# ENERGIS_Rack-PDU_1_0_0.net
KiCad netlist of a schematic drawn in EAGLE
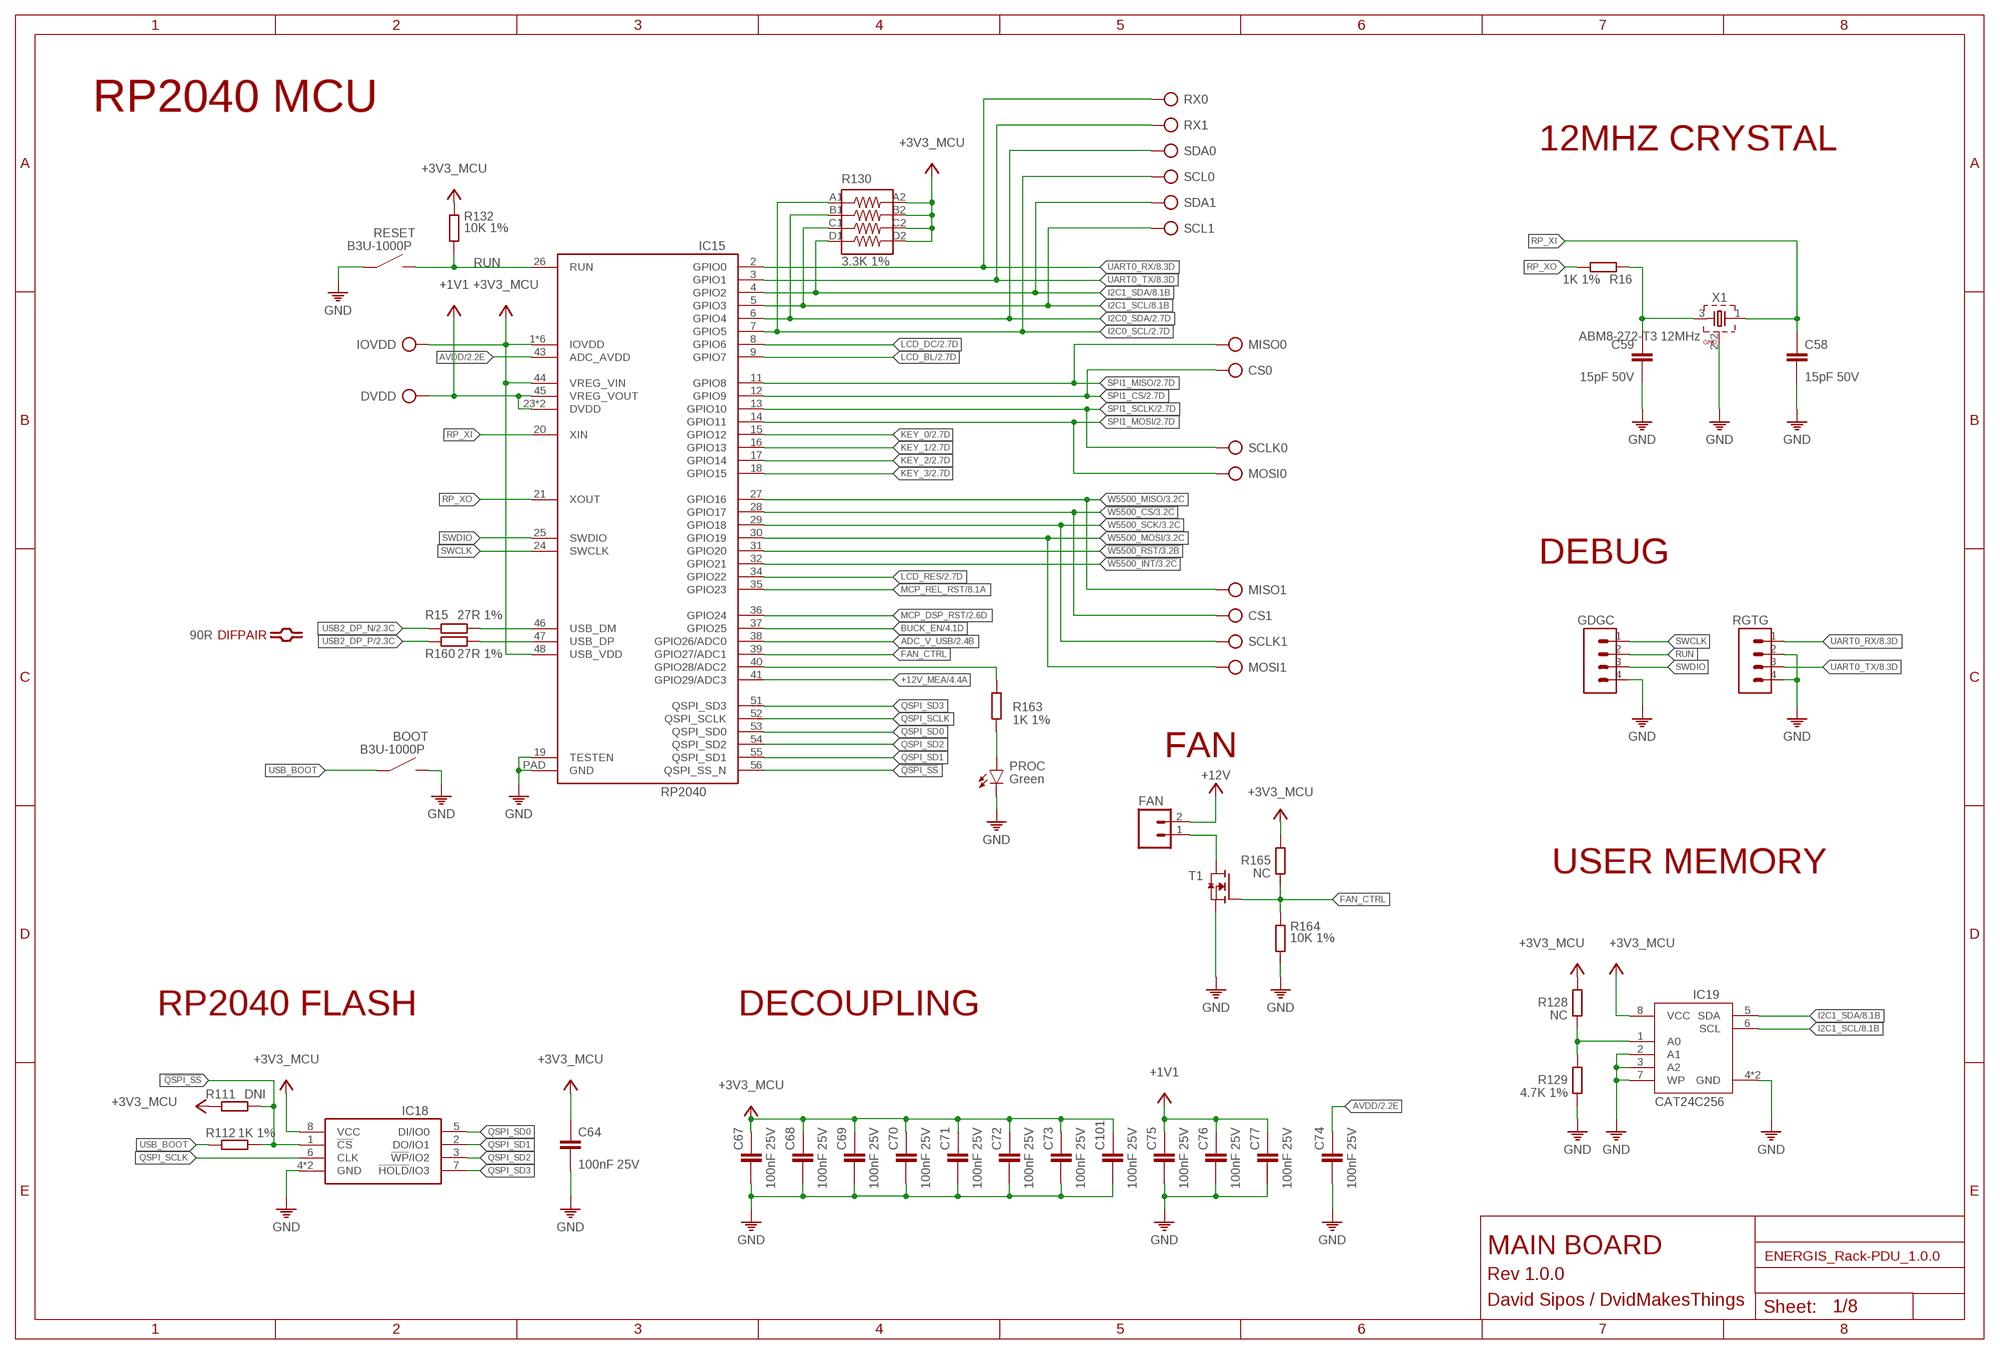
[diagram p0: schematic, sheet 1]
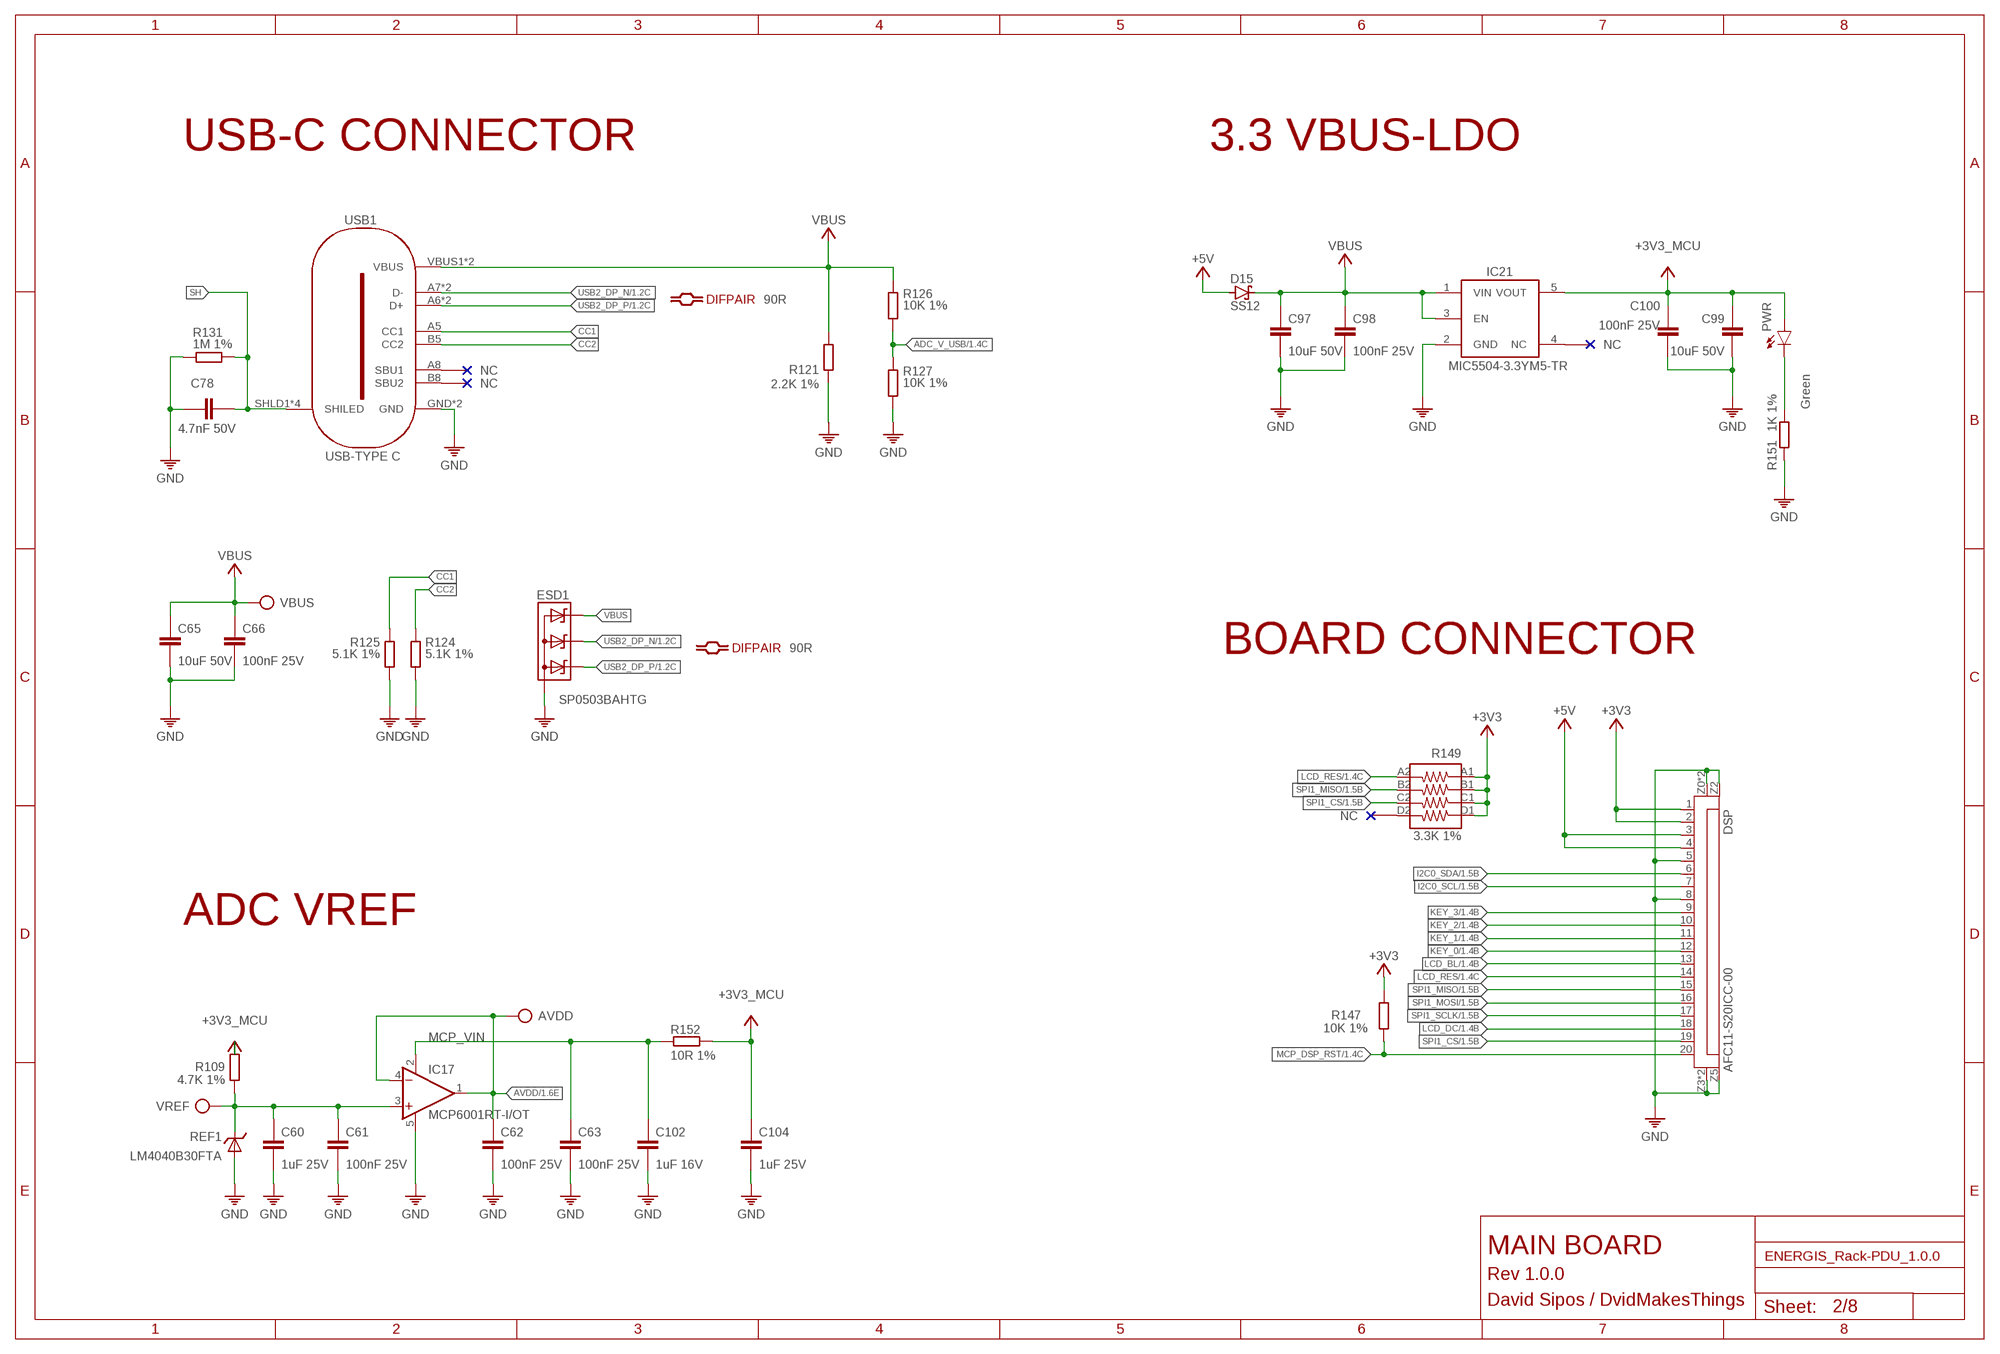
[diagram p1: schematic, sheet 2]
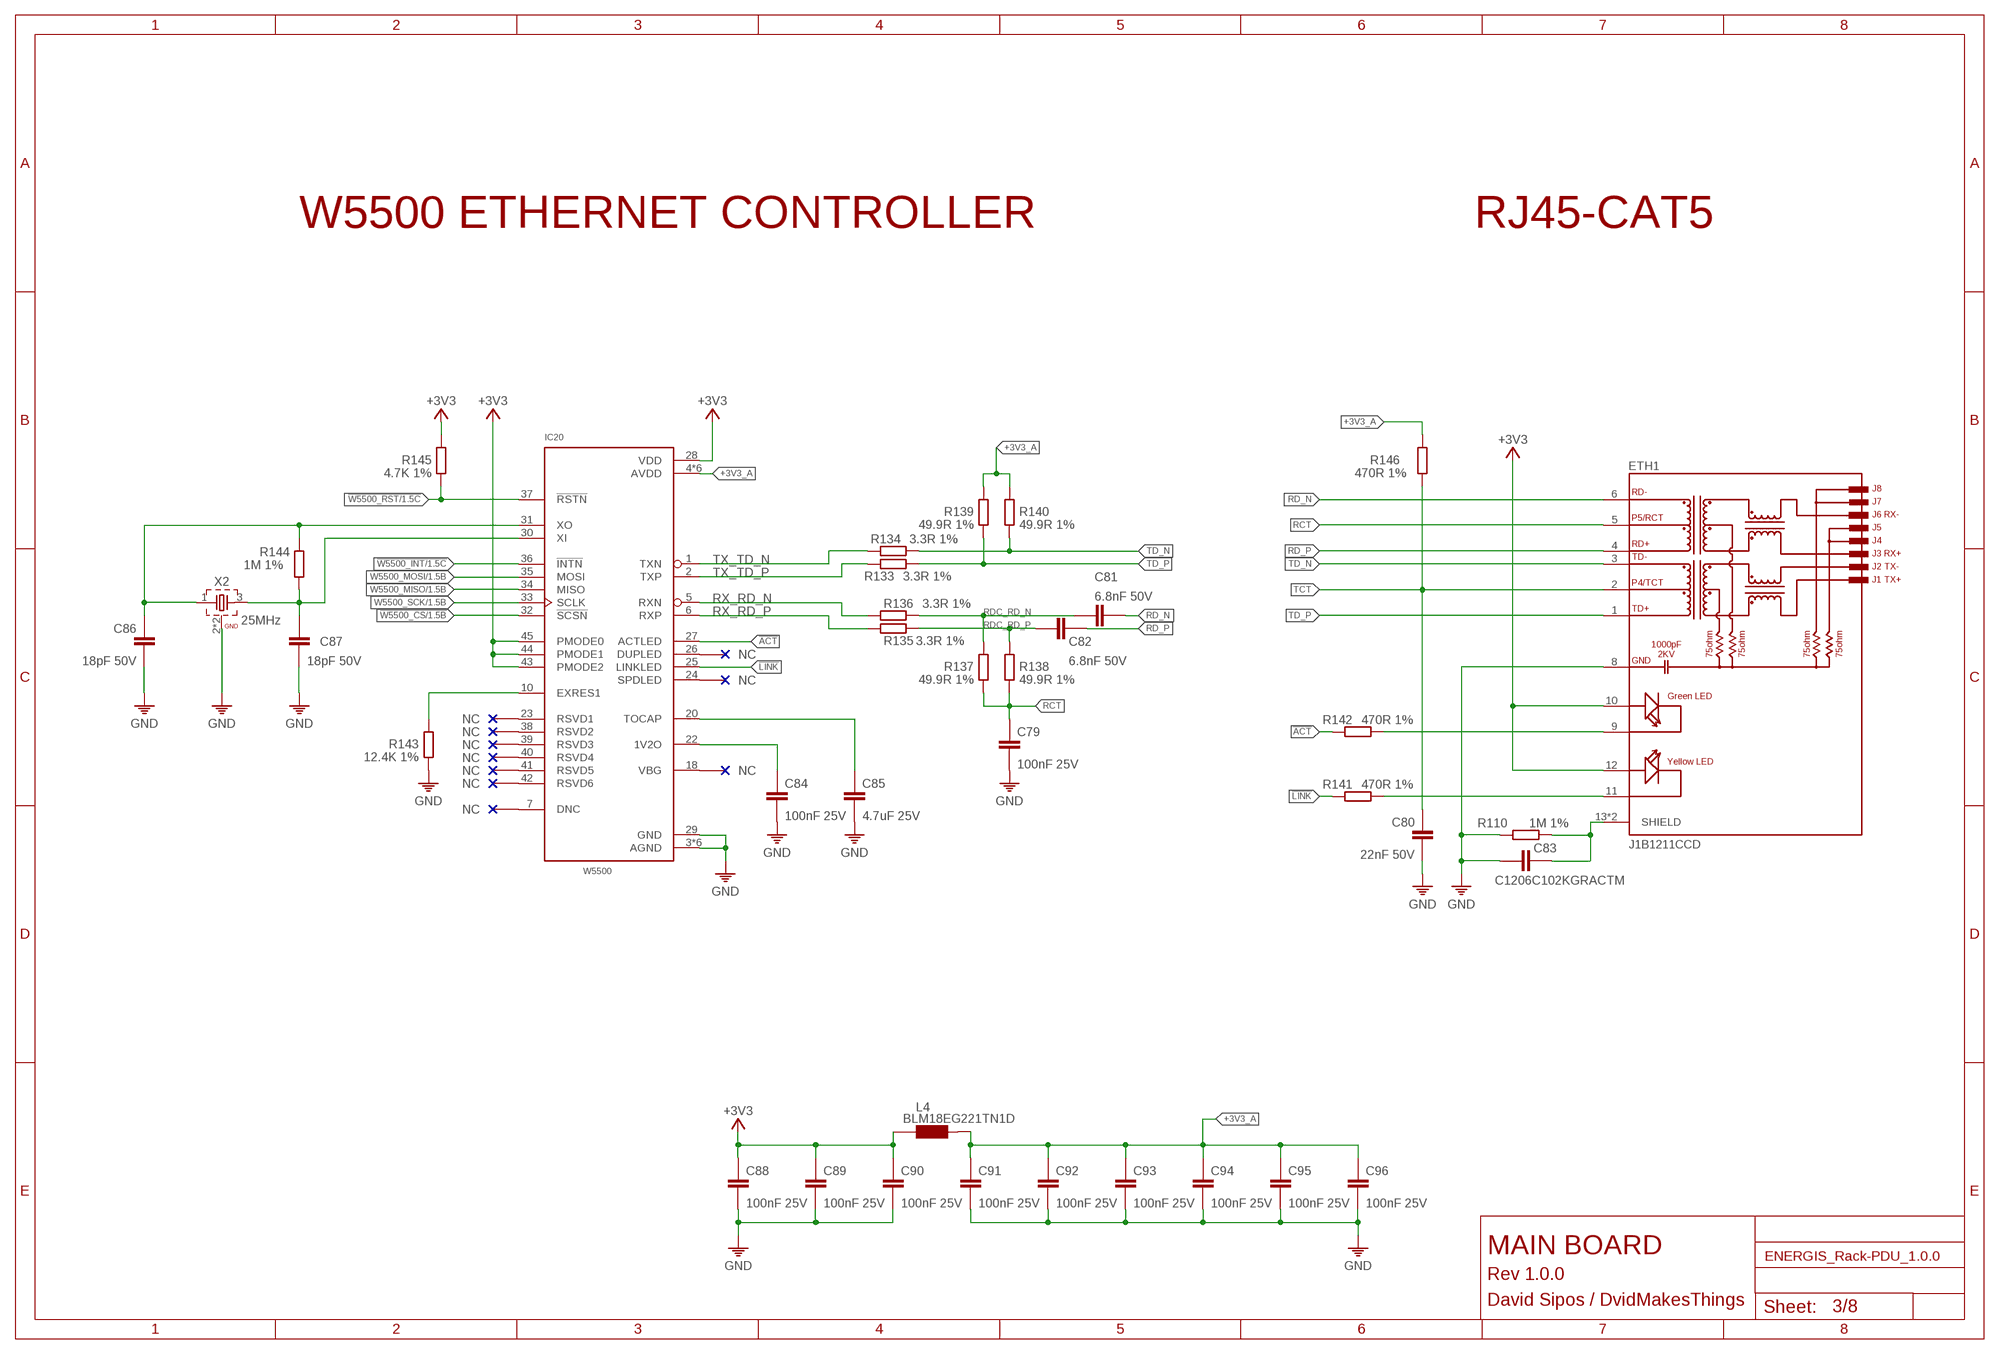
[diagram p2: schematic, sheet 3]
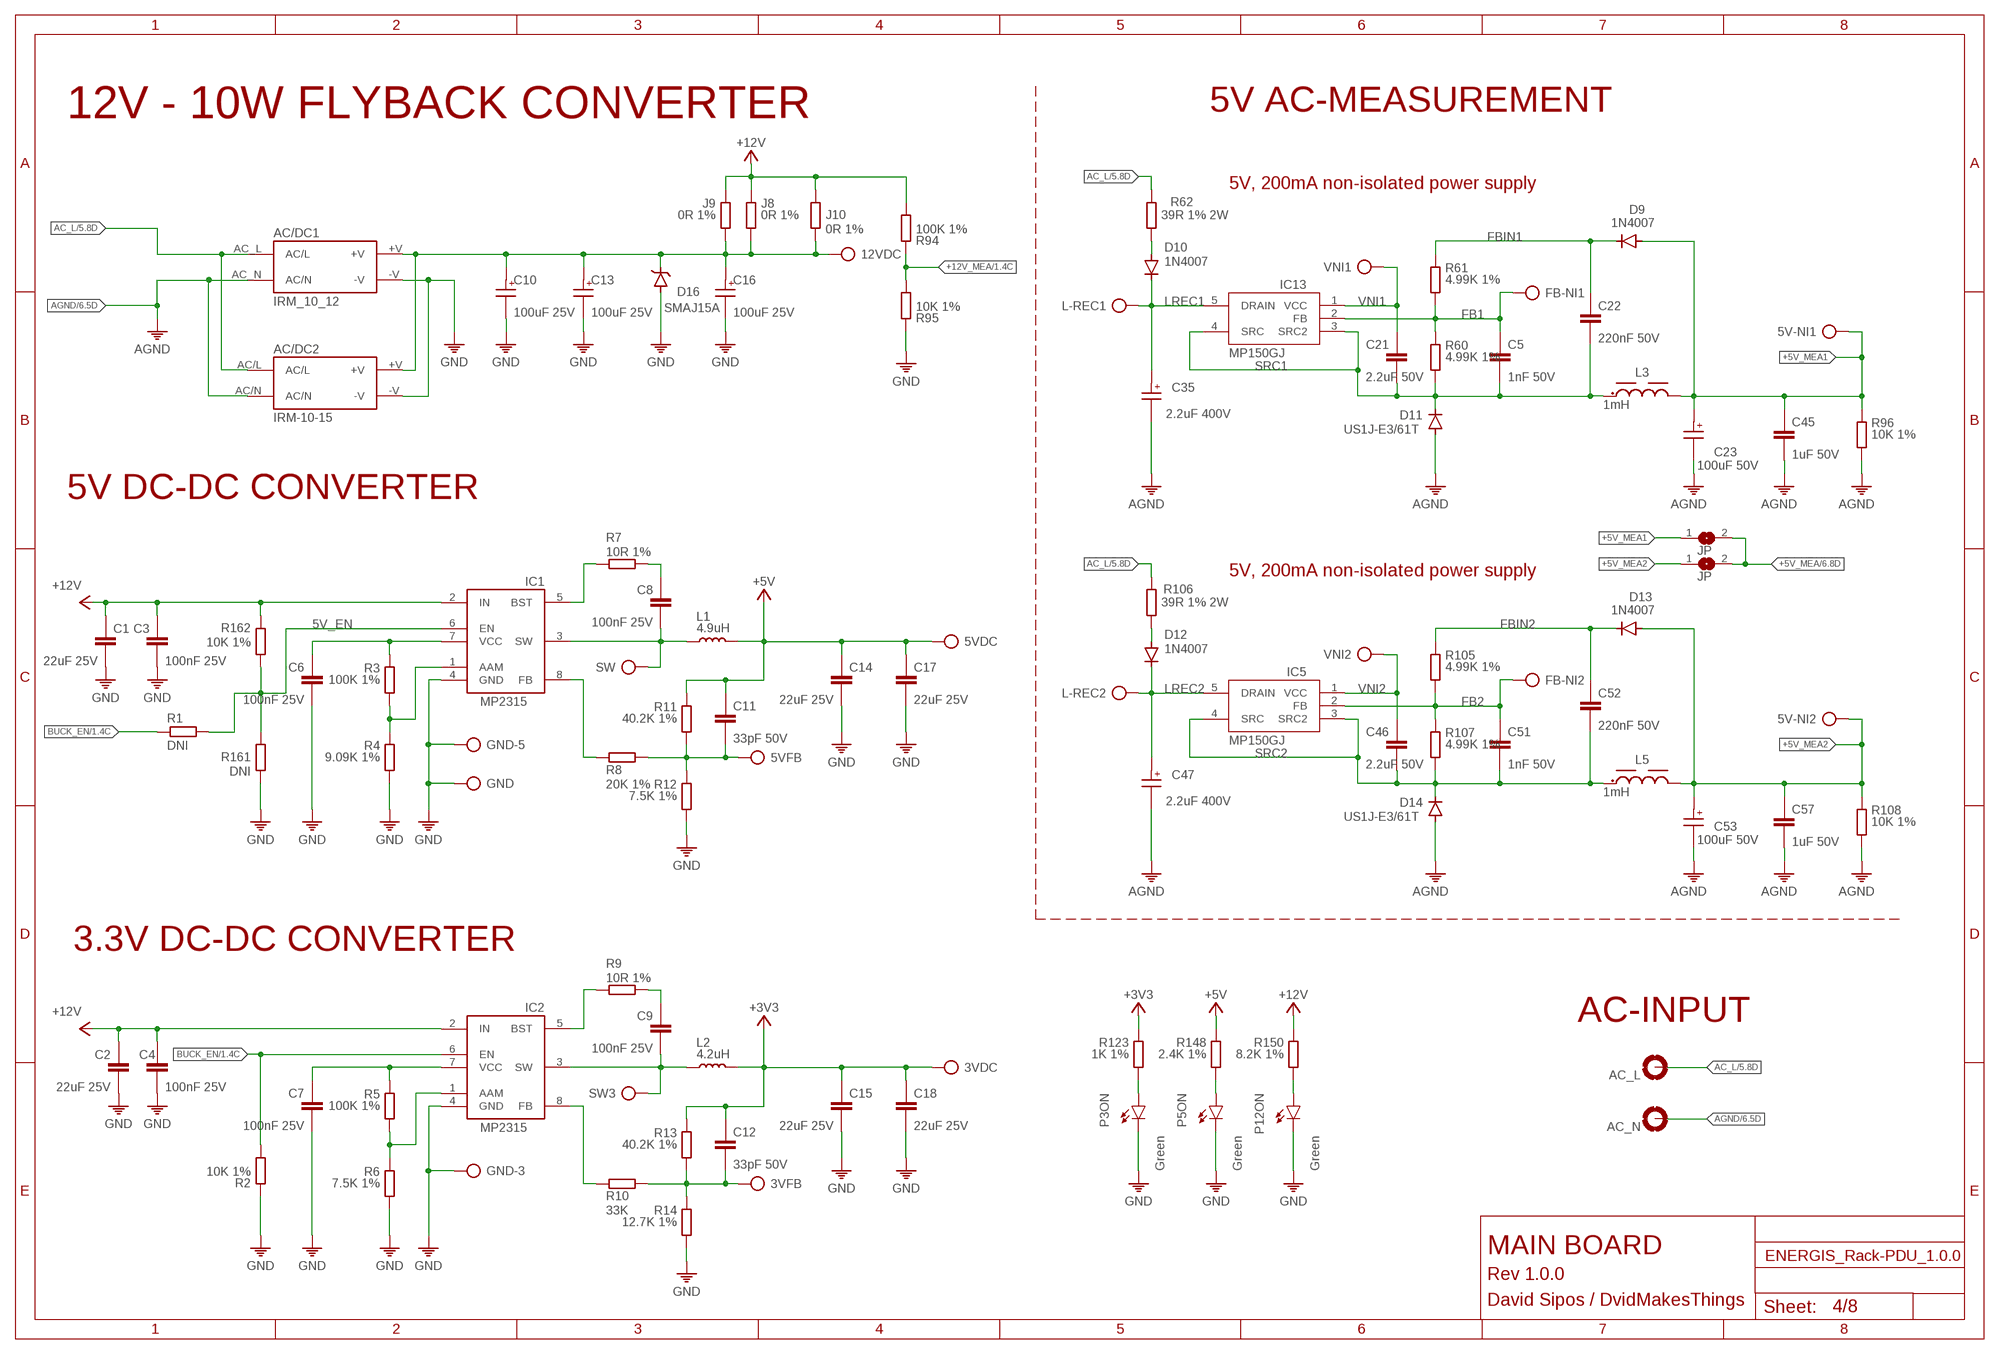
[diagram p3: schematic, sheet 4]
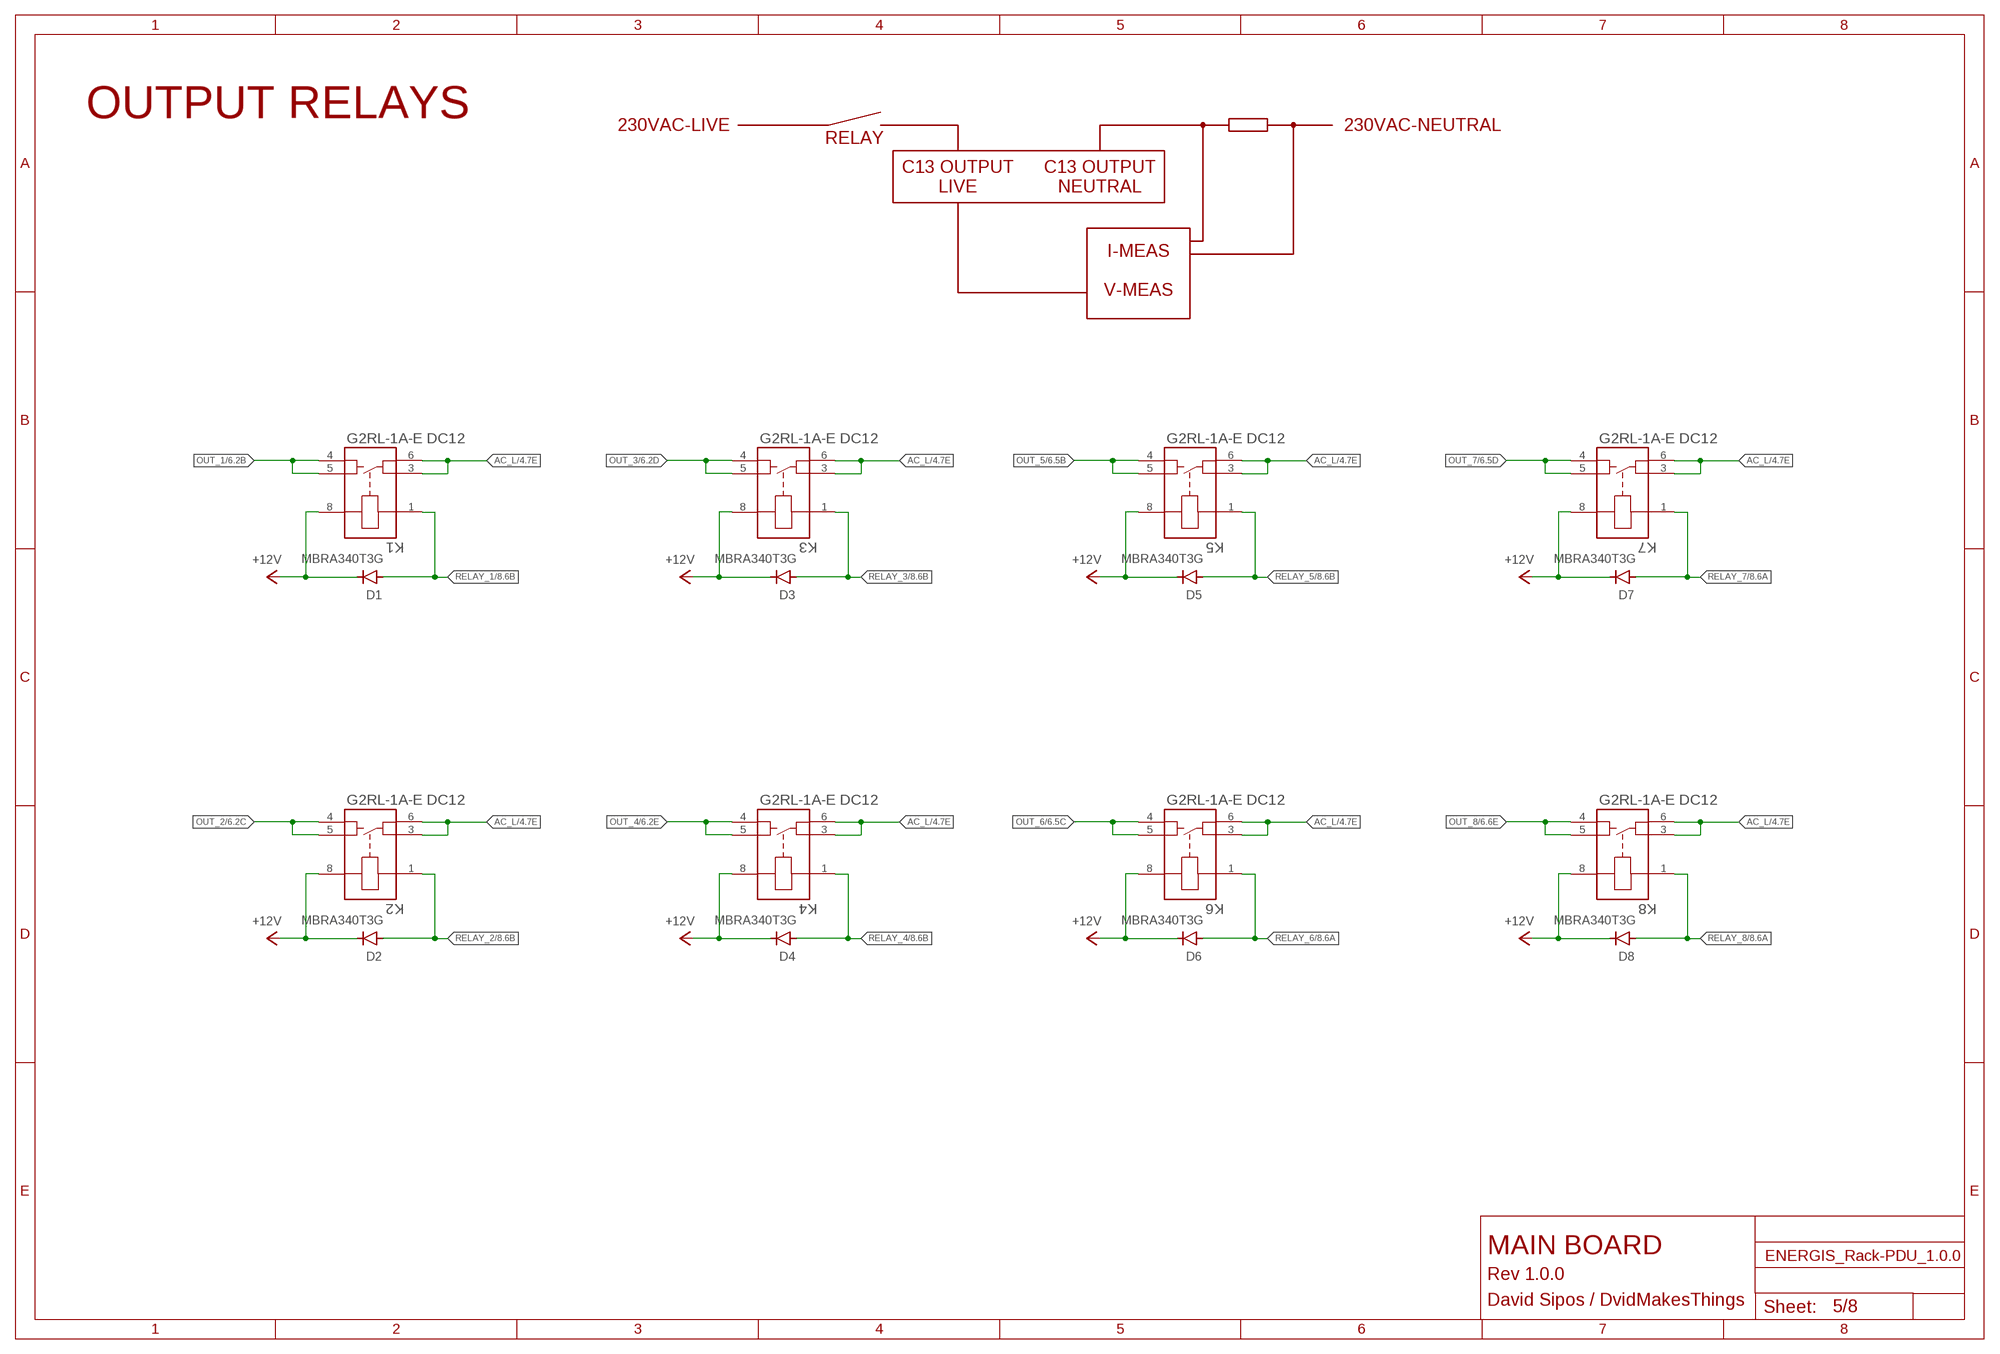
[diagram p4: schematic, sheet 5]
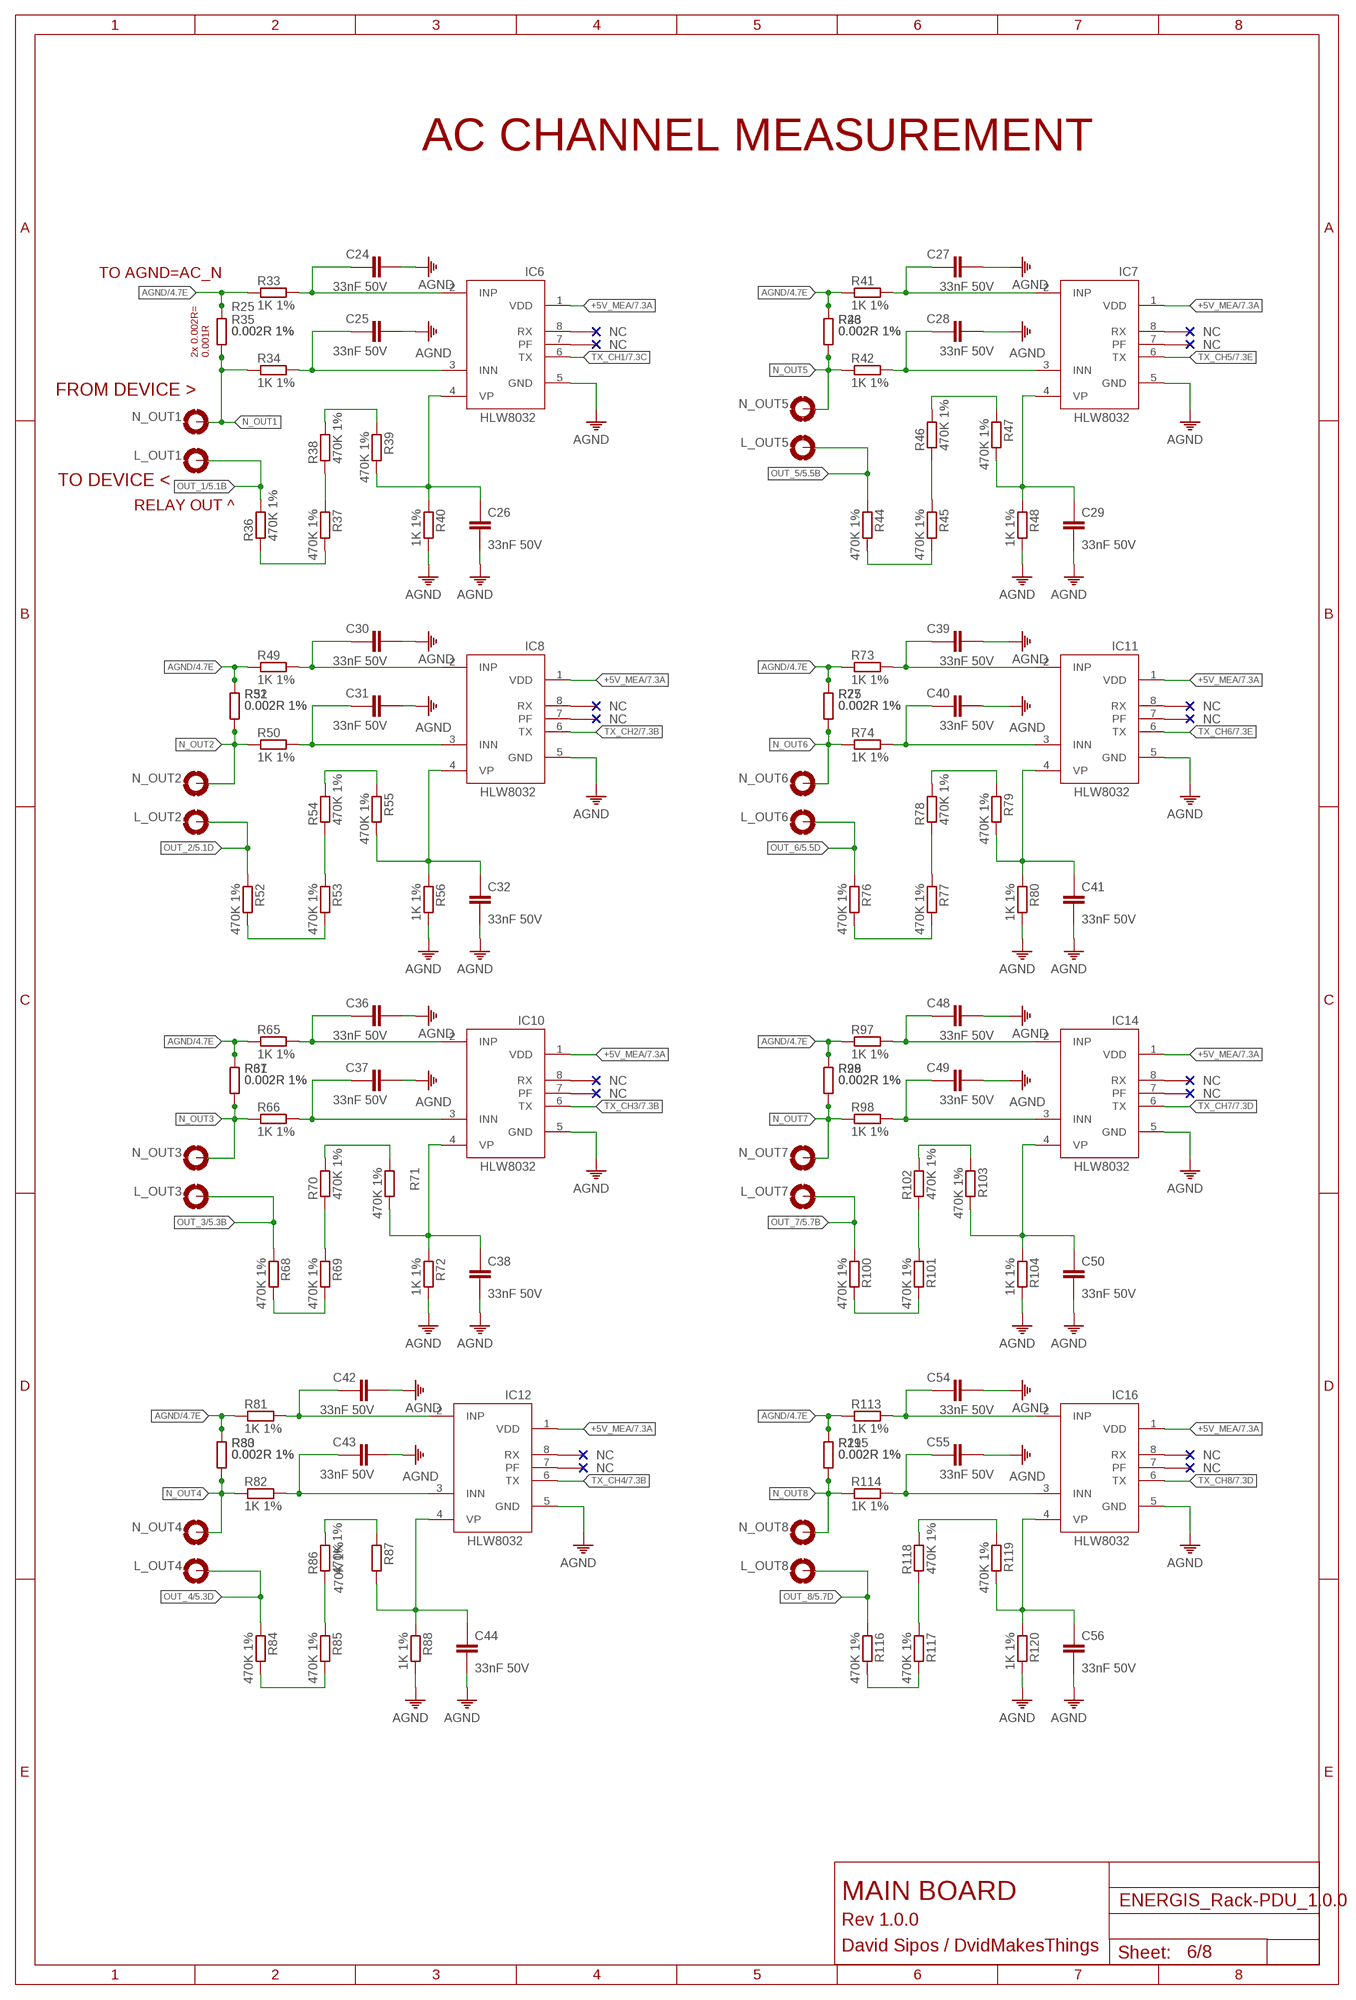
[diagram p5: schematic, sheet 6]
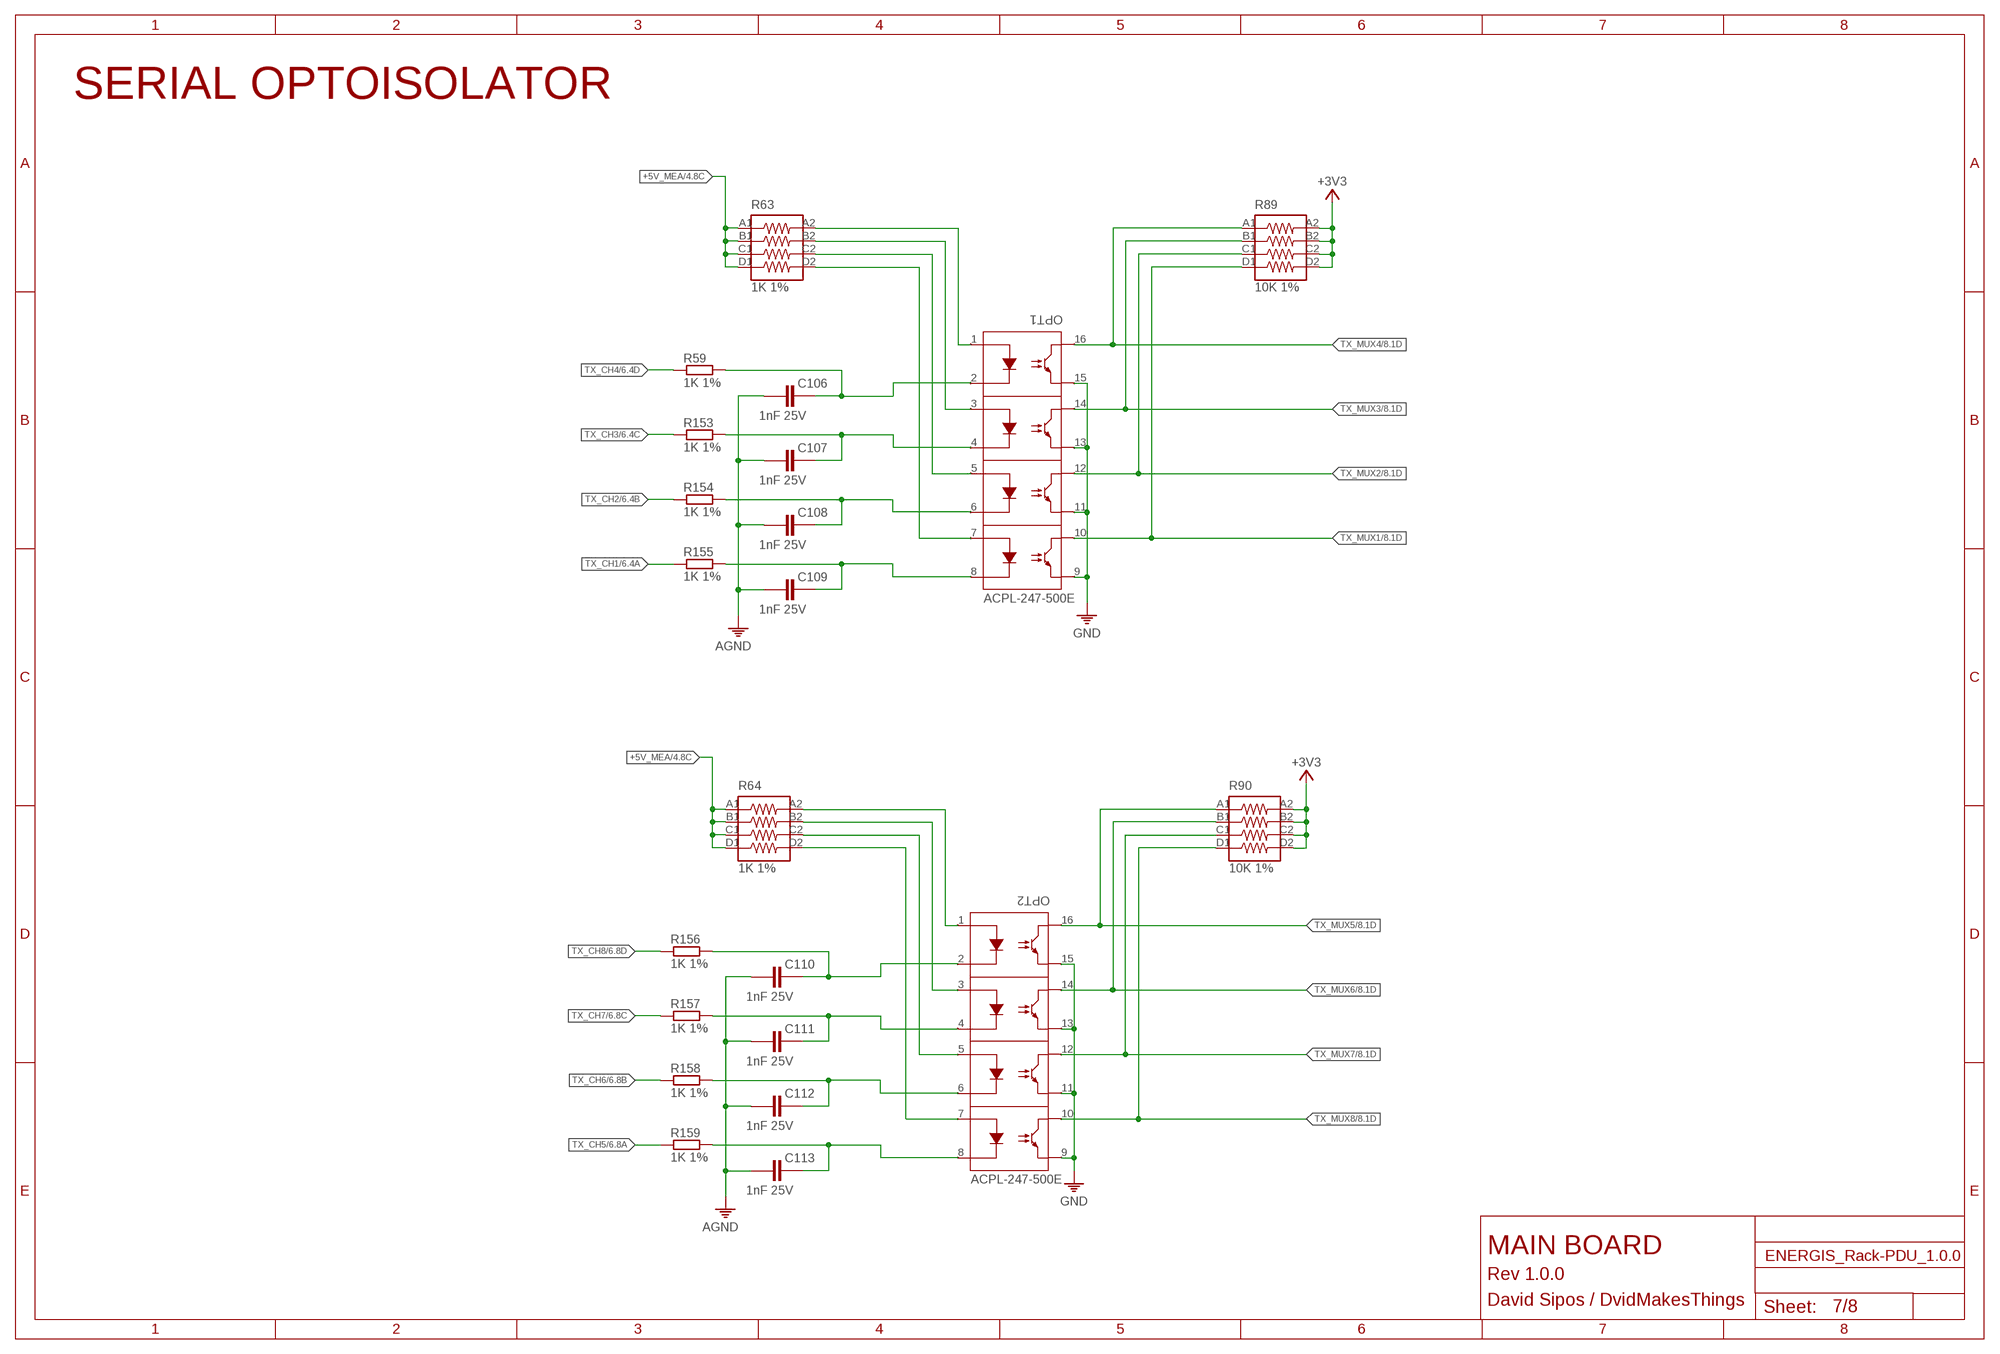
[diagram p6: schematic, sheet 7]
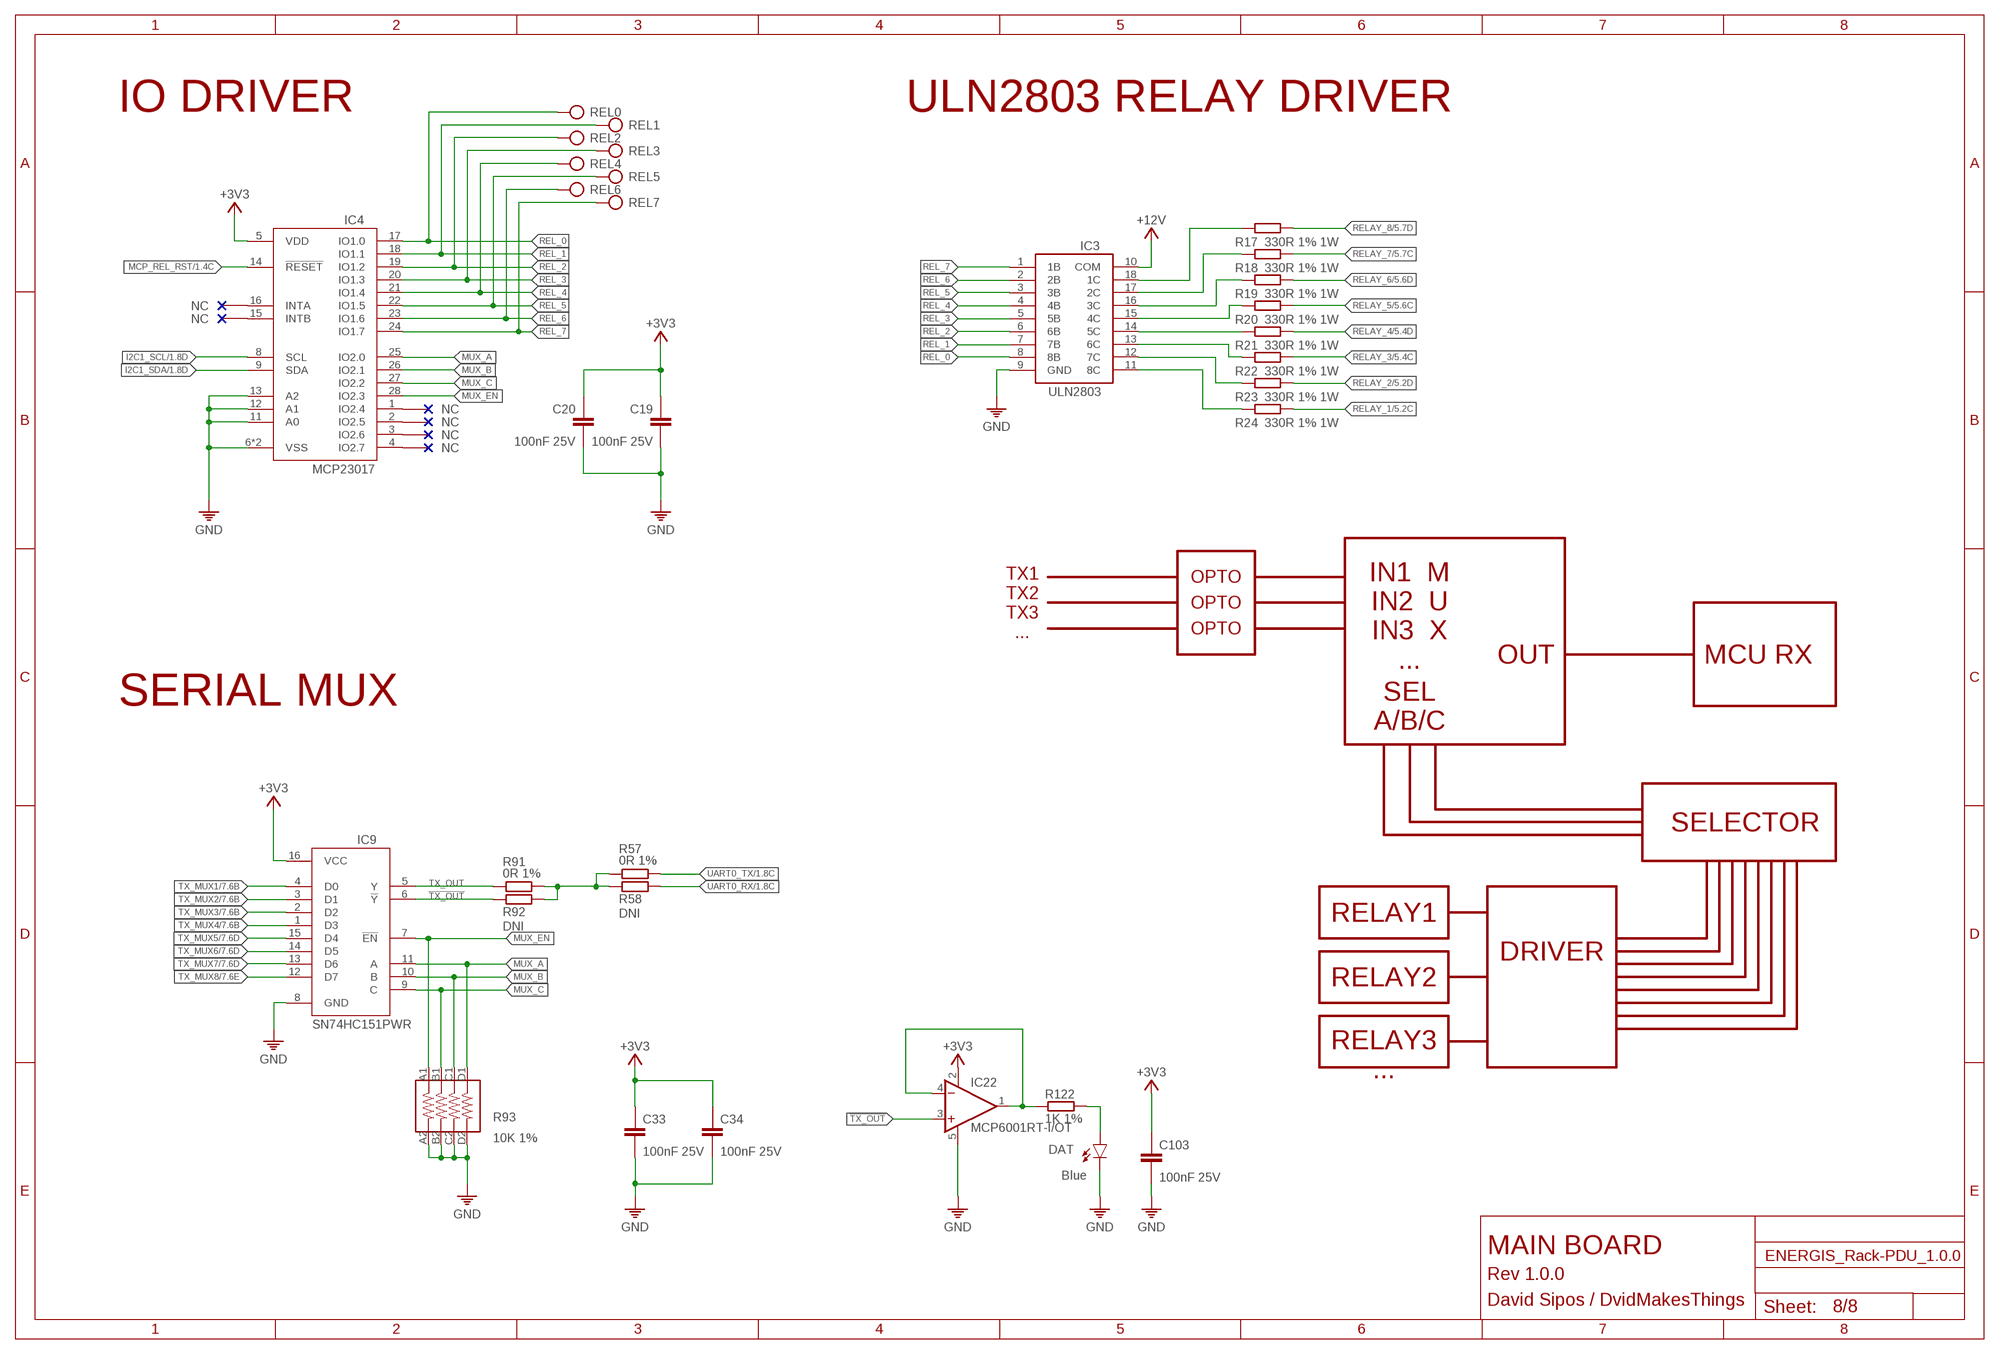
[diagram p7: schematic, sheet 8]

(export (version "E")
  (design (tool "Eeschema 10.0.6"))
  (components
    (comp (ref "BOOT")
      (value "B3U-1000P")
      (footprint "eagle-import:B3U-1000P")
      (fields (field (name "LCSC_PART") "C231329"))
      (libsource (lib "eagle-import") (part "B3U-1000P"))
    )
    (comp (ref "C58")
      (value "15pF 50V")
      (footprint "eagle-import:0201")
      (fields (field (name "LCSC_PART") "C22374851"))
      (libsource (lib "eagle-import") (part "15PF-50V0201"))
    )
    (comp (ref "C59")
      (value "15pF 50V")
      (footprint "eagle-import:0201")
      (fields (field (name "LCSC_PART") "C22374851"))
      (libsource (lib "eagle-import") (part "15PF-50V0201"))
    )
    (comp (ref "C64")
      (value "100nF 25V")
      (footprint "eagle-import:0201")
      (fields (field (name "LCSC_PART") "C76939"))
      (libsource (lib "eagle-import") (part "100NF-25V-0201"))
    )
    (comp (ref "C67")
      (value "100nF 25V")
      (footprint "eagle-import:0201")
      (fields (field (name "LCSC_PART") "C76939"))
      (libsource (lib "eagle-import") (part "100NF-25V-0201"))
    )
    (comp (ref "C68")
      (value "100nF 25V")
      (footprint "eagle-import:0201")
      (fields (field (name "LCSC_PART") "C76939"))
      (libsource (lib "eagle-import") (part "100NF-25V-0201"))
    )
    (comp (ref "C69")
      (value "100nF 25V")
      (footprint "eagle-import:0201")
      (fields (field (name "LCSC_PART") "C76939"))
      (libsource (lib "eagle-import") (part "100NF-25V-0201"))
    )
    (comp (ref "C70")
      (value "100nF 25V")
      (footprint "eagle-import:0201")
      (fields (field (name "LCSC_PART") "C76939"))
      (libsource (lib "eagle-import") (part "100NF-25V-0201"))
    )
    (comp (ref "C71")
      (value "100nF 25V")
      (footprint "eagle-import:0201")
      (fields (field (name "LCSC_PART") "C76939"))
      (libsource (lib "eagle-import") (part "100NF-25V-0201"))
    )
    (comp (ref "C72")
      (value "100nF 25V")
      (footprint "eagle-import:0201")
      (fields (field (name "LCSC_PART") "C76939"))
      (libsource (lib "eagle-import") (part "100NF-25V-0201"))
    )
    (comp (ref "C73")
      (value "100nF 25V")
      (footprint "eagle-import:0201")
      (fields (field (name "LCSC_PART") "C76939"))
      (libsource (lib "eagle-import") (part "100NF-25V-0201"))
    )
    (comp (ref "C74")
      (value "100nF 25V")
      (footprint "eagle-import:0201")
      (fields (field (name "LCSC_PART") "C76939"))
      (libsource (lib "eagle-import") (part "100NF-25V-0201"))
    )
    (comp (ref "C75")
      (value "100nF 25V")
      (footprint "eagle-import:0201")
      (fields (field (name "LCSC_PART") "C76939"))
      (libsource (lib "eagle-import") (part "100NF-25V-0201"))
    )
    (comp (ref "C76")
      (value "100nF 25V")
      (footprint "eagle-import:0201")
      (fields (field (name "LCSC_PART") "C76939"))
      (libsource (lib "eagle-import") (part "100NF-25V-0201"))
    )
    (comp (ref "C77")
      (value "100nF 25V")
      (footprint "eagle-import:0201")
      (fields (field (name "LCSC_PART") "C76939"))
      (libsource (lib "eagle-import") (part "100NF-25V-0201"))
    )
    (comp (ref "C101")
      (value "100nF 25V")
      (footprint "eagle-import:0201")
      (fields (field (name "LCSC_PART") "C76939"))
      (libsource (lib "eagle-import") (part "100NF-25V-0201"))
    )
    (comp (ref "CS0") (value "TP") (footprint "eagle-import:TP") (libsource (lib "eagle-import") (part "TP")))
    (comp (ref "CS1") (value "TP") (footprint "eagle-import:TP") (libsource (lib "eagle-import") (part "TP")))
    (comp (ref "DVDD")
      (value "TP")
      (footprint "eagle-import:TP")
      (libsource (lib "eagle-import") (part "TP"))
    )
    (comp (ref "FAN")
      (value "M02")
      (footprint "eagle-import:02P")
      (libsource (lib "eagle-import") (part "M02"))
    )
    (comp (ref "GDGC")
      (value "CON-1X4")
      (footprint "eagle-import:1X4")
      (libsource (lib "eagle-import") (part "CON-1X4"))
    )
    (comp (ref "IC15")
      (value "RP2040")
      (footprint "eagle-import:QFN56")
      (fields (field (name "LCSC_PART") "C2040"))
      (libsource (lib "eagle-import") (part "RP2040"))
    )
    (comp (ref "IC18")
      (value "W25Q128JVPIQ")
      (footprint "eagle-import:SON127P600X500X75-8N")
      (fields (field (name "LCSC_PART") "C190862"))
      (libsource (lib "eagle-import") (part "W25Q128JVP"))
    )
    (comp (ref "IC19")
      (value "CAT24C256HU4IGT3")
      (footprint "eagle-import:SON50P300X200X50-9T130X140N")
      (fields (field (name "LCSC_PART") "C233771"))
      (libsource (lib "eagle-import") (part "CAT24C256-HU4"))
    )
    (comp (ref "IOVDD")
      (value "TP")
      (footprint "eagle-import:TP")
      (libsource (lib "eagle-import") (part "TP"))
    )
    (comp (ref "MISO0")
      (value "TP")
      (footprint "eagle-import:TP")
      (libsource (lib "eagle-import") (part "TP"))
    )
    (comp (ref "MISO1")
      (value "TP")
      (footprint "eagle-import:TP")
      (libsource (lib "eagle-import") (part "TP"))
    )
    (comp (ref "MOSI0")
      (value "TP")
      (footprint "eagle-import:TP")
      (libsource (lib "eagle-import") (part "TP"))
    )
    (comp (ref "MOSI1")
      (value "TP")
      (footprint "eagle-import:TP")
      (libsource (lib "eagle-import") (part "TP"))
    )
    (comp (ref "PROC")
      (value "Green")
      (footprint "eagle-import:LED-0603")
      (fields (field (name "LCSC_PART") "C965804"))
      (libsource (lib "eagle-import") (part "LED-GREENLED-0603"))
    )
    (comp (ref "R15")
      (value "27R 1%")
      (footprint "eagle-import:0201")
      (fields (field (name "LCSC_PART") "C473051"))
      (libsource (lib "eagle-import") (part "27R-1%0201"))
    )
    (comp (ref "R16")
      (value "1K 1%")
      (footprint "eagle-import:0201")
      (fields (field (name "LCSC_PART") "C270365"))
      (libsource (lib "eagle-import") (part "1K-1%0201"))
    )
    (comp (ref "R111")
      (value "DNI")
      (footprint "eagle-import:R0201")
      (libsource (lib "eagle-import") (part "R0201"))
    )
    (comp (ref "R112")
      (value "1K 1%")
      (footprint "eagle-import:0402")
      (fields (field (name "LCSC_PART") "C11702"))
      (libsource (lib "eagle-import") (part "1K-1%0402"))
    )
    (comp (ref "R128")
      (value "NC")
      (footprint "eagle-import:R0201")
      (libsource (lib "eagle-import") (part "R0201"))
    )
    (comp (ref "R129")
      (value "4.7K 1%")
      (footprint "eagle-import:0201")
      (fields (field (name "LCSC_PART") "C270346"))
      (libsource (lib "eagle-import") (part "4.7K-1%0201"))
    )
    (comp (ref "R130")
      (value "3.3K 1%")
      (footprint "eagle-import:_0603X4-1206")
      (fields (field (name "LCSC_PART") "C1734380"))
      (libsource (lib "eagle-import") (part "3.3K-1%_ARRAY0603X4-1206"))
    )
    (comp (ref "R132")
      (value "10K 1%")
      (footprint "eagle-import:0402")
      (fields (field (name "LCSC_PART") "C25744"))
      (libsource (lib "eagle-import") (part "10K-1%0402"))
    )
    (comp (ref "R160")
      (value "27R 1%")
      (footprint "eagle-import:0201")
      (fields (field (name "LCSC_PART") "C473051"))
      (libsource (lib "eagle-import") (part "27R-1%0201"))
    )
    (comp (ref "R163")
      (value "1K 1%")
      (footprint "eagle-import:0402")
      (fields (field (name "LCSC_PART") "C11702"))
      (libsource (lib "eagle-import") (part "1K-1%0402"))
    )
    (comp (ref "R164")
      (value "10K 1%")
      (footprint "eagle-import:0402")
      (fields (field (name "LCSC_PART") "C25744"))
      (libsource (lib "eagle-import") (part "10K-1%0402"))
    )
    (comp (ref "R165")
      (value "NC")
      (footprint "eagle-import:R0201")
      (libsource (lib "eagle-import") (part "R0201"))
    )
    (comp (ref "RESET")
      (value "B3U-1000P")
      (footprint "eagle-import:B3U-1000P")
      (fields (field (name "LCSC_PART") "C231329"))
      (libsource (lib "eagle-import") (part "B3U-1000P"))
    )
    (comp (ref "RGTG")
      (value "CON-1X4")
      (footprint "eagle-import:1X4")
      (libsource (lib "eagle-import") (part "CON-1X4"))
    )
    (comp (ref "RX0") (value "TP") (footprint "eagle-import:TP") (libsource (lib "eagle-import") (part "TP")))
    (comp (ref "RX1") (value "TP") (footprint "eagle-import:TP") (libsource (lib "eagle-import") (part "TP")))
    (comp (ref "SCL0")
      (value "TP")
      (footprint "eagle-import:TP")
      (libsource (lib "eagle-import") (part "TP"))
    )
    (comp (ref "SCL1")
      (value "TP")
      (footprint "eagle-import:TP")
      (libsource (lib "eagle-import") (part "TP"))
    )
    (comp (ref "SCLK0")
      (value "TP")
      (footprint "eagle-import:TP")
      (libsource (lib "eagle-import") (part "TP"))
    )
    (comp (ref "SCLK1")
      (value "TP")
      (footprint "eagle-import:TP")
      (libsource (lib "eagle-import") (part "TP"))
    )
    (comp (ref "SDA0")
      (value "TP")
      (footprint "eagle-import:TP")
      (libsource (lib "eagle-import") (part "TP"))
    )
    (comp (ref "SDA1")
      (value "TP")
      (footprint "eagle-import:TP")
      (libsource (lib "eagle-import") (part "TP"))
    )
    (comp (ref "T1")
      (value "BSS138")
      (footprint "eagle-import:SOT23")
      (libsource (lib "eagle-import") (part "BSS138"))
    )
    (comp (ref "X1")
      (value "ABM8-272-T3 12MHz")
      (footprint "eagle-import:WE-XTAL_CFPX-180")
      (fields (field (name "LCSC_PART") "C20625731"))
      (libsource (lib "eagle-import") (part "CRYSTAL-3225X322512MSB4SI"))
    )
    (comp (ref "C79")
      (value "100nF 25V")
      (footprint "eagle-import:0402")
      (fields (field (name "LCSC_PART") "C56392"))
      (libsource (lib "eagle-import") (part "100NF-25V-0402"))
    )
    (comp (ref "C80")
      (value "22nF 50V")
      (footprint "eagle-import:0402")
      (fields (field (name "LCSC_PART") "C1532"))
      (libsource (lib "eagle-import") (part "22NF-50V0402"))
    )
    (comp (ref "C81")
      (value "6.8nF 50V")
      (footprint "eagle-import:0201")
      (fields (field (name "LCSC_PART") "C285015"))
      (libsource (lib "eagle-import") (part "6.8NF-50V0201"))
    )
    (comp (ref "C82")
      (value "6.8nF 50V")
      (footprint "eagle-import:0201")
      (fields (field (name "LCSC_PART") "C285015"))
      (libsource (lib "eagle-import") (part "6.8NF-50V0201"))
    )
    (comp (ref "C83")
      (value "C1206C102KGRACTM")
      (footprint "eagle-import:C1206")
      (libsource (lib "eagle-import") (part "C-1206"))
    )
    (comp (ref "C84")
      (value "100nF 25V")
      (footprint "eagle-import:0201")
      (fields (field (name "LCSC_PART") "C76939"))
      (libsource (lib "eagle-import") (part "100NF-25V-0201"))
    )
    (comp (ref "C85")
      (value "4.7uF 25V")
      (footprint "eagle-import:0402")
      (fields (field (name "LCSC_PART") "C22367824"))
      (libsource (lib "eagle-import") (part "4.7UF-25V0402"))
    )
    (comp (ref "C86")
      (value "18pF 50V")
      (footprint "eagle-import:0201")
      (fields (field (name "LCSC_PART") "C62164"))
      (libsource (lib "eagle-import") (part "18PF-50V-0201"))
    )
    (comp (ref "C87")
      (value "18pF 50V")
      (footprint "eagle-import:0201")
      (fields (field (name "LCSC_PART") "C62164"))
      (libsource (lib "eagle-import") (part "18PF-50V-0201"))
    )
    (comp (ref "C88")
      (value "100nF 25V")
      (footprint "eagle-import:0201")
      (fields (field (name "LCSC_PART") "C76939"))
      (libsource (lib "eagle-import") (part "100NF-25V-0201"))
    )
    (comp (ref "C89")
      (value "100nF 25V")
      (footprint "eagle-import:0201")
      (fields (field (name "LCSC_PART") "C76939"))
      (libsource (lib "eagle-import") (part "100NF-25V-0201"))
    )
    (comp (ref "C90")
      (value "100nF 25V")
      (footprint "eagle-import:0201")
      (fields (field (name "LCSC_PART") "C76939"))
      (libsource (lib "eagle-import") (part "100NF-25V-0201"))
    )
    (comp (ref "C91")
      (value "100nF 25V")
      (footprint "eagle-import:0201")
      (fields (field (name "LCSC_PART") "C76939"))
      (libsource (lib "eagle-import") (part "100NF-25V-0201"))
    )
    (comp (ref "C92")
      (value "100nF 25V")
      (footprint "eagle-import:0201")
      (fields (field (name "LCSC_PART") "C76939"))
      (libsource (lib "eagle-import") (part "100NF-25V-0201"))
    )
    (comp (ref "C93")
      (value "100nF 25V")
      (footprint "eagle-import:0201")
      (fields (field (name "LCSC_PART") "C76939"))
      (libsource (lib "eagle-import") (part "100NF-25V-0201"))
    )
    (comp (ref "C94")
      (value "100nF 25V")
      (footprint "eagle-import:0201")
      (fields (field (name "LCSC_PART") "C76939"))
      (libsource (lib "eagle-import") (part "100NF-25V-0201"))
    )
    (comp (ref "C95")
      (value "100nF 25V")
      (footprint "eagle-import:0201")
      (fields (field (name "LCSC_PART") "C76939"))
      (libsource (lib "eagle-import") (part "100NF-25V-0201"))
    )
    (comp (ref "C96")
      (value "100nF 25V")
      (footprint "eagle-import:0201")
      (fields (field (name "LCSC_PART") "C76939"))
      (libsource (lib "eagle-import") (part "100NF-25V-0201"))
    )
    (comp (ref "ETH1")
      (value "J1B1211CCD")
      (footprint "eagle-import:J1B1211CCD")
      (fields (field (name "LCSC_PART") "C910371"))
      (libsource (lib "eagle-import") (part "J1B1211CCD"))
    )
    (comp (ref "IC20")
      (value "W5500")
      (footprint "eagle-import:LQFP48")
      (fields (field (name "LCSC_PART") "C32843"))
      (libsource (lib "eagle-import") (part "W5500"))
    )
    (comp (ref "L4")
      (value "BLM18EG221TN1D")
      (footprint "eagle-import:0603")
      (fields (field (name "LCSC_PART") "C113025"))
      (libsource (lib "eagle-import") (part "BLM18EG221TN1D"))
    )
    (comp (ref "R110")
      (value "1M 1%")
      (footprint "eagle-import:1206")
      (fields (field (name "LCSC_PART") "C17927"))
      (libsource (lib "eagle-import") (part "1M-1%1206"))
    )
    (comp (ref "R133")
      (value "3.3R 1%")
      (footprint "eagle-import:0201")
      (fields (field (name "LCSC_PART") "C158547"))
      (libsource (lib "eagle-import") (part "3.3R-1%0201"))
    )
    (comp (ref "R134")
      (value "3.3R 1%")
      (footprint "eagle-import:0201")
      (fields (field (name "LCSC_PART") "C158547"))
      (libsource (lib "eagle-import") (part "3.3R-1%0201"))
    )
    (comp (ref "R135")
      (value "3.3R 1%")
      (footprint "eagle-import:0201")
      (fields (field (name "LCSC_PART") "C158547"))
      (libsource (lib "eagle-import") (part "3.3R-1%0201"))
    )
    (comp (ref "R136")
      (value "3.3R 1%")
      (footprint "eagle-import:0201")
      (fields (field (name "LCSC_PART") "C158547"))
      (libsource (lib "eagle-import") (part "3.3R-1%0201"))
    )
    (comp (ref "R137")
      (value "49.9R 1%")
      (footprint "eagle-import:0201")
      (fields (field (name "LCSC_PART") "C155744"))
      (libsource (lib "eagle-import") (part "49.9R-1%0201"))
    )
    (comp (ref "R138")
      (value "49.9R 1%")
      (footprint "eagle-import:0201")
      (fields (field (name "LCSC_PART") "C155744"))
      (libsource (lib "eagle-import") (part "49.9R-1%0201"))
    )
    (comp (ref "R139")
      (value "49.9R 1%")
      (footprint "eagle-import:0201")
      (fields (field (name "LCSC_PART") "C155744"))
      (libsource (lib "eagle-import") (part "49.9R-1%0201"))
    )
    (comp (ref "R140")
      (value "49.9R 1%")
      (footprint "eagle-import:0201")
      (fields (field (name "LCSC_PART") "C155744"))
      (libsource (lib "eagle-import") (part "49.9R-1%0201"))
    )
    (comp (ref "R141")
      (value "470R 1%")
      (footprint "eagle-import:0402")
      (fields (field (name "LCSC_PART") "C25117"))
      (libsource (lib "eagle-import") (part "470R-1%0402"))
    )
    (comp (ref "R142")
      (value "470R 1%")
      (footprint "eagle-import:0402")
      (fields (field (name "LCSC_PART") "C25117"))
      (libsource (lib "eagle-import") (part "470R-1%0402"))
    )
    (comp (ref "R143")
      (value "12.4K 1%")
      (footprint "eagle-import:R0201")
      (libsource (lib "eagle-import") (part "R0201"))
    )
    (comp (ref "R144")
      (value "1M 1%")
      (footprint "eagle-import:0201")
      (fields (field (name "LCSC_PART") "C295786"))
      (libsource (lib "eagle-import") (part "1M-1%0201"))
    )
    (comp (ref "R145")
      (value "4.7K 1%")
      (footprint "eagle-import:0201")
      (fields (field (name "LCSC_PART") "C270346"))
      (libsource (lib "eagle-import") (part "4.7K-1%0201"))
    )
    (comp (ref "R146")
      (value "470R 1%")
      (footprint "eagle-import:0402")
      (fields (field (name "LCSC_PART") "C25117"))
      (libsource (lib "eagle-import") (part "470R-1%0402"))
    )
    (comp (ref "X2")
      (value "25MHz")
      (footprint "eagle-import:WE-XTAL_CFPX-180")
      (fields (field (name "LCSC_PART") "C9006"))
      (libsource (lib "eagle-import") (part "CRYSTAL-3225X322525MOB4SI"))
    )
    (comp (ref "AVDD")
      (value "TP")
      (footprint "eagle-import:TP")
      (libsource (lib "eagle-import") (part "TP"))
    )
    (comp (ref "C60")
      (value "1uF 25V")
      (footprint "eagle-import:0402")
      (fields (field (name "LCSC_PART") "C52923"))
      (libsource (lib "eagle-import") (part "1UF-25V0402"))
    )
    (comp (ref "C61")
      (value "100nF 25V")
      (footprint "eagle-import:0201")
      (fields (field (name "LCSC_PART") "C76939"))
      (libsource (lib "eagle-import") (part "100NF-25V-0201"))
    )
    (comp (ref "C62")
      (value "100nF 25V")
      (footprint "eagle-import:0201")
      (fields (field (name "LCSC_PART") "C76939"))
      (libsource (lib "eagle-import") (part "100NF-25V-0201"))
    )
    (comp (ref "C63")
      (value "100nF 25V")
      (footprint "eagle-import:0201")
      (fields (field (name "LCSC_PART") "C76939"))
      (libsource (lib "eagle-import") (part "100NF-25V-0201"))
    )
    (comp (ref "C65")
      (value "10uF 50V")
      (footprint "eagle-import:0805")
      (fields (field (name "LCSC_PART") "C440198"))
      (libsource (lib "eagle-import") (part "10UF-50V-0805"))
    )
    (comp (ref "C66")
      (value "100nF 25V")
      (footprint "eagle-import:0402")
      (fields (field (name "LCSC_PART") "C56392"))
      (libsource (lib "eagle-import") (part "100NF-25V-0402"))
    )
    (comp (ref "C78")
      (value "4.7nF 50V")
      (footprint "eagle-import:0402")
      (fields (field (name "LCSC_PART") "C1538"))
      (libsource (lib "eagle-import") (part "4.7NF-50V0402"))
    )
    (comp (ref "C97")
      (value "10uF 50V")
      (footprint "eagle-import:0805")
      (fields (field (name "LCSC_PART") "C440198"))
      (libsource (lib "eagle-import") (part "10UF-50V-0805"))
    )
    (comp (ref "C98")
      (value "100nF 25V")
      (footprint "eagle-import:0201")
      (fields (field (name "LCSC_PART") "C76939"))
      (libsource (lib "eagle-import") (part "100NF-25V-0201"))
    )
    (comp (ref "C99")
      (value "10uF 50V")
      (footprint "eagle-import:0805")
      (fields (field (name "LCSC_PART") "C440198"))
      (libsource (lib "eagle-import") (part "10UF-50V-0805"))
    )
    (comp (ref "C100")
      (value "100nF 25V")
      (footprint "eagle-import:0201")
      (fields (field (name "LCSC_PART") "C76939"))
      (libsource (lib "eagle-import") (part "100NF-25V-0201"))
    )
    (comp (ref "C102")
      (value "1uF 16V")
      (footprint "eagle-import:0201")
      (fields (field (name "LCSC_PART") "C307385"))
      (libsource (lib "eagle-import") (part "1UF-16V0201"))
    )
    (comp (ref "C104")
      (value "1uF 25V")
      (footprint "eagle-import:0402")
      (fields (field (name "LCSC_PART") "C52923"))
      (libsource (lib "eagle-import") (part "1UF-25V0402"))
    )
    (comp (ref "D15")
      (value "SS12")
      (footprint "eagle-import:SMA_DO-214AC")
      (fields (field (name "LCSC_PART") "C727049"))
      (libsource (lib "eagle-import") (part "SS12"))
    )
    (comp (ref "DSP")
      (value "AFC11-S20ICC-00")
      (footprint "eagle-import:FPC20")
      (fields (field (name "LCSC_PART") "C11073"))
      (libsource (lib "eagle-import") (part "AFC11-S20ICC-00"))
    )
    (comp (ref "ESD1")
      (value "SP0503BAHTG")
      (footprint "eagle-import:SOT143")
      (fields (field (name "LCSC_PART") "C3040626"))
      (libsource (lib "eagle-import") (part "SP0503BAHT"))
    )
    (comp (ref "IC17")
      (value "MCP6001RT-I/OT")
      (footprint "eagle-import:SOT23-5")
      (fields (field (name "LCSC_PART") "C154973"))
      (libsource (lib "eagle-import") (part "MCP6001RT"))
    )
    (comp (ref "IC21")
      (value "MIC5504-3.3YM5")
      (footprint "eagle-import:SOT23-5")
      (fields (field (name "LCSC_PART") "C41348078"))
      (libsource (lib "eagle-import") (part "MIC5504-3.3YM5-TR"))
    )
    (comp (ref "PWR")
      (value "Green")
      (footprint "eagle-import:LED-0603")
      (fields (field (name "LCSC_PART") "C965804"))
      (libsource (lib "eagle-import") (part "LED-GREENLED-0603"))
    )
    (comp (ref "R109")
      (value "4.7K 1%")
      (footprint "eagle-import:0201")
      (fields (field (name "LCSC_PART") "C270346"))
      (libsource (lib "eagle-import") (part "4.7K-1%0201"))
    )
    (comp (ref "R121")
      (value "2.2K 1%")
      (footprint "eagle-import:0201")
      (fields (field (name "LCSC_PART") "C473508"))
      (libsource (lib "eagle-import") (part "2.2K-1%0201"))
    )
    (comp (ref "R124")
      (value "5.1K 1%")
      (footprint "eagle-import:0201")
      (fields (field (name "LCSC_PART") "C274341"))
      (libsource (lib "eagle-import") (part "5.1K-1%0201"))
    )
    (comp (ref "R125")
      (value "5.1K 1%")
      (footprint "eagle-import:0201")
      (fields (field (name "LCSC_PART") "C274341"))
      (libsource (lib "eagle-import") (part "5.1K-1%0201"))
    )
    (comp (ref "R126")
      (value "10K 1%")
      (footprint "eagle-import:0201")
      (fields (field (name "LCSC_PART") "C473048"))
      (libsource (lib "eagle-import") (part "10K-1%0201"))
    )
    (comp (ref "R127")
      (value "10K 1%")
      (footprint "eagle-import:0201")
      (fields (field (name "LCSC_PART") "C473048"))
      (libsource (lib "eagle-import") (part "10K-1%0201"))
    )
    (comp (ref "R131")
      (value "1M 1%")
      (footprint "eagle-import:0402")
      (fields (field (name "LCSC_PART") "C26083"))
      (libsource (lib "eagle-import") (part "1M-1%0402"))
    )
    (comp (ref "R147")
      (value "10K 1%")
      (footprint "eagle-import:0402")
      (fields (field (name "LCSC_PART") "C25744"))
      (libsource (lib "eagle-import") (part "10K-1%0402"))
    )
    (comp (ref "R149")
      (value "3.3K 1%")
      (footprint "eagle-import:_0603X4-1206")
      (fields (field (name "LCSC_PART") "C1734380"))
      (libsource (lib "eagle-import") (part "3.3K-1%_ARRAY0603X4-1206"))
    )
    (comp (ref "R151")
      (value "1K 1%")
      (footprint "eagle-import:0402")
      (fields (field (name "LCSC_PART") "C11702"))
      (libsource (lib "eagle-import") (part "1K-1%0402"))
    )
    (comp (ref "R152")
      (value "10R 1%")
      (footprint "eagle-import:0201")
      (fields (field (name "LCSC_PART") "C270817"))
      (libsource (lib "eagle-import") (part "10R-1%0201"))
    )
    (comp (ref "REF1")
      (value "LM4040B30FTA")
      (footprint "eagle-import:SOT23")
      (fields (field (name "LCSC_PART") "C460604"))
      (libsource (lib "eagle-import") (part "LM4040BXX"))
    )
    (comp (ref "USB1")
      (value "USB-TYPE-C-018")
      (footprint "eagle-import:USB-C")
      (fields (field (name "LCSC_PART") "C2927038"))
      (libsource (lib "eagle-import") (part "USB_C-THT"))
    )
    (comp (ref "VBUS")
      (value "TP")
      (footprint "eagle-import:TP")
      (libsource (lib "eagle-import") (part "TP"))
    )
    (comp (ref "VREF")
      (value "TP")
      (footprint "eagle-import:TP")
      (libsource (lib "eagle-import") (part "TP"))
    )
    (comp (ref "D1")
      (value "MBRA340T3G")
      (footprint "eagle-import:SMA_DO-214AC")
      (fields (field (name "LCSC_PART") "C26178"))
      (libsource (lib "eagle-import") (part "MBRA340T3G"))
    )
    (comp (ref "D2")
      (value "MBRA340T3G")
      (footprint "eagle-import:SMA_DO-214AC")
      (fields (field (name "LCSC_PART") "C26178"))
      (libsource (lib "eagle-import") (part "MBRA340T3G"))
    )
    (comp (ref "D3")
      (value "MBRA340T3G")
      (footprint "eagle-import:SMA_DO-214AC")
      (fields (field (name "LCSC_PART") "C26178"))
      (libsource (lib "eagle-import") (part "MBRA340T3G"))
    )
    (comp (ref "D4")
      (value "MBRA340T3G")
      (footprint "eagle-import:SMA_DO-214AC")
      (fields (field (name "LCSC_PART") "C26178"))
      (libsource (lib "eagle-import") (part "MBRA340T3G"))
    )
    (comp (ref "D5")
      (value "MBRA340T3G")
      (footprint "eagle-import:SMA_DO-214AC")
      (fields (field (name "LCSC_PART") "C26178"))
      (libsource (lib "eagle-import") (part "MBRA340T3G"))
    )
    (comp (ref "D6")
      (value "MBRA340T3G")
      (footprint "eagle-import:SMA_DO-214AC")
      (fields (field (name "LCSC_PART") "C26178"))
      (libsource (lib "eagle-import") (part "MBRA340T3G"))
    )
    (comp (ref "D7")
      (value "MBRA340T3G")
      (footprint "eagle-import:SMA_DO-214AC")
      (fields (field (name "LCSC_PART") "C26178"))
      (libsource (lib "eagle-import") (part "MBRA340T3G"))
    )
    (comp (ref "D8")
      (value "MBRA340T3G")
      (footprint "eagle-import:SMA_DO-214AC")
      (fields (field (name "LCSC_PART") "C26178"))
      (libsource (lib "eagle-import") (part "MBRA340T3G"))
    )
    (comp (ref "K1")
      (value "G2RL-1A-E DC12")
      (footprint "eagle-import:RELAY_G2RL-1A-E_DC5_OMR")
      (fields (field (name "LCSC_PART") "C1564126"))
      (libsource (lib "eagle-import") (part "G2RL-1A-E_DC12"))
    )
    (comp (ref "K2")
      (value "G2RL-1A-E DC12")
      (footprint "eagle-import:RELAY_G2RL-1A-E_DC5_OMR")
      (fields (field (name "LCSC_PART") "C1564126"))
      (libsource (lib "eagle-import") (part "G2RL-1A-E_DC12"))
    )
    (comp (ref "K3")
      (value "G2RL-1A-E DC12")
      (footprint "eagle-import:RELAY_G2RL-1A-E_DC5_OMR")
      (fields (field (name "LCSC_PART") "C1564126"))
      (libsource (lib "eagle-import") (part "G2RL-1A-E_DC12"))
    )
    (comp (ref "K4")
      (value "G2RL-1A-E DC12")
      (footprint "eagle-import:RELAY_G2RL-1A-E_DC5_OMR")
      (fields (field (name "LCSC_PART") "C1564126"))
      (libsource (lib "eagle-import") (part "G2RL-1A-E_DC12"))
    )
    (comp (ref "K5")
      (value "G2RL-1A-E DC12")
      (footprint "eagle-import:RELAY_G2RL-1A-E_DC5_OMR")
      (fields (field (name "LCSC_PART") "C1564126"))
      (libsource (lib "eagle-import") (part "G2RL-1A-E_DC12"))
    )
    (comp (ref "K6")
      (value "G2RL-1A-E DC12")
      (footprint "eagle-import:RELAY_G2RL-1A-E_DC5_OMR")
      (fields (field (name "LCSC_PART") "C1564126"))
      (libsource (lib "eagle-import") (part "G2RL-1A-E_DC12"))
    )
    (comp (ref "K7")
      (value "G2RL-1A-E DC12")
      (footprint "eagle-import:RELAY_G2RL-1A-E_DC5_OMR")
      (fields (field (name "LCSC_PART") "C1564126"))
      (libsource (lib "eagle-import") (part "G2RL-1A-E_DC12"))
    )
    (comp (ref "K8")
      (value "G2RL-1A-E DC12")
      (footprint "eagle-import:RELAY_G2RL-1A-E_DC5_OMR")
      (fields (field (name "LCSC_PART") "C1564126"))
      (libsource (lib "eagle-import") (part "G2RL-1A-E_DC12"))
    )
    (comp (ref "C106")
      (value "1nF 25V")
      (footprint "eagle-import:0201")
      (fields (field (name "LCSC_PART") "C7694325V"))
      (libsource (lib "eagle-import") (part "1NF-25V-0201"))
    )
    (comp (ref "C107")
      (value "1nF 25V")
      (footprint "eagle-import:0201")
      (fields (field (name "LCSC_PART") "C7694325V"))
      (libsource (lib "eagle-import") (part "1NF-25V-0201"))
    )
    (comp (ref "C108")
      (value "1nF 25V")
      (footprint "eagle-import:0201")
      (fields (field (name "LCSC_PART") "C7694325V"))
      (libsource (lib "eagle-import") (part "1NF-25V-0201"))
    )
    (comp (ref "C109")
      (value "1nF 25V")
      (footprint "eagle-import:0201")
      (fields (field (name "LCSC_PART") "C7694325V"))
      (libsource (lib "eagle-import") (part "1NF-25V-0201"))
    )
    (comp (ref "C110")
      (value "1nF 25V")
      (footprint "eagle-import:0201")
      (fields (field (name "LCSC_PART") "C7694325V"))
      (libsource (lib "eagle-import") (part "1NF-25V-0201"))
    )
    (comp (ref "C111")
      (value "1nF 25V")
      (footprint "eagle-import:0201")
      (fields (field (name "LCSC_PART") "C7694325V"))
      (libsource (lib "eagle-import") (part "1NF-25V-0201"))
    )
    (comp (ref "C112")
      (value "1nF 25V")
      (footprint "eagle-import:0201")
      (fields (field (name "LCSC_PART") "C7694325V"))
      (libsource (lib "eagle-import") (part "1NF-25V-0201"))
    )
    (comp (ref "C113")
      (value "1nF 25V")
      (footprint "eagle-import:0201")
      (fields (field (name "LCSC_PART") "C7694325V"))
      (libsource (lib "eagle-import") (part "1NF-25V-0201"))
    )
    (comp (ref "OPT1")
      (value "ACPL-247-500E")
      (footprint "eagle-import:SO16")
      (fields (field (name "LCSC_PART") "C188681"))
      (libsource (lib "eagle-import") (part "ACPL-2471"))
    )
    (comp (ref "OPT2")
      (value "ACPL-247-500E")
      (footprint "eagle-import:SO16")
      (fields (field (name "LCSC_PART") "C188681"))
      (libsource (lib "eagle-import") (part "ACPL-2471"))
    )
    (comp (ref "R59")
      (value "1K 1%")
      (footprint "eagle-import:0201")
      (fields (field (name "LCSC_PART") "C270365"))
      (libsource (lib "eagle-import") (part "1K-1%0201"))
    )
    (comp (ref "R63")
      (value "1K 1%")
      (footprint "eagle-import:_0603X4-1206")
      (fields (field (name "LCSC_PART") "C110021"))
      (libsource (lib "eagle-import") (part "1K-1%_ARRAY0603X4-1206"))
    )
    (comp (ref "R64")
      (value "1K 1%")
      (footprint "eagle-import:_0603X4-1206")
      (fields (field (name "LCSC_PART") "C110021"))
      (libsource (lib "eagle-import") (part "1K-1%_ARRAY0603X4-1206"))
    )
    (comp (ref "R89")
      (value "10K 1%")
      (footprint "eagle-import:_0603X4-1206")
      (fields (field (name "LCSC_PART") "C110924"))
      (libsource (lib "eagle-import") (part "10K-1%_ARRAY0603X4-1206"))
    )
    (comp (ref "R90")
      (value "10K 1%")
      (footprint "eagle-import:_0603X4-1206")
      (fields (field (name "LCSC_PART") "C110924"))
      (libsource (lib "eagle-import") (part "10K-1%_ARRAY0603X4-1206"))
    )
    (comp (ref "R153")
      (value "1K 1%")
      (footprint "eagle-import:0201")
      (fields (field (name "LCSC_PART") "C270365"))
      (libsource (lib "eagle-import") (part "1K-1%0201"))
    )
    (comp (ref "R154")
      (value "1K 1%")
      (footprint "eagle-import:0201")
      (fields (field (name "LCSC_PART") "C270365"))
      (libsource (lib "eagle-import") (part "1K-1%0201"))
    )
    (comp (ref "R155")
      (value "1K 1%")
      (footprint "eagle-import:0201")
      (fields (field (name "LCSC_PART") "C270365"))
      (libsource (lib "eagle-import") (part "1K-1%0201"))
    )
    (comp (ref "R156")
      (value "1K 1%")
      (footprint "eagle-import:0201")
      (fields (field (name "LCSC_PART") "C270365"))
      (libsource (lib "eagle-import") (part "1K-1%0201"))
    )
    (comp (ref "R157")
      (value "1K 1%")
      (footprint "eagle-import:0201")
      (fields (field (name "LCSC_PART") "C270365"))
      (libsource (lib "eagle-import") (part "1K-1%0201"))
    )
    (comp (ref "R158")
      (value "1K 1%")
      (footprint "eagle-import:0201")
      (fields (field (name "LCSC_PART") "C270365"))
      (libsource (lib "eagle-import") (part "1K-1%0201"))
    )
    (comp (ref "R159")
      (value "1K 1%")
      (footprint "eagle-import:0201")
      (fields (field (name "LCSC_PART") "C270365"))
      (libsource (lib "eagle-import") (part "1K-1%0201"))
    )
    (comp (ref "C19")
      (value "100nF 25V")
      (footprint "eagle-import:0402")
      (fields (field (name "LCSC_PART") "C56392"))
      (libsource (lib "eagle-import") (part "100NF-25V-0402"))
    )
    (comp (ref "C20")
      (value "100nF 25V")
      (footprint "eagle-import:0402")
      (fields (field (name "LCSC_PART") "C56392"))
      (libsource (lib "eagle-import") (part "100NF-25V-0402"))
    )
    (comp (ref "C33")
      (value "100nF 25V")
      (footprint "eagle-import:0402")
      (fields (field (name "LCSC_PART") "C56392"))
      (libsource (lib "eagle-import") (part "100NF-25V-0402"))
    )
    (comp (ref "C34")
      (value "100nF 25V")
      (footprint "eagle-import:0402")
      (fields (field (name "LCSC_PART") "C56392"))
      (libsource (lib "eagle-import") (part "100NF-25V-0402"))
    )
    (comp (ref "C103")
      (value "100nF 25V")
      (footprint "eagle-import:0201")
      (fields (field (name "LCSC_PART") "C76939"))
      (libsource (lib "eagle-import") (part "100NF-25V-0201"))
    )
    (comp (ref "DAT")
      (value "Blue")
      (footprint "eagle-import:LED-0603")
      (fields (field (name "LCSC_PART") "C965807"))
      (libsource (lib "eagle-import") (part "LED-BLUELED-0603"))
    )
    (comp (ref "IC3")
      (value "ULN2803AFWG")
      (footprint "eagle-import:SO18")
      (fields (field (name "LCSC_PART") "C845537"))
      (libsource (lib "eagle-import") (part "ULN2803"))
    )
    (comp (ref "IC4")
      (value "MCP23017T-E/ML")
      (footprint "eagle-import:QFN28[6X6]ML")
      (fields (field (name "LCSC_PART") "C629439"))
      (libsource (lib "eagle-import") (part "MCP23017-E/ML"))
    )
    (comp (ref "IC9")
      (value "SN74HC151PWR")
      (footprint "eagle-import:TSSOP16")
      (fields (field (name "LCSC_PART") "C2653837"))
      (libsource (lib "eagle-import") (part "SN74HC151PWR"))
    )
    (comp (ref "IC22")
      (value "MCP6001RT-I/OT")
      (footprint "eagle-import:SOT23-5")
      (fields (field (name "LCSC_PART") "C154973"))
      (libsource (lib "eagle-import") (part "MCP6001RT"))
    )
    (comp (ref "R17")
      (value "330R 1% 1W")
      (footprint "eagle-import:2512")
      (fields (field (name "LCSC_PART") "C620880"))
      (libsource (lib "eagle-import") (part "330R-1%-2512"))
    )
    (comp (ref "R18")
      (value "330R 1% 1W")
      (footprint "eagle-import:2512")
      (fields (field (name "LCSC_PART") "C620880"))
      (libsource (lib "eagle-import") (part "330R-1%-2512"))
    )
    (comp (ref "R19")
      (value "330R 1% 1W")
      (footprint "eagle-import:2512")
      (fields (field (name "LCSC_PART") "C620880"))
      (libsource (lib "eagle-import") (part "330R-1%-2512"))
    )
    (comp (ref "R20")
      (value "330R 1% 1W")
      (footprint "eagle-import:2512")
      (fields (field (name "LCSC_PART") "C620880"))
      (libsource (lib "eagle-import") (part "330R-1%-2512"))
    )
    (comp (ref "R21")
      (value "330R 1% 1W")
      (footprint "eagle-import:2512")
      (fields (field (name "LCSC_PART") "C620880"))
      (libsource (lib "eagle-import") (part "330R-1%-2512"))
    )
    (comp (ref "R22")
      (value "330R 1% 1W")
      (footprint "eagle-import:2512")
      (fields (field (name "LCSC_PART") "C620880"))
      (libsource (lib "eagle-import") (part "330R-1%-2512"))
    )
    (comp (ref "R23")
      (value "330R 1% 1W")
      (footprint "eagle-import:2512")
      (fields (field (name "LCSC_PART") "C620880"))
      (libsource (lib "eagle-import") (part "330R-1%-2512"))
    )
    (comp (ref "R24")
      (value "330R 1% 1W")
      (footprint "eagle-import:2512")
      (fields (field (name "LCSC_PART") "C620880"))
      (libsource (lib "eagle-import") (part "330R-1%-2512"))
    )
    (comp (ref "R57")
      (value "0R 1%")
      (footprint "eagle-import:0402")
      (fields (field (name "LCSC_PART") "C17168"))
      (libsource (lib "eagle-import") (part "0R0402"))
    )
    (comp (ref "R58")
      (value "DNI")
      (footprint "eagle-import:0402")
      (libsource (lib "eagle-import") (part "R0402"))
    )
    (comp (ref "R91")
      (value "0R 1%")
      (footprint "eagle-import:0402")
      (fields (field (name "LCSC_PART") "C17168"))
      (libsource (lib "eagle-import") (part "0R0402"))
    )
    (comp (ref "R92")
      (value "DNI")
      (footprint "eagle-import:0402")
      (libsource (lib "eagle-import") (part "R0402"))
    )
    (comp (ref "R93")
      (value "10K 1%")
      (footprint "eagle-import:_0603X4-1206")
      (fields (field (name "LCSC_PART") "C110924"))
      (libsource (lib "eagle-import") (part "10K-1%_ARRAY0603X4-1206"))
    )
    (comp (ref "R122")
      (value "1K 1%")
      (footprint "eagle-import:0402")
      (fields (field (name "LCSC_PART") "C11702"))
      (libsource (lib "eagle-import") (part "1K-1%0402"))
    )
    (comp (ref "REL0")
      (value "TP")
      (footprint "eagle-import:TP")
      (libsource (lib "eagle-import") (part "TP"))
    )
    (comp (ref "REL1")
      (value "TP")
      (footprint "eagle-import:TP")
      (libsource (lib "eagle-import") (part "TP"))
    )
    (comp (ref "REL2")
      (value "TP")
      (footprint "eagle-import:TP")
      (libsource (lib "eagle-import") (part "TP"))
    )
    (comp (ref "REL3")
      (value "TP")
      (footprint "eagle-import:TP")
      (libsource (lib "eagle-import") (part "TP"))
    )
    (comp (ref "REL4")
      (value "TP")
      (footprint "eagle-import:TP")
      (libsource (lib "eagle-import") (part "TP"))
    )
    (comp (ref "REL5")
      (value "TP")
      (footprint "eagle-import:TP")
      (libsource (lib "eagle-import") (part "TP"))
    )
    (comp (ref "REL6")
      (value "TP")
      (footprint "eagle-import:TP")
      (libsource (lib "eagle-import") (part "TP"))
    )
    (comp (ref "REL7")
      (value "TP")
      (footprint "eagle-import:TP")
      (libsource (lib "eagle-import") (part "TP"))
    )
    (comp (ref "C24")
      (value "33nF 50V")
      (footprint "eagle-import:0805")
      (fields (field (name "LCSC_PART") "C107150"))
      (libsource (lib "eagle-import") (part "33NF-50V0805"))
    )
    (comp (ref "C25")
      (value "33nF 50V")
      (footprint "eagle-import:0805")
      (fields (field (name "LCSC_PART") "C107150"))
      (libsource (lib "eagle-import") (part "33NF-50V0805"))
    )
    (comp (ref "C26")
      (value "33nF 50V")
      (footprint "eagle-import:0805")
      (fields (field (name "LCSC_PART") "C107150"))
      (libsource (lib "eagle-import") (part "33NF-50V0805"))
    )
    (comp (ref "C27")
      (value "33nF 50V")
      (footprint "eagle-import:0805")
      (fields (field (name "LCSC_PART") "C107150"))
      (libsource (lib "eagle-import") (part "33NF-50V0805"))
    )
    (comp (ref "C28")
      (value "33nF 50V")
      (footprint "eagle-import:0805")
      (fields (field (name "LCSC_PART") "C107150"))
      (libsource (lib "eagle-import") (part "33NF-50V0805"))
    )
    (comp (ref "C29")
      (value "33nF 50V")
      (footprint "eagle-import:0805")
      (fields (field (name "LCSC_PART") "C107150"))
      (libsource (lib "eagle-import") (part "33NF-50V0805"))
    )
    (comp (ref "C30")
      (value "33nF 50V")
      (footprint "eagle-import:0805")
      (fields (field (name "LCSC_PART") "C107150"))
      (libsource (lib "eagle-import") (part "33NF-50V0805"))
    )
    (comp (ref "C31")
      (value "33nF 50V")
      (footprint "eagle-import:0805")
      (fields (field (name "LCSC_PART") "C107150"))
      (libsource (lib "eagle-import") (part "33NF-50V0805"))
    )
    (comp (ref "C32")
      (value "33nF 50V")
      (footprint "eagle-import:0805")
      (fields (field (name "LCSC_PART") "C107150"))
      (libsource (lib "eagle-import") (part "33NF-50V0805"))
    )
    (comp (ref "C36")
      (value "33nF 50V")
      (footprint "eagle-import:0805")
      (fields (field (name "LCSC_PART") "C107150"))
      (libsource (lib "eagle-import") (part "33NF-50V0805"))
    )
    (comp (ref "C37")
      (value "33nF 50V")
      (footprint "eagle-import:0805")
      (fields (field (name "LCSC_PART") "C107150"))
      (libsource (lib "eagle-import") (part "33NF-50V0805"))
    )
    (comp (ref "C38")
      (value "33nF 50V")
      (footprint "eagle-import:0805")
      (fields (field (name "LCSC_PART") "C107150"))
      (libsource (lib "eagle-import") (part "33NF-50V0805"))
    )
    (comp (ref "C39")
      (value "33nF 50V")
      (footprint "eagle-import:0805")
      (fields (field (name "LCSC_PART") "C107150"))
      (libsource (lib "eagle-import") (part "33NF-50V0805"))
    )
    (comp (ref "C40")
      (value "33nF 50V")
      (footprint "eagle-import:0805")
      (fields (field (name "LCSC_PART") "C107150"))
      (libsource (lib "eagle-import") (part "33NF-50V0805"))
    )
    (comp (ref "C41")
      (value "33nF 50V")
      (footprint "eagle-import:0805")
      (fields (field (name "LCSC_PART") "C107150"))
      (libsource (lib "eagle-import") (part "33NF-50V0805"))
    )
    (comp (ref "C42")
      (value "33nF 50V")
      (footprint "eagle-import:0805")
      (fields (field (name "LCSC_PART") "C107150"))
      (libsource (lib "eagle-import") (part "33NF-50V0805"))
    )
    (comp (ref "C43")
      (value "33nF 50V")
      (footprint "eagle-import:0805")
      (fields (field (name "LCSC_PART") "C107150"))
      (libsource (lib "eagle-import") (part "33NF-50V0805"))
    )
    (comp (ref "C44")
      (value "33nF 50V")
      (footprint "eagle-import:0805")
      (fields (field (name "LCSC_PART") "C107150"))
      (libsource (lib "eagle-import") (part "33NF-50V0805"))
    )
    (comp (ref "C48")
      (value "33nF 50V")
      (footprint "eagle-import:0805")
      (fields (field (name "LCSC_PART") "C107150"))
      (libsource (lib "eagle-import") (part "33NF-50V0805"))
    )
    (comp (ref "C49")
      (value "33nF 50V")
      (footprint "eagle-import:0805")
      (fields (field (name "LCSC_PART") "C107150"))
      (libsource (lib "eagle-import") (part "33NF-50V0805"))
    )
    (comp (ref "C50")
      (value "33nF 50V")
      (footprint "eagle-import:0805")
      (fields (field (name "LCSC_PART") "C107150"))
      (libsource (lib "eagle-import") (part "33NF-50V0805"))
    )
    (comp (ref "C54")
      (value "33nF 50V")
      (footprint "eagle-import:0805")
      (fields (field (name "LCSC_PART") "C107150"))
      (libsource (lib "eagle-import") (part "33NF-50V0805"))
    )
    (comp (ref "C55")
      (value "33nF 50V")
      (footprint "eagle-import:0805")
      (fields (field (name "LCSC_PART") "C107150"))
      (libsource (lib "eagle-import") (part "33NF-50V0805"))
    )
    (comp (ref "C56")
      (value "33nF 50V")
      (footprint "eagle-import:0805")
      (fields (field (name "LCSC_PART") "C107150"))
      (libsource (lib "eagle-import") (part "33NF-50V0805"))
    )
    (comp (ref "IC6")
      (value "HLW8032")
      (footprint "eagle-import:SO8")
      (fields (field (name "LCSC_PART") "C128023"))
      (libsource (lib "eagle-import") (part "HLW8032"))
    )
    (comp (ref "IC7")
      (value "HLW8032")
      (footprint "eagle-import:SO8")
      (fields (field (name "LCSC_PART") "C128023"))
      (libsource (lib "eagle-import") (part "HLW8032"))
    )
    (comp (ref "IC8")
      (value "HLW8032")
      (footprint "eagle-import:SO8")
      (fields (field (name "LCSC_PART") "C128023"))
      (libsource (lib "eagle-import") (part "HLW8032"))
    )
    (comp (ref "IC10")
      (value "HLW8032")
      (footprint "eagle-import:SO8")
      (fields (field (name "LCSC_PART") "C128023"))
      (libsource (lib "eagle-import") (part "HLW8032"))
    )
    (comp (ref "IC11")
      (value "HLW8032")
      (footprint "eagle-import:SO8")
      (fields (field (name "LCSC_PART") "C128023"))
      (libsource (lib "eagle-import") (part "HLW8032"))
    )
    (comp (ref "IC12")
      (value "HLW8032")
      (footprint "eagle-import:SO8")
      (fields (field (name "LCSC_PART") "C128023"))
      (libsource (lib "eagle-import") (part "HLW8032"))
    )
    (comp (ref "IC14")
      (value "HLW8032")
      (footprint "eagle-import:SO8")
      (fields (field (name "LCSC_PART") "C128023"))
      (libsource (lib "eagle-import") (part "HLW8032"))
    )
    (comp (ref "IC16")
      (value "HLW8032")
      (footprint "eagle-import:SO8")
      (fields (field (name "LCSC_PART") "C128023"))
      (libsource (lib "eagle-import") (part "HLW8032"))
    )
    (comp (ref "L_OUT1")
      (value "MOUNT-PAD-ROUND2.8")
      (footprint "eagle-import:2,8-PAD")
      (libsource (lib "eagle-import") (part "MOUNT-PAD-ROUND2.8"))
    )
    (comp (ref "L_OUT2")
      (value "MOUNT-PAD-ROUND2.8")
      (footprint "eagle-import:2,8-PAD")
      (libsource (lib "eagle-import") (part "MOUNT-PAD-ROUND2.8"))
    )
    (comp (ref "L_OUT3")
      (value "MOUNT-PAD-ROUND2.8")
      (footprint "eagle-import:2,8-PAD")
      (libsource (lib "eagle-import") (part "MOUNT-PAD-ROUND2.8"))
    )
    (comp (ref "L_OUT4")
      (value "MOUNT-PAD-ROUND2.8")
      (footprint "eagle-import:2,8-PAD")
      (libsource (lib "eagle-import") (part "MOUNT-PAD-ROUND2.8"))
    )
    (comp (ref "L_OUT5")
      (value "MOUNT-PAD-ROUND2.8")
      (footprint "eagle-import:2,8-PAD")
      (libsource (lib "eagle-import") (part "MOUNT-PAD-ROUND2.8"))
    )
    (comp (ref "L_OUT6")
      (value "MOUNT-PAD-ROUND2.8")
      (footprint "eagle-import:2,8-PAD")
      (libsource (lib "eagle-import") (part "MOUNT-PAD-ROUND2.8"))
    )
    (comp (ref "L_OUT7")
      (value "MOUNT-PAD-ROUND2.8")
      (footprint "eagle-import:2,8-PAD")
      (libsource (lib "eagle-import") (part "MOUNT-PAD-ROUND2.8"))
    )
    (comp (ref "L_OUT8")
      (value "MOUNT-PAD-ROUND2.8")
      (footprint "eagle-import:2,8-PAD")
      (libsource (lib "eagle-import") (part "MOUNT-PAD-ROUND2.8"))
    )
    (comp (ref "N_OUT1")
      (value "MOUNT-PAD-ROUND2.8")
      (footprint "eagle-import:2,8-PAD")
      (libsource (lib "eagle-import") (part "MOUNT-PAD-ROUND2.8"))
    )
    (comp (ref "N_OUT2")
      (value "MOUNT-PAD-ROUND2.8")
      (footprint "eagle-import:2,8-PAD")
      (libsource (lib "eagle-import") (part "MOUNT-PAD-ROUND2.8"))
    )
    (comp (ref "N_OUT3")
      (value "MOUNT-PAD-ROUND2.8")
      (footprint "eagle-import:2,8-PAD")
      (libsource (lib "eagle-import") (part "MOUNT-PAD-ROUND2.8"))
    )
    (comp (ref "N_OUT4")
      (value "MOUNT-PAD-ROUND2.8")
      (footprint "eagle-import:2,8-PAD")
      (libsource (lib "eagle-import") (part "MOUNT-PAD-ROUND2.8"))
    )
    (comp (ref "N_OUT5")
      (value "MOUNT-PAD-ROUND2.8")
      (footprint "eagle-import:2,8-PAD")
      (libsource (lib "eagle-import") (part "MOUNT-PAD-ROUND2.8"))
    )
    (comp (ref "N_OUT6")
      (value "MOUNT-PAD-ROUND2.8")
      (footprint "eagle-import:2,8-PAD")
      (libsource (lib "eagle-import") (part "MOUNT-PAD-ROUND2.8"))
    )
    (comp (ref "N_OUT7")
      (value "MOUNT-PAD-ROUND2.8")
      (footprint "eagle-import:2,8-PAD")
      (libsource (lib "eagle-import") (part "MOUNT-PAD-ROUND2.8"))
    )
    (comp (ref "N_OUT8")
      (value "MOUNT-PAD-ROUND2.8")
      (footprint "eagle-import:2,8-PAD")
      (libsource (lib "eagle-import") (part "MOUNT-PAD-ROUND2.8"))
    )
    (comp (ref "R25")
      (value "0.002R 1%")
      (footprint "eagle-import:2512")
      (fields (field (name "LCSC_PART") "C728320"))
      (libsource (lib "eagle-import") (part "0.002R-1%2512"))
    )
    (comp (ref "R26")
      (value "0.002R 1%")
      (footprint "eagle-import:2512")
      (fields (field (name "LCSC_PART") "C728320"))
      (libsource (lib "eagle-import") (part "0.002R-1%2512"))
    )
    (comp (ref "R27")
      (value "0.002R 1%")
      (footprint "eagle-import:2512")
      (fields (field (name "LCSC_PART") "C728320"))
      (libsource (lib "eagle-import") (part "0.002R-1%2512"))
    )
    (comp (ref "R28")
      (value "0.002R 1%")
      (footprint "eagle-import:2512")
      (fields (field (name "LCSC_PART") "C728320"))
      (libsource (lib "eagle-import") (part "0.002R-1%2512"))
    )
    (comp (ref "R29")
      (value "0.002R 1%")
      (footprint "eagle-import:2512")
      (fields (field (name "LCSC_PART") "C728320"))
      (libsource (lib "eagle-import") (part "0.002R-1%2512"))
    )
    (comp (ref "R30")
      (value "0.002R 1%")
      (footprint "eagle-import:2512")
      (fields (field (name "LCSC_PART") "C728320"))
      (libsource (lib "eagle-import") (part "0.002R-1%2512"))
    )
    (comp (ref "R31")
      (value "0.002R 1%")
      (footprint "eagle-import:2512")
      (fields (field (name "LCSC_PART") "C728320"))
      (libsource (lib "eagle-import") (part "0.002R-1%2512"))
    )
    (comp (ref "R32")
      (value "0.002R 1%")
      (footprint "eagle-import:2512")
      (fields (field (name "LCSC_PART") "C728320"))
      (libsource (lib "eagle-import") (part "0.002R-1%2512"))
    )
    (comp (ref "R33")
      (value "1K 1%")
      (footprint "eagle-import:0805")
      (fields (field (name "LCSC_PART") "C17513"))
      (libsource (lib "eagle-import") (part "1K-1%0805"))
    )
    (comp (ref "R34")
      (value "1K 1%")
      (footprint "eagle-import:0805")
      (fields (field (name "LCSC_PART") "C17513"))
      (libsource (lib "eagle-import") (part "1K-1%0805"))
    )
    (comp (ref "R35")
      (value "0.002R 1%")
      (footprint "eagle-import:2512")
      (fields (field (name "LCSC_PART") "C728320"))
      (libsource (lib "eagle-import") (part "0.002R-1%2512"))
    )
    (comp (ref "R36")
      (value "470K 1%")
      (footprint "eagle-import:0805")
      (fields (field (name "LCSC_PART") "C17709"))
      (libsource (lib "eagle-import") (part "470K-1%0805"))
    )
    (comp (ref "R37")
      (value "470K 1%")
      (footprint "eagle-import:0805")
      (fields (field (name "LCSC_PART") "C17709"))
      (libsource (lib "eagle-import") (part "470K-1%0805"))
    )
    (comp (ref "R38")
      (value "470K 1%")
      (footprint "eagle-import:0805")
      (fields (field (name "LCSC_PART") "C17709"))
      (libsource (lib "eagle-import") (part "470K-1%0805"))
    )
    (comp (ref "R39")
      (value "470K 1%")
      (footprint "eagle-import:0805")
      (fields (field (name "LCSC_PART") "C17709"))
      (libsource (lib "eagle-import") (part "470K-1%0805"))
    )
    (comp (ref "R40")
      (value "1K 1%")
      (footprint "eagle-import:0805")
      (fields (field (name "LCSC_PART") "C17513"))
      (libsource (lib "eagle-import") (part "1K-1%0805"))
    )
    (comp (ref "R41")
      (value "1K 1%")
      (footprint "eagle-import:0805")
      (fields (field (name "LCSC_PART") "C17513"))
      (libsource (lib "eagle-import") (part "1K-1%0805"))
    )
    (comp (ref "R42")
      (value "1K 1%")
      (footprint "eagle-import:0805")
      (fields (field (name "LCSC_PART") "C17513"))
      (libsource (lib "eagle-import") (part "1K-1%0805"))
    )
    (comp (ref "R43")
      (value "0.002R 1%")
      (footprint "eagle-import:2512")
      (fields (field (name "LCSC_PART") "C728320"))
      (libsource (lib "eagle-import") (part "0.002R-1%2512"))
    )
    (comp (ref "R44")
      (value "470K 1%")
      (footprint "eagle-import:0805")
      (fields (field (name "LCSC_PART") "C17709"))
      (libsource (lib "eagle-import") (part "470K-1%0805"))
    )
    (comp (ref "R45")
      (value "470K 1%")
      (footprint "eagle-import:0805")
      (fields (field (name "LCSC_PART") "C17709"))
      (libsource (lib "eagle-import") (part "470K-1%0805"))
    )
    (comp (ref "R46")
      (value "470K 1%")
      (footprint "eagle-import:0805")
      (fields (field (name "LCSC_PART") "C17709"))
      (libsource (lib "eagle-import") (part "470K-1%0805"))
    )
    (comp (ref "R47")
      (value "470K 1%")
      (footprint "eagle-import:0805")
      (fields (field (name "LCSC_PART") "C17709"))
      (libsource (lib "eagle-import") (part "470K-1%0805"))
    )
    (comp (ref "R48")
      (value "1K 1%")
      (footprint "eagle-import:0805")
      (fields (field (name "LCSC_PART") "C17513"))
      (libsource (lib "eagle-import") (part "1K-1%0805"))
    )
    (comp (ref "R49")
      (value "1K 1%")
      (footprint "eagle-import:0805")
      (fields (field (name "LCSC_PART") "C17513"))
      (libsource (lib "eagle-import") (part "1K-1%0805"))
    )
    (comp (ref "R50")
      (value "1K 1%")
      (footprint "eagle-import:0805")
      (fields (field (name "LCSC_PART") "C17513"))
      (libsource (lib "eagle-import") (part "1K-1%0805"))
    )
    (comp (ref "R51")
      (value "0.002R 1%")
      (footprint "eagle-import:2512")
      (fields (field (name "LCSC_PART") "C728320"))
      (libsource (lib "eagle-import") (part "0.002R-1%2512"))
    )
    (comp (ref "R52")
      (value "470K 1%")
      (footprint "eagle-import:0805")
      (fields (field (name "LCSC_PART") "C17709"))
      (libsource (lib "eagle-import") (part "470K-1%0805"))
    )
    (comp (ref "R53")
      (value "470K 1%")
      (footprint "eagle-import:0805")
      (fields (field (name "LCSC_PART") "C17709"))
      (libsource (lib "eagle-import") (part "470K-1%0805"))
    )
    (comp (ref "R54")
      (value "470K 1%")
      (footprint "eagle-import:0805")
      (fields (field (name "LCSC_PART") "C17709"))
      (libsource (lib "eagle-import") (part "470K-1%0805"))
    )
    (comp (ref "R55")
      (value "470K 1%")
      (footprint "eagle-import:0805")
      (fields (field (name "LCSC_PART") "C17709"))
      (libsource (lib "eagle-import") (part "470K-1%0805"))
    )
    (comp (ref "R56")
      (value "1K 1%")
      (footprint "eagle-import:0805")
      (fields (field (name "LCSC_PART") "C17513"))
      (libsource (lib "eagle-import") (part "1K-1%0805"))
    )
    (comp (ref "R65")
      (value "1K 1%")
      (footprint "eagle-import:0805")
      (fields (field (name "LCSC_PART") "C17513"))
      (libsource (lib "eagle-import") (part "1K-1%0805"))
    )
    (comp (ref "R66")
      (value "1K 1%")
      (footprint "eagle-import:0805")
      (fields (field (name "LCSC_PART") "C17513"))
      (libsource (lib "eagle-import") (part "1K-1%0805"))
    )
    (comp (ref "R67")
      (value "0.002R 1%")
      (footprint "eagle-import:2512")
      (fields (field (name "LCSC_PART") "C728320"))
      (libsource (lib "eagle-import") (part "0.002R-1%2512"))
    )
    (comp (ref "R68")
      (value "470K 1%")
      (footprint "eagle-import:0805")
      (fields (field (name "LCSC_PART") "C17709"))
      (libsource (lib "eagle-import") (part "470K-1%0805"))
    )
    (comp (ref "R69")
      (value "470K 1%")
      (footprint "eagle-import:0805")
      (fields (field (name "LCSC_PART") "C17709"))
      (libsource (lib "eagle-import") (part "470K-1%0805"))
    )
    (comp (ref "R70")
      (value "470K 1%")
      (footprint "eagle-import:0805")
      (fields (field (name "LCSC_PART") "C17709"))
      (libsource (lib "eagle-import") (part "470K-1%0805"))
    )
    (comp (ref "R71")
      (value "470K 1%")
      (footprint "eagle-import:0805")
      (fields (field (name "LCSC_PART") "C17709"))
      (libsource (lib "eagle-import") (part "470K-1%0805"))
    )
    (comp (ref "R72")
      (value "1K 1%")
      (footprint "eagle-import:0805")
      (fields (field (name "LCSC_PART") "C17513"))
      (libsource (lib "eagle-import") (part "1K-1%0805"))
    )
    (comp (ref "R73")
      (value "1K 1%")
      (footprint "eagle-import:0805")
      (fields (field (name "LCSC_PART") "C17513"))
      (libsource (lib "eagle-import") (part "1K-1%0805"))
    )
    (comp (ref "R74")
      (value "1K 1%")
      (footprint "eagle-import:0805")
      (fields (field (name "LCSC_PART") "C17513"))
      (libsource (lib "eagle-import") (part "1K-1%0805"))
    )
    (comp (ref "R75")
      (value "0.002R 1%")
      (footprint "eagle-import:2512")
      (fields (field (name "LCSC_PART") "C728320"))
      (libsource (lib "eagle-import") (part "0.002R-1%2512"))
    )
    (comp (ref "R76")
      (value "470K 1%")
      (footprint "eagle-import:0805")
      (fields (field (name "LCSC_PART") "C17709"))
      (libsource (lib "eagle-import") (part "470K-1%0805"))
    )
    (comp (ref "R77")
      (value "470K 1%")
      (footprint "eagle-import:0805")
      (fields (field (name "LCSC_PART") "C17709"))
      (libsource (lib "eagle-import") (part "470K-1%0805"))
    )
    (comp (ref "R78")
      (value "470K 1%")
      (footprint "eagle-import:0805")
      (fields (field (name "LCSC_PART") "C17709"))
      (libsource (lib "eagle-import") (part "470K-1%0805"))
    )
    (comp (ref "R79")
      (value "470K 1%")
      (footprint "eagle-import:0805")
      (fields (field (name "LCSC_PART") "C17709"))
      (libsource (lib "eagle-import") (part "470K-1%0805"))
    )
    (comp (ref "R80")
      (value "1K 1%")
      (footprint "eagle-import:0805")
      (fields (field (name "LCSC_PART") "C17513"))
      (libsource (lib "eagle-import") (part "1K-1%0805"))
    )
    (comp (ref "R81")
      (value "1K 1%")
      (footprint "eagle-import:0805")
      (fields (field (name "LCSC_PART") "C17513"))
      (libsource (lib "eagle-import") (part "1K-1%0805"))
    )
    (comp (ref "R82")
      (value "1K 1%")
      (footprint "eagle-import:0805")
      (fields (field (name "LCSC_PART") "C17513"))
      (libsource (lib "eagle-import") (part "1K-1%0805"))
    )
    (comp (ref "R83")
      (value "0.002R 1%")
      (footprint "eagle-import:2512")
      (fields (field (name "LCSC_PART") "C728320"))
      (libsource (lib "eagle-import") (part "0.002R-1%2512"))
    )
    (comp (ref "R84")
      (value "470K 1%")
      (footprint "eagle-import:0805")
      (fields (field (name "LCSC_PART") "C17709"))
      (libsource (lib "eagle-import") (part "470K-1%0805"))
    )
    (comp (ref "R85")
      (value "470K 1%")
      (footprint "eagle-import:0805")
      (fields (field (name "LCSC_PART") "C17709"))
      (libsource (lib "eagle-import") (part "470K-1%0805"))
    )
    (comp (ref "R86")
      (value "470K 1%")
      (footprint "eagle-import:0805")
      (fields (field (name "LCSC_PART") "C17709"))
      (libsource (lib "eagle-import") (part "470K-1%0805"))
    )
    (comp (ref "R87")
      (value "470K 1%")
      (footprint "eagle-import:0805")
      (fields (field (name "LCSC_PART") "C17709"))
      (libsource (lib "eagle-import") (part "470K-1%0805"))
    )
    (comp (ref "R88")
      (value "1K 1%")
      (footprint "eagle-import:0805")
      (fields (field (name "LCSC_PART") "C17513"))
      (libsource (lib "eagle-import") (part "1K-1%0805"))
    )
    (comp (ref "R97")
      (value "1K 1%")
      (footprint "eagle-import:0805")
      (fields (field (name "LCSC_PART") "C17513"))
      (libsource (lib "eagle-import") (part "1K-1%0805"))
    )
    (comp (ref "R98")
      (value "1K 1%")
      (footprint "eagle-import:0805")
      (fields (field (name "LCSC_PART") "C17513"))
      (libsource (lib "eagle-import") (part "1K-1%0805"))
    )
    (comp (ref "R99")
      (value "0.002R 1%")
      (footprint "eagle-import:2512")
      (fields (field (name "LCSC_PART") "C728320"))
      (libsource (lib "eagle-import") (part "0.002R-1%2512"))
    )
    (comp (ref "R100")
      (value "470K 1%")
      (footprint "eagle-import:0805")
      (fields (field (name "LCSC_PART") "C17709"))
      (libsource (lib "eagle-import") (part "470K-1%0805"))
    )
    (comp (ref "R101")
      (value "470K 1%")
      (footprint "eagle-import:0805")
      (fields (field (name "LCSC_PART") "C17709"))
      (libsource (lib "eagle-import") (part "470K-1%0805"))
    )
    (comp (ref "R102")
      (value "470K 1%")
      (footprint "eagle-import:0805")
      (fields (field (name "LCSC_PART") "C17709"))
      (libsource (lib "eagle-import") (part "470K-1%0805"))
    )
    (comp (ref "R103")
      (value "470K 1%")
      (footprint "eagle-import:0805")
      (fields (field (name "LCSC_PART") "C17709"))
      (libsource (lib "eagle-import") (part "470K-1%0805"))
    )
    (comp (ref "R104")
      (value "1K 1%")
      (footprint "eagle-import:0805")
      (fields (field (name "LCSC_PART") "C17513"))
      (libsource (lib "eagle-import") (part "1K-1%0805"))
    )
    (comp (ref "R113")
      (value "1K 1%")
      (footprint "eagle-import:0805")
      (fields (field (name "LCSC_PART") "C17513"))
      (libsource (lib "eagle-import") (part "1K-1%0805"))
    )
    (comp (ref "R114")
      (value "1K 1%")
      (footprint "eagle-import:0805")
      (fields (field (name "LCSC_PART") "C17513"))
      (libsource (lib "eagle-import") (part "1K-1%0805"))
    )
    (comp (ref "R115")
      (value "0.002R 1%")
      (footprint "eagle-import:2512")
      (fields (field (name "LCSC_PART") "C728320"))
      (libsource (lib "eagle-import") (part "0.002R-1%2512"))
    )
    (comp (ref "R116")
      (value "470K 1%")
      (footprint "eagle-import:0805")
      (fields (field (name "LCSC_PART") "C17709"))
      (libsource (lib "eagle-import") (part "470K-1%0805"))
    )
    (comp (ref "R117")
      (value "470K 1%")
      (footprint "eagle-import:0805")
      (fields (field (name "LCSC_PART") "C17709"))
      (libsource (lib "eagle-import") (part "470K-1%0805"))
    )
    (comp (ref "R118")
      (value "470K 1%")
      (footprint "eagle-import:0805")
      (fields (field (name "LCSC_PART") "C17709"))
      (libsource (lib "eagle-import") (part "470K-1%0805"))
    )
    (comp (ref "R119")
      (value "470K 1%")
      (footprint "eagle-import:0805")
      (fields (field (name "LCSC_PART") "C17709"))
      (libsource (lib "eagle-import") (part "470K-1%0805"))
    )
    (comp (ref "R120")
      (value "1K 1%")
      (footprint "eagle-import:0805")
      (fields (field (name "LCSC_PART") "C17513"))
      (libsource (lib "eagle-import") (part "1K-1%0805"))
    )
    (comp (ref "3VDC")
      (value "TP")
      (footprint "eagle-import:TP")
      (libsource (lib "eagle-import") (part "TP"))
    )
    (comp (ref "3VFB")
      (value "TP")
      (footprint "eagle-import:TP")
      (libsource (lib "eagle-import") (part "TP"))
    )
    (comp (ref "5V-NI1")
      (value "TP")
      (footprint "eagle-import:TP")
      (libsource (lib "eagle-import") (part "TP"))
    )
    (comp (ref "5V-NI2")
      (value "TP")
      (footprint "eagle-import:TP")
      (libsource (lib "eagle-import") (part "TP"))
    )
    (comp (ref "5VDC")
      (value "TP")
      (footprint "eagle-import:TP")
      (libsource (lib "eagle-import") (part "TP"))
    )
    (comp (ref "5VFB")
      (value "TP")
      (footprint "eagle-import:TP")
      (libsource (lib "eagle-import") (part "TP"))
    )
    (comp (ref "12VDC")
      (value "TP")
      (footprint "eagle-import:TP")
      (libsource (lib "eagle-import") (part "TP"))
    )
    (comp (ref "AC/DC1")
      (value "IRM_10_12")
      (footprint "eagle-import:IRM_10_12")
      (fields (field (name "LCSC_PART") "C20618065"))
      (libsource (lib "eagle-import") (part "IRM_10_12"))
    )
    (comp (ref "AC/DC2")
      (value "IRM-10-15")
      (footprint "eagle-import:IRM_15_12")
      (fields (field (name "LCSC_PART") "C5439799"))
      (libsource (lib "eagle-import") (part "IRM_10_12-2"))
    )
    (comp (ref "AC_L")
      (value "MOUNT-PAD-ROUND3.0")
      (footprint "eagle-import:3,0-PAD")
      (libsource (lib "eagle-import") (part "MOUNT-PAD-ROUND3.0"))
    )
    (comp (ref "AC_N")
      (value "MOUNT-PAD-ROUND3.0")
      (footprint "eagle-import:3,0-PAD")
      (libsource (lib "eagle-import") (part "MOUNT-PAD-ROUND3.0"))
    )
    (comp (ref "C1")
      (value "22uF 25V")
      (footprint "eagle-import:1206")
      (fields (field (name "LCSC_PART") "C12891"))
      (libsource (lib "eagle-import") (part "22UF-25V-1206"))
    )
    (comp (ref "C2")
      (value "22uF 25V")
      (footprint "eagle-import:1206")
      (fields (field (name "LCSC_PART") "C12891"))
      (libsource (lib "eagle-import") (part "22UF-25V-1206"))
    )
    (comp (ref "C3")
      (value "100nF 25V")
      (footprint "eagle-import:0402")
      (fields (field (name "LCSC_PART") "C56392"))
      (libsource (lib "eagle-import") (part "100NF-25V-0402"))
    )
    (comp (ref "C4")
      (value "100nF 25V")
      (footprint "eagle-import:0402")
      (fields (field (name "LCSC_PART") "C56392"))
      (libsource (lib "eagle-import") (part "100NF-25V-0402"))
    )
    (comp (ref "C5")
      (value "1nF 50V")
      (footprint "eagle-import:0603")
      (fields (field (name "LCSC_PART") "C1588"))
      (libsource (lib "eagle-import") (part "1NF-50V-0603"))
    )
    (comp (ref "C6")
      (value "100nF 25V")
      (footprint "eagle-import:0402")
      (fields (field (name "LCSC_PART") "C56392"))
      (libsource (lib "eagle-import") (part "100NF-25V-0402"))
    )
    (comp (ref "C7")
      (value "100nF 25V")
      (footprint "eagle-import:0402")
      (fields (field (name "LCSC_PART") "C56392"))
      (libsource (lib "eagle-import") (part "100NF-25V-0402"))
    )
    (comp (ref "C8")
      (value "100nF 25V")
      (footprint "eagle-import:0402")
      (fields (field (name "LCSC_PART") "C56392"))
      (libsource (lib "eagle-import") (part "100NF-25V-0402"))
    )
    (comp (ref "C9")
      (value "100nF 25V")
      (footprint "eagle-import:0402")
      (fields (field (name "LCSC_PART") "C56392"))
      (libsource (lib "eagle-import") (part "100NF-25V-0402"))
    )
    (comp (ref "C10")
      (value "100uF 25V")
      (footprint "eagle-import:6.3X7.7(DXL)")
      (fields (field (name "LCSC_PART") "C267469"))
      (libsource (lib "eagle-import") (part "100UF-25V6.3X7.7(DXL)"))
    )
    (comp (ref "C11")
      (value "33pF 50V")
      (footprint "eagle-import:0402")
      (fields (field (name "LCSC_PART") "C107005"))
      (libsource (lib "eagle-import") (part "33PF-50V0402"))
    )
    (comp (ref "C12")
      (value "33pF 50V")
      (footprint "eagle-import:0402")
      (fields (field (name "LCSC_PART") "C107005"))
      (libsource (lib "eagle-import") (part "33PF-50V0402"))
    )
    (comp (ref "C13")
      (value "100uF 25V")
      (footprint "eagle-import:6.3X7.7(DXL)")
      (fields (field (name "LCSC_PART") "C267469"))
      (libsource (lib "eagle-import") (part "100UF-25V6.3X7.7(DXL)"))
    )
    (comp (ref "C14")
      (value "22uF 25V")
      (footprint "eagle-import:1206")
      (fields (field (name "LCSC_PART") "C12891"))
      (libsource (lib "eagle-import") (part "22UF-25V-1206"))
    )
    (comp (ref "C15")
      (value "22uF 25V")
      (footprint "eagle-import:1206")
      (fields (field (name "LCSC_PART") "C12891"))
      (libsource (lib "eagle-import") (part "22UF-25V-1206"))
    )
    (comp (ref "C16")
      (value "100uF 25V")
      (footprint "eagle-import:6.3X7.7(DXL)")
      (fields (field (name "LCSC_PART") "C267469"))
      (libsource (lib "eagle-import") (part "100UF-25V6.3X7.7(DXL)"))
    )
    (comp (ref "C17")
      (value "22uF 25V")
      (footprint "eagle-import:1206")
      (fields (field (name "LCSC_PART") "C12891"))
      (libsource (lib "eagle-import") (part "22UF-25V-1206"))
    )
    (comp (ref "C18")
      (value "22uF 25V")
      (footprint "eagle-import:1206")
      (fields (field (name "LCSC_PART") "C12891"))
      (libsource (lib "eagle-import") (part "22UF-25V-1206"))
    )
    (comp (ref "C21")
      (value "2.2uF 50V")
      (footprint "eagle-import:0603")
      (fields (field (name "LCSC_PART") "C913904"))
      (libsource (lib "eagle-import") (part "2.2UF-50V0603"))
    )
    (comp (ref "C22")
      (value "220nF 50V")
      (footprint "eagle-import:0805")
      (fields (field (name "LCSC_PART") "C5378"))
      (libsource (lib "eagle-import") (part "220NF-50V0805"))
    )
    (comp (ref "C23")
      (value "100uF 50V")
      (footprint "eagle-import:6.3X7.7(DXL)")
      (fields (field (name "LCSC_PART") "C3151829"))
      (libsource (lib "eagle-import") (part "100UF-50V6.3X7.7(DXL)"))
    )
    (comp (ref "C35")
      (value "2.2uF 400V")
      (footprint "eagle-import:6.3X7.7(DXL)")
      (fields (field (name "LCSC_PART") "C3345109"))
      (libsource (lib "eagle-import") (part "2.2UF-400V6.3X7.7(DXL)"))
    )
    (comp (ref "C45")
      (value "1uF 50V")
      (footprint "eagle-import:0805")
      (fields (field (name "LCSC_PART") "C28323"))
      (libsource (lib "eagle-import") (part "1UF-50V0805"))
    )
    (comp (ref "C46")
      (value "2.2uF 50V")
      (footprint "eagle-import:0603")
      (fields (field (name "LCSC_PART") "C913904"))
      (libsource (lib "eagle-import") (part "2.2UF-50V0603"))
    )
    (comp (ref "C47")
      (value "2.2uF 400V")
      (footprint "eagle-import:6.3X7.7(DXL)")
      (fields (field (name "LCSC_PART") "C3345109"))
      (libsource (lib "eagle-import") (part "2.2UF-400V6.3X7.7(DXL)"))
    )
    (comp (ref "C51")
      (value "1nF 50V")
      (footprint "eagle-import:0603")
      (fields (field (name "LCSC_PART") "C1588"))
      (libsource (lib "eagle-import") (part "1NF-50V-0603"))
    )
    (comp (ref "C52")
      (value "220nF 50V")
      (footprint "eagle-import:0805")
      (fields (field (name "LCSC_PART") "C5378"))
      (libsource (lib "eagle-import") (part "220NF-50V0805"))
    )
    (comp (ref "C53")
      (value "100uF 50V")
      (footprint "eagle-import:6.3X7.7(DXL)")
      (fields (field (name "LCSC_PART") "C3151829"))
      (libsource (lib "eagle-import") (part "100UF-50V6.3X7.7(DXL)"))
    )
    (comp (ref "C57")
      (value "1uF 50V")
      (footprint "eagle-import:0805")
      (fields (field (name "LCSC_PART") "C28323"))
      (libsource (lib "eagle-import") (part "1UF-50V0805"))
    )
    (comp (ref "D9")
      (value "1N4007")
      (footprint "eagle-import:SMA_DO-214AC")
      (fields (field (name "LCSC_PART") "C727081"))
      (libsource (lib "eagle-import") (part "1N4007"))
    )
    (comp (ref "D10")
      (value "1N4007")
      (footprint "eagle-import:SMA_DO-214AC")
      (fields (field (name "LCSC_PART") "C727081"))
      (libsource (lib "eagle-import") (part "1N4007"))
    )
    (comp (ref "D11")
      (value "US1J-E3/61T")
      (footprint "eagle-import:SMA_DO-214AC")
      (fields (field (name "LCSC_PART") "C44763"))
      (libsource (lib "eagle-import") (part "US1J-E3/61T"))
    )
    (comp (ref "D12")
      (value "1N4007")
      (footprint "eagle-import:SMA_DO-214AC")
      (fields (field (name "LCSC_PART") "C727081"))
      (libsource (lib "eagle-import") (part "1N4007"))
    )
    (comp (ref "D13")
      (value "1N4007")
      (footprint "eagle-import:SMA_DO-214AC")
      (fields (field (name "LCSC_PART") "C727081"))
      (libsource (lib "eagle-import") (part "1N4007"))
    )
    (comp (ref "D14")
      (value "US1J-E3/61T")
      (footprint "eagle-import:SMA_DO-214AC")
      (fields (field (name "LCSC_PART") "C44763"))
      (libsource (lib "eagle-import") (part "US1J-E3/61T"))
    )
    (comp (ref "D16")
      (value "SMAJ15A")
      (footprint "eagle-import:SMA_DO-214AC")
      (fields (field (name "LCSC_PART") "C23424"))
      (libsource (lib "eagle-import") (part "SMAJ15A"))
    )
    (comp (ref "FB-NI1")
      (value "TP")
      (footprint "eagle-import:TP")
      (libsource (lib "eagle-import") (part "TP"))
    )
    (comp (ref "FB-NI2")
      (value "TP")
      (footprint "eagle-import:TP")
      (libsource (lib "eagle-import") (part "TP"))
    )
    (comp (ref "GND") (value "TP") (footprint "eagle-import:TP") (libsource (lib "eagle-import") (part "TP")))
    (comp (ref "GND-3")
      (value "TP")
      (footprint "eagle-import:TP")
      (libsource (lib "eagle-import") (part "TP"))
    )
    (comp (ref "GND-5")
      (value "TP")
      (footprint "eagle-import:TP")
      (libsource (lib "eagle-import") (part "TP"))
    )
    (comp (ref "IC1")
      (value "MP2315GJ-Z")
      (footprint "eagle-import:SOT65P280X110-8N")
      (fields (field (name "LCSC_PART") "C45889"))
      (libsource (lib "eagle-import") (part "MP2315TSOT23-8"))
    )
    (comp (ref "IC2")
      (value "MP2315GJ-Z")
      (footprint "eagle-import:SOT65P280X110-8N")
      (fields (field (name "LCSC_PART") "C45889"))
      (libsource (lib "eagle-import") (part "MP2315TSOT23-8"))
    )
    (comp (ref "IC5")
      (value "MP150GJ")
      (footprint "eagle-import:SOT23-5")
      (libsource (lib "eagle-import") (part "MP150GJ"))
    )
    (comp (ref "IC13")
      (value "MP150GJ")
      (footprint "eagle-import:SOT23-5")
      (libsource (lib "eagle-import") (part "MP150GJ"))
    )
    (comp (ref "J2") (value "JP") (footprint "eagle-import:SJ") (libsource (lib "eagle-import") (part "SJ")))
    (comp (ref "J7") (value "JP") (footprint "eagle-import:SJ") (libsource (lib "eagle-import") (part "SJ")))
    (comp (ref "J8")
      (value "0R 1%")
      (footprint "eagle-import:0805")
      (fields (field (name "LCSC_PART") "C17477"))
      (libsource (lib "eagle-import") (part "0R0805"))
    )
    (comp (ref "J9")
      (value "0R 1%")
      (footprint "eagle-import:0805")
      (fields (field (name "LCSC_PART") "C17477"))
      (libsource (lib "eagle-import") (part "0R0805"))
    )
    (comp (ref "J10")
      (value "0R 1%")
      (footprint "eagle-import:0805")
      (fields (field (name "LCSC_PART") "C17477"))
      (libsource (lib "eagle-import") (part "0R0805"))
    )
    (comp (ref "L-REC1")
      (value "TP")
      (footprint "eagle-import:TP")
      (libsource (lib "eagle-import") (part "TP"))
    )
    (comp (ref "L-REC2")
      (value "TP")
      (footprint "eagle-import:TP")
      (libsource (lib "eagle-import") (part "TP"))
    )
    (comp (ref "L1")
      (value "4.9uH")
      (footprint "eagle-import:SRR5228A")
      (libsource (lib "eagle-import") (part "L"))
    )
    (comp (ref "L2")
      (value "4.2uH")
      (footprint "eagle-import:SRR5228A")
      (libsource (lib "eagle-import") (part "L"))
    )
    (comp (ref "L3")
      (value "1mH")
      (footprint "eagle-import:L-6.6X6.6")
      (fields (field (name "LCSC_PART") "C168049"))
      (libsource (lib "eagle-import") (part "1MHL-6.6X6.6"))
    )
    (comp (ref "L5")
      (value "1mH")
      (footprint "eagle-import:L-6.6X6.6")
      (fields (field (name "LCSC_PART") "C168049"))
      (libsource (lib "eagle-import") (part "1MHL-6.6X6.6"))
    )
    (comp (ref "P3ON")
      (value "Green")
      (footprint "eagle-import:LED-0603")
      (fields (field (name "LCSC_PART") "C965804"))
      (libsource (lib "eagle-import") (part "LED-GREENLED-0603"))
    )
    (comp (ref "P5ON")
      (value "Green")
      (footprint "eagle-import:LED-0603")
      (fields (field (name "LCSC_PART") "C965804"))
      (libsource (lib "eagle-import") (part "LED-GREENLED-0603"))
    )
    (comp (ref "P12ON")
      (value "Green")
      (footprint "eagle-import:LED-0603")
      (fields (field (name "LCSC_PART") "C965804"))
      (libsource (lib "eagle-import") (part "LED-GREENLED-0603"))
    )
    (comp (ref "R1")
      (value "DNI")
      (footprint "eagle-import:0402")
      (libsource (lib "eagle-import") (part "R0402"))
    )
    (comp (ref "R2")
      (value "10K 1%")
      (footprint "eagle-import:0402")
      (fields (field (name "LCSC_PART") "C25744"))
      (libsource (lib "eagle-import") (part "10K-1%0402"))
    )
    (comp (ref "R3")
      (value "100K 1%")
      (footprint "eagle-import:0402")
      (fields (field (name "LCSC_PART") "C25741"))
      (libsource (lib "eagle-import") (part "100K-1%0402"))
    )
    (comp (ref "R4")
      (value "9.09K 1%")
      (footprint "eagle-import:0402")
      (fields (field (name "LCSC_PART") "C11549"))
      (libsource (lib "eagle-import") (part "9.09K-1%0402"))
    )
    (comp (ref "R5")
      (value "100K 1%")
      (footprint "eagle-import:0402")
      (fields (field (name "LCSC_PART") "C25741"))
      (libsource (lib "eagle-import") (part "100K-1%0402"))
    )
    (comp (ref "R6")
      (value "7.5K 1%")
      (footprint "eagle-import:0402")
      (fields (field (name "LCSC_PART") "C25918"))
      (libsource (lib "eagle-import") (part "7.5K-1%0402"))
    )
    (comp (ref "R7")
      (value "10R 1%")
      (footprint "eagle-import:0402")
      (fields (field (name "LCSC_PART") "C25077"))
      (libsource (lib "eagle-import") (part "10R-1%0402"))
    )
    (comp (ref "R8")
      (value "20K 1%")
      (footprint "eagle-import:0402")
      (fields (field (name "LCSC_PART") "C25765"))
      (libsource (lib "eagle-import") (part "20K-1%0402"))
    )
    (comp (ref "R9")
      (value "10R 1%")
      (footprint "eagle-import:0402")
      (fields (field (name "LCSC_PART") "C25077"))
      (libsource (lib "eagle-import") (part "10R-1%0402"))
    )
    (comp (ref "R10")
      (value "33K")
      (footprint "eagle-import:0402")
      (libsource (lib "eagle-import") (part "R0402"))
    )
    (comp (ref "R11")
      (value "40.2K 1%")
      (footprint "eagle-import:0402")
      (fields (field (name "LCSC_PART") "C25893"))
      (libsource (lib "eagle-import") (part "40.2K-1%0402"))
    )
    (comp (ref "R12")
      (value "7.5K 1%")
      (footprint "eagle-import:0402")
      (fields (field (name "LCSC_PART") "C25918"))
      (libsource (lib "eagle-import") (part "7.5K-1%0402"))
    )
    (comp (ref "R13")
      (value "40.2K 1%")
      (footprint "eagle-import:0402")
      (fields (field (name "LCSC_PART") "C25893"))
      (libsource (lib "eagle-import") (part "40.2K-1%0402"))
    )
    (comp (ref "R14")
      (value "12.7K 1%")
      (footprint "eagle-import:0402")
      (fields (field (name "LCSC_PART") "C25853"))
      (libsource (lib "eagle-import") (part "12.7K-1%0402"))
    )
    (comp (ref "R60")
      (value "4.99K 1%")
      (footprint "eagle-import:0603")
      (fields (field (name "LCSC_PART") "C23046"))
      (libsource (lib "eagle-import") (part "4.99K-1%0603"))
    )
    (comp (ref "R61")
      (value "4.99K 1%")
      (footprint "eagle-import:0603")
      (fields (field (name "LCSC_PART") "C23046"))
      (libsource (lib "eagle-import") (part "4.99K-1%0603"))
    )
    (comp (ref "R62")
      (value "39R 1% 2W")
      (footprint "eagle-import:2512")
      (fields (field (name "LCSC_PART") "C175263"))
      (libsource (lib "eagle-import") (part "39R-1%2512"))
    )
    (comp (ref "R94")
      (value "100K 1%")
      (footprint "eagle-import:0402")
      (fields (field (name "LCSC_PART") "C25741"))
      (libsource (lib "eagle-import") (part "100K-1%0402"))
    )
    (comp (ref "R95")
      (value "10K 1%")
      (footprint "eagle-import:0402")
      (fields (field (name "LCSC_PART") "C25744"))
      (libsource (lib "eagle-import") (part "10K-1%0402"))
    )
    (comp (ref "R96")
      (value "10K 1%")
      (footprint "eagle-import:0805")
      (fields (field (name "LCSC_PART") "C17414"))
      (libsource (lib "eagle-import") (part "10K-1%0805"))
    )
    (comp (ref "R105")
      (value "4.99K 1%")
      (footprint "eagle-import:0603")
      (fields (field (name "LCSC_PART") "C23046"))
      (libsource (lib "eagle-import") (part "4.99K-1%0603"))
    )
    (comp (ref "R106")
      (value "39R 1% 2W")
      (footprint "eagle-import:2512")
      (fields (field (name "LCSC_PART") "C175263"))
      (libsource (lib "eagle-import") (part "39R-1%2512"))
    )
    (comp (ref "R107")
      (value "4.99K 1%")
      (footprint "eagle-import:0603")
      (fields (field (name "LCSC_PART") "C23046"))
      (libsource (lib "eagle-import") (part "4.99K-1%0603"))
    )
    (comp (ref "R108")
      (value "10K 1%")
      (footprint "eagle-import:0805")
      (fields (field (name "LCSC_PART") "C17414"))
      (libsource (lib "eagle-import") (part "10K-1%0805"))
    )
    (comp (ref "R123")
      (value "1K 1%")
      (footprint "eagle-import:0402")
      (fields (field (name "LCSC_PART") "C11702"))
      (libsource (lib "eagle-import") (part "1K-1%0402"))
    )
    (comp (ref "R148")
      (value "2.4K 1%")
      (footprint "eagle-import:0402")
      (fields (field (name "LCSC_PART") "C25882"))
      (libsource (lib "eagle-import") (part "2.4K-1%0402"))
    )
    (comp (ref "R150")
      (value "8.2K 1%")
      (footprint "eagle-import:0402")
      (fields (field (name "LCSC_PART") "C25924"))
      (libsource (lib "eagle-import") (part "8.2K-1%0402"))
    )
    (comp (ref "R161")
      (value "DNI")
      (footprint "eagle-import:0402")
      (libsource (lib "eagle-import") (part "R0402"))
    )
    (comp (ref "R162")
      (value "10K 1%")
      (footprint "eagle-import:0402")
      (fields (field (name "LCSC_PART") "C25744"))
      (libsource (lib "eagle-import") (part "10K-1%0402"))
    )
    (comp (ref "SW") (value "TP") (footprint "eagle-import:TP") (libsource (lib "eagle-import") (part "TP")))
    (comp (ref "SW3") (value "TP") (footprint "eagle-import:TP") (libsource (lib "eagle-import") (part "TP")))
    (comp (ref "VNI1")
      (value "TP")
      (footprint "eagle-import:TP")
      (libsource (lib "eagle-import") (part "TP"))
    )
    (comp (ref "VNI2")
      (value "TP")
      (footprint "eagle-import:TP")
      (libsource (lib "eagle-import") (part "TP"))
    )
  )
  (nets
    (net (code "1") (name "+1V1") (class "Default")
      (node (ref "C75") (pin "1") (pinfunction "1_1") (pintype "passive"))
      (node (ref "C76") (pin "1") (pinfunction "1_1") (pintype "passive"))
      (node (ref "C77") (pin "1") (pinfunction "1_1") (pintype "passive"))
      (node (ref "DVDD") (pin "TP") (pinfunction "P$1_TP") (pintype "bidirectional"))
      (node (ref "IC15") (pin "23") (pinfunction "DVDD_23") (pintype "bidirectional"))
      (node (ref "IC15") (pin "45") (pinfunction "VREG_VOUT_45") (pintype "bidirectional"))
      (node (ref "IC15") (pin "50") (pinfunction "DVDD_50") (pintype "bidirectional"))
    )
    (net (code "2") (name "+3V3") (class "Default")
      (node (ref "3VDC") (pin "TP") (pinfunction "P$1_TP") (pintype "bidirectional"))
      (node (ref "C103") (pin "1") (pinfunction "1_1") (pintype "passive"))
      (node (ref "C12") (pin "1") (pinfunction "1_1") (pintype "passive"))
      (node (ref "C15") (pin "1") (pinfunction "1_1") (pintype "passive"))
      (node (ref "C18") (pin "1") (pinfunction "1_1") (pintype "passive"))
      (node (ref "C19") (pin "1") (pinfunction "1_1") (pintype "passive"))
      (node (ref "C20") (pin "1") (pinfunction "1_1") (pintype "passive"))
      (node (ref "C33") (pin "1") (pinfunction "1_1") (pintype "passive"))
      (node (ref "C34") (pin "1") (pinfunction "1_1") (pintype "passive"))
      (node (ref "C88") (pin "1") (pinfunction "1_1") (pintype "passive"))
      (node (ref "C89") (pin "1") (pinfunction "1_1") (pintype "passive"))
      (node (ref "C90") (pin "1") (pinfunction "1_1") (pintype "passive"))
      (node (ref "DSP") (pin "1") (pinfunction "1_1") (pintype "bidirectional"))
      (node (ref "DSP") (pin "2") (pinfunction "2_2") (pintype "bidirectional"))
      (node (ref "ETH1") (pin "10") (pinfunction "GREEN+_10") (pintype "passive"))
      (node (ref "ETH1") (pin "12") (pinfunction "YELLOW+_12") (pintype "passive"))
      (node (ref "IC20") (pin "28") (pinfunction "VDD_28") (pintype "power_in"))
      (node (ref "IC20") (pin "43") (pinfunction "PMODE2_43") (pintype "input"))
      (node (ref "IC20") (pin "44") (pinfunction "PMODE1_44") (pintype "input"))
      (node (ref "IC20") (pin "45") (pinfunction "PMODE0_45") (pintype "input"))
      (node (ref "IC22") (pin "2") (pinfunction "V+_2") (pintype "power_in"))
      (node (ref "IC4") (pin "5") (pinfunction "VDD_5") (pintype "bidirectional"))
      (node (ref "IC9") (pin "16") (pinfunction "VCC_16") (pintype "power_in"))
      (node (ref "L2") (pin "2") (pinfunction "2_2") (pintype "passive"))
      (node (ref "L4") (pin "1") (pinfunction "1_1") (pintype "passive"))
      (node (ref "R123") (pin "1") (pinfunction "1_1") (pintype "passive"))
      (node (ref "R13") (pin "1") (pinfunction "1_1") (pintype "passive"))
      (node (ref "R145") (pin "2") (pinfunction "2_2") (pintype "passive"))
      (node (ref "R147") (pin "2") (pinfunction "2_2") (pintype "passive"))
      (node (ref "R149") (pin "A1") (pinfunction "1_A1") (pintype "passive"))
      (node (ref "R149") (pin "B1") (pinfunction "2_B1") (pintype "passive"))
      (node (ref "R149") (pin "C1") (pinfunction "3_C1") (pintype "passive"))
      (node (ref "R149") (pin "D1") (pinfunction "4_D1") (pintype "passive"))
      (node (ref "R89") (pin "A2") (pinfunction "8_A2") (pintype "passive"))
      (node (ref "R89") (pin "B2") (pinfunction "7_B2") (pintype "passive"))
      (node (ref "R89") (pin "C2") (pinfunction "6_C2") (pintype "passive"))
      (node (ref "R89") (pin "D2") (pinfunction "5_D2") (pintype "passive"))
      (node (ref "R90") (pin "A2") (pinfunction "8_A2") (pintype "passive"))
      (node (ref "R90") (pin "B2") (pinfunction "7_B2") (pintype "passive"))
      (node (ref "R90") (pin "C2") (pinfunction "6_C2") (pintype "passive"))
      (node (ref "R90") (pin "D2") (pinfunction "5_D2") (pintype "passive"))
    )
    (net (code "3") (name "+3V3_A") (class "Default")
      (node (ref "C91") (pin "1") (pinfunction "1_1") (pintype "passive"))
      (node (ref "C92") (pin "1") (pinfunction "1_1") (pintype "passive"))
      (node (ref "C93") (pin "1") (pinfunction "1_1") (pintype "passive"))
      (node (ref "C94") (pin "1") (pinfunction "1_1") (pintype "passive"))
      (node (ref "C95") (pin "1") (pinfunction "1_1") (pintype "passive"))
      (node (ref "C96") (pin "1") (pinfunction "1_1") (pintype "passive"))
      (node (ref "IC20") (pin "11") (pinfunction "AVDD_11") (pintype "power_in"))
      (node (ref "IC20") (pin "15") (pinfunction "AVDD_15") (pintype "power_in"))
      (node (ref "IC20") (pin "17") (pinfunction "AVDD_17") (pintype "power_in"))
      (node (ref "IC20") (pin "21") (pinfunction "AVDD_21") (pintype "power_in"))
      (node (ref "IC20") (pin "4") (pinfunction "AVDD_4") (pintype "power_in"))
      (node (ref "IC20") (pin "8") (pinfunction "AVDD_8") (pintype "power_in"))
      (node (ref "L4") (pin "2") (pinfunction "2_2") (pintype "passive"))
      (node (ref "R139") (pin "2") (pinfunction "2_2") (pintype "passive"))
      (node (ref "R140") (pin "2") (pinfunction "2_2") (pintype "passive"))
      (node (ref "R146") (pin "2") (pinfunction "2_2") (pintype "passive"))
    )
    (net (code "4") (name "+3V3_MCU") (class "Default")
      (node (ref "C100") (pin "1") (pinfunction "1_1") (pintype "passive"))
      (node (ref "C101") (pin "1") (pinfunction "1_1") (pintype "passive"))
      (node (ref "C104") (pin "1") (pinfunction "1_1") (pintype "passive"))
      (node (ref "C64") (pin "1") (pinfunction "1_1") (pintype "passive"))
      (node (ref "C67") (pin "1") (pinfunction "1_1") (pintype "passive"))
      (node (ref "C68") (pin "1") (pinfunction "1_1") (pintype "passive"))
      (node (ref "C69") (pin "1") (pinfunction "1_1") (pintype "passive"))
      (node (ref "C70") (pin "1") (pinfunction "1_1") (pintype "passive"))
      (node (ref "C71") (pin "1") (pinfunction "1_1") (pintype "passive"))
      (node (ref "C72") (pin "1") (pinfunction "1_1") (pintype "passive"))
      (node (ref "C73") (pin "1") (pinfunction "1_1") (pintype "passive"))
      (node (ref "C99") (pin "1") (pinfunction "1_1") (pintype "passive"))
      (node (ref "IC15") (pin "1") (pinfunction "IOVDD_1") (pintype "bidirectional"))
      (node (ref "IC15") (pin "10") (pinfunction "IOVDD_10") (pintype "bidirectional"))
      (node (ref "IC15") (pin "22") (pinfunction "IOVDD_22") (pintype "bidirectional"))
      (node (ref "IC15") (pin "33") (pinfunction "IOVDD_33") (pintype "bidirectional"))
      (node (ref "IC15") (pin "42") (pinfunction "IOVDD_42") (pintype "bidirectional"))
      (node (ref "IC15") (pin "44") (pinfunction "VREG_VIN_44") (pintype "bidirectional"))
      (node (ref "IC15") (pin "48") (pinfunction "USB_VDD_48") (pintype "bidirectional"))
      (node (ref "IC15") (pin "49") (pinfunction "IOVDD_49") (pintype "bidirectional"))
      (node (ref "IC18") (pin "8") (pinfunction "VCC_8") (pintype "power_in"))
      (node (ref "IC19") (pin "8") (pinfunction "VCC_8") (pintype "power_in"))
      (node (ref "IC21") (pin "5") (pinfunction "VOUT_5") (pintype "bidirectional"))
      (node (ref "IOVDD") (pin "TP") (pinfunction "P$1_TP") (pintype "bidirectional"))
      (node (ref "PWR") (pin "A") (pinfunction "A_A") (pintype "passive"))
      (node (ref "R109") (pin "2") (pinfunction "2_2") (pintype "passive"))
      (node (ref "R111") (pin "2") (pinfunction "2_2") (pintype "passive"))
      (node (ref "R128") (pin "2") (pinfunction "2_2") (pintype "passive"))
      (node (ref "R130") (pin "A2") (pinfunction "8_A2") (pintype "passive"))
      (node (ref "R130") (pin "B2") (pinfunction "7_B2") (pintype "passive"))
      (node (ref "R130") (pin "C2") (pinfunction "6_C2") (pintype "passive"))
      (node (ref "R130") (pin "D2") (pinfunction "5_D2") (pintype "passive"))
      (node (ref "R132") (pin "1") (pinfunction "1_1") (pintype "passive"))
      (node (ref "R152") (pin "1") (pinfunction "1_1") (pintype "passive"))
      (node (ref "R165") (pin "2") (pinfunction "2_2") (pintype "passive"))
    )
    (net (code "5") (name "+5V") (class "Default")
      (node (ref "5VDC") (pin "TP") (pinfunction "P$1_TP") (pintype "bidirectional"))
      (node (ref "C11") (pin "1") (pinfunction "1_1") (pintype "passive"))
      (node (ref "C14") (pin "1") (pinfunction "1_1") (pintype "passive"))
      (node (ref "C17") (pin "1") (pinfunction "1_1") (pintype "passive"))
      (node (ref "D15") (pin "A") (pinfunction "A_A") (pintype "passive"))
      (node (ref "DSP") (pin "3") (pinfunction "3_3") (pintype "bidirectional"))
      (node (ref "DSP") (pin "4") (pinfunction "4_4") (pintype "bidirectional"))
      (node (ref "L1") (pin "2") (pinfunction "2_2") (pintype "passive"))
      (node (ref "R11") (pin "1") (pinfunction "1_1") (pintype "passive"))
      (node (ref "R148") (pin "1") (pinfunction "1_1") (pintype "passive"))
    )
    (net (code "6") (name "+5V_MEA") (class "Default")
      (node (ref "IC10") (pin "1") (pinfunction "VDD_1") (pintype "power_in"))
      (node (ref "IC11") (pin "1") (pinfunction "VDD_1") (pintype "power_in"))
      (node (ref "IC12") (pin "1") (pinfunction "VDD_1") (pintype "power_in"))
      (node (ref "IC14") (pin "1") (pinfunction "VDD_1") (pintype "power_in"))
      (node (ref "IC16") (pin "1") (pinfunction "VDD_1") (pintype "power_in"))
      (node (ref "IC6") (pin "1") (pinfunction "VDD_1") (pintype "power_in"))
      (node (ref "IC7") (pin "1") (pinfunction "VDD_1") (pintype "power_in"))
      (node (ref "IC8") (pin "1") (pinfunction "VDD_1") (pintype "power_in"))
      (node (ref "J2") (pin "2") (pinfunction "2_2") (pintype "passive"))
      (node (ref "J7") (pin "2") (pinfunction "2_2") (pintype "passive"))
      (node (ref "R63") (pin "A1") (pinfunction "1_A1") (pintype "passive"))
      (node (ref "R63") (pin "B1") (pinfunction "2_B1") (pintype "passive"))
      (node (ref "R63") (pin "C1") (pinfunction "3_C1") (pintype "passive"))
      (node (ref "R63") (pin "D1") (pinfunction "4_D1") (pintype "passive"))
      (node (ref "R64") (pin "A1") (pinfunction "1_A1") (pintype "passive"))
      (node (ref "R64") (pin "B1") (pinfunction "2_B1") (pintype "passive"))
      (node (ref "R64") (pin "C1") (pinfunction "3_C1") (pintype "passive"))
      (node (ref "R64") (pin "D1") (pinfunction "4_D1") (pintype "passive"))
    )
    (net (code "7") (name "+5V_MEA1") (class "Default")
      (node (ref "5V-NI1") (pin "TP") (pinfunction "P$1_TP") (pintype "bidirectional"))
      (node (ref "C23") (pin "1") (pinfunction "+_1") (pintype "passive"))
      (node (ref "C45") (pin "2") (pinfunction "2_2") (pintype "passive"))
      (node (ref "D9") (pin "A") (pinfunction "A_A") (pintype "passive"))
      (node (ref "J2") (pin "1") (pinfunction "1_1") (pintype "passive"))
      (node (ref "L3") (pin "2") (pinfunction "2_2") (pintype "passive"))
      (node (ref "R96") (pin "1") (pinfunction "1_1") (pintype "passive"))
    )
    (net (code "8") (name "+5V_MEA2") (class "Default")
      (node (ref "5V-NI2") (pin "TP") (pinfunction "P$1_TP") (pintype "bidirectional"))
      (node (ref "C53") (pin "1") (pinfunction "+_1") (pintype "passive"))
      (node (ref "C57") (pin "2") (pinfunction "2_2") (pintype "passive"))
      (node (ref "D13") (pin "A") (pinfunction "A_A") (pintype "passive"))
      (node (ref "J7") (pin "1") (pinfunction "1_1") (pintype "passive"))
      (node (ref "L5") (pin "2") (pinfunction "2_2") (pintype "passive"))
      (node (ref "R108") (pin "1") (pinfunction "1_1") (pintype "passive"))
    )
    (net (code "9") (name "+12V") (class "Default")
      (node (ref "C1") (pin "1") (pinfunction "1_1") (pintype "passive"))
      (node (ref "C2") (pin "1") (pinfunction "1_1") (pintype "passive"))
      (node (ref "C3") (pin "1") (pinfunction "1_1") (pintype "passive"))
      (node (ref "C4") (pin "1") (pinfunction "1_1") (pintype "passive"))
      (node (ref "D1") (pin "C") (pinfunction "C_C") (pintype "passive"))
      (node (ref "D2") (pin "C") (pinfunction "C_C") (pintype "passive"))
      (node (ref "D3") (pin "C") (pinfunction "C_C") (pintype "passive"))
      (node (ref "D4") (pin "C") (pinfunction "C_C") (pintype "passive"))
      (node (ref "D5") (pin "C") (pinfunction "C_C") (pintype "passive"))
      (node (ref "D6") (pin "C") (pinfunction "C_C") (pintype "passive"))
      (node (ref "D7") (pin "C") (pinfunction "C_C") (pintype "passive"))
      (node (ref "D8") (pin "C") (pinfunction "C_C") (pintype "passive"))
      (node (ref "FAN") (pin "2") (pinfunction "2_2") (pintype "passive"))
      (node (ref "IC1") (pin "2") (pinfunction "IN_2") (pintype "bidirectional"))
      (node (ref "IC2") (pin "2") (pinfunction "IN_2") (pintype "bidirectional"))
      (node (ref "IC3") (pin "10") (pinfunction "COM_10") (pintype "bidirectional"))
      (node (ref "J10") (pin "1") (pinfunction "1_1") (pintype "passive"))
      (node (ref "J8") (pin "1") (pinfunction "1_1") (pintype "passive"))
      (node (ref "J9") (pin "1") (pinfunction "1_1") (pintype "passive"))
      (node (ref "K1") (pin "8") (pinfunction "8_8") (pintype "passive"))
      (node (ref "K2") (pin "8") (pinfunction "8_8") (pintype "passive"))
      (node (ref "K3") (pin "8") (pinfunction "8_8") (pintype "passive"))
      (node (ref "K4") (pin "8") (pinfunction "8_8") (pintype "passive"))
      (node (ref "K5") (pin "8") (pinfunction "8_8") (pintype "passive"))
      (node (ref "K6") (pin "8") (pinfunction "8_8") (pintype "passive"))
      (node (ref "K7") (pin "8") (pinfunction "8_8") (pintype "passive"))
      (node (ref "K8") (pin "8") (pinfunction "8_8") (pintype "passive"))
      (node (ref "R150") (pin "1") (pinfunction "1_1") (pintype "passive"))
      (node (ref "R162") (pin "2") (pinfunction "2_2") (pintype "passive"))
      (node (ref "R94") (pin "2") (pinfunction "2_2") (pintype "passive"))
    )
    (net (code "10") (name "+12V_MEA") (class "Default")
      (node (ref "IC15") (pin "41") (pinfunction "GPIO29/ADC3_41") (pintype "bidirectional"))
      (node (ref "R94") (pin "1") (pinfunction "1_1") (pintype "passive"))
      (node (ref "R95") (pin "2") (pinfunction "2_2") (pintype "passive"))
    )
    (net (code "11") (name "5V_EN") (class "Default")
      (node (ref "IC1") (pin "6") (pinfunction "EN_6") (pintype "bidirectional"))
      (node (ref "R1") (pin "1") (pinfunction "1_1") (pintype "passive"))
      (node (ref "R161") (pin "2") (pinfunction "2_2") (pintype "passive"))
      (node (ref "R162") (pin "1") (pinfunction "1_1") (pintype "passive"))
    )
    (net (code "12") (name "AC_L") (class "Default")
      (node (ref "AC/DC1") (pin "AC_L") (pinfunction "AC/L_AC_L") (pintype "input"))
      (node (ref "AC/DC2") (pin "AC/L") (pinfunction "AC/L_AC/L") (pintype "input"))
      (node (ref "AC_L") (pin "B3,0") (pinfunction "MOUNT_B3,0") (pintype "passive"))
      (node (ref "K1") (pin "3") (pinfunction "3_3") (pintype "passive"))
      (node (ref "K1") (pin "6") (pinfunction "6_6") (pintype "passive"))
      (node (ref "K2") (pin "3") (pinfunction "3_3") (pintype "passive"))
      (node (ref "K2") (pin "6") (pinfunction "6_6") (pintype "passive"))
      (node (ref "K3") (pin "3") (pinfunction "3_3") (pintype "passive"))
      (node (ref "K3") (pin "6") (pinfunction "6_6") (pintype "passive"))
      (node (ref "K4") (pin "3") (pinfunction "3_3") (pintype "passive"))
      (node (ref "K4") (pin "6") (pinfunction "6_6") (pintype "passive"))
      (node (ref "K5") (pin "3") (pinfunction "3_3") (pintype "passive"))
      (node (ref "K5") (pin "6") (pinfunction "6_6") (pintype "passive"))
      (node (ref "K6") (pin "3") (pinfunction "3_3") (pintype "passive"))
      (node (ref "K6") (pin "6") (pinfunction "6_6") (pintype "passive"))
      (node (ref "K7") (pin "3") (pinfunction "3_3") (pintype "passive"))
      (node (ref "K7") (pin "6") (pinfunction "6_6") (pintype "passive"))
      (node (ref "K8") (pin "3") (pinfunction "3_3") (pintype "passive"))
      (node (ref "K8") (pin "6") (pinfunction "6_6") (pintype "passive"))
      (node (ref "R106") (pin "1") (pinfunction "1_1") (pintype "passive"))
      (node (ref "R62") (pin "1") (pinfunction "1_1") (pintype "passive"))
    )
    (net (code "13") (name "ADC_V_USB") (class "Default")
      (node (ref "IC15") (pin "38") (pinfunction "GPIO26/ADC0_38") (pintype "bidirectional"))
      (node (ref "R126") (pin "2") (pinfunction "2_2") (pintype "passive"))
      (node (ref "R127") (pin "1") (pinfunction "1_1") (pintype "passive"))
    )
    (net (code "14") (name "AGND") (class "Default")
      (node (ref "AC/DC1") (pin "AC_N") (pinfunction "AC/N_AC_N") (pintype "input"))
      (node (ref "AC/DC2") (pin "AC/N") (pinfunction "AC/N_AC/N") (pintype "input"))
      (node (ref "AC_N") (pin "B3,0") (pinfunction "MOUNT_B3,0") (pintype "passive"))
      (node (ref "C106") (pin "2") (pinfunction "2_2") (pintype "passive"))
      (node (ref "C107") (pin "2") (pinfunction "2_2") (pintype "passive"))
      (node (ref "C108") (pin "2") (pinfunction "2_2") (pintype "passive"))
      (node (ref "C109") (pin "2") (pinfunction "2_2") (pintype "passive"))
      (node (ref "C110") (pin "2") (pinfunction "2_2") (pintype "passive"))
      (node (ref "C111") (pin "2") (pinfunction "2_2") (pintype "passive"))
      (node (ref "C112") (pin "2") (pinfunction "2_2") (pintype "passive"))
      (node (ref "C113") (pin "2") (pinfunction "2_2") (pintype "passive"))
      (node (ref "C23") (pin "2") (pinfunction "-_2") (pintype "passive"))
      (node (ref "C24") (pin "2") (pinfunction "2_2") (pintype "passive"))
      (node (ref "C25") (pin "2") (pinfunction "2_2") (pintype "passive"))
      (node (ref "C26") (pin "2") (pinfunction "2_2") (pintype "passive"))
      (node (ref "C27") (pin "2") (pinfunction "2_2") (pintype "passive"))
      (node (ref "C28") (pin "2") (pinfunction "2_2") (pintype "passive"))
      (node (ref "C29") (pin "2") (pinfunction "2_2") (pintype "passive"))
      (node (ref "C30") (pin "2") (pinfunction "2_2") (pintype "passive"))
      (node (ref "C31") (pin "2") (pinfunction "2_2") (pintype "passive"))
      (node (ref "C32") (pin "2") (pinfunction "2_2") (pintype "passive"))
      (node (ref "C35") (pin "2") (pinfunction "-_2") (pintype "passive"))
      (node (ref "C36") (pin "2") (pinfunction "2_2") (pintype "passive"))
      (node (ref "C37") (pin "2") (pinfunction "2_2") (pintype "passive"))
      (node (ref "C38") (pin "2") (pinfunction "2_2") (pintype "passive"))
      (node (ref "C39") (pin "2") (pinfunction "2_2") (pintype "passive"))
      (node (ref "C40") (pin "2") (pinfunction "2_2") (pintype "passive"))
      (node (ref "C41") (pin "2") (pinfunction "2_2") (pintype "passive"))
      (node (ref "C42") (pin "2") (pinfunction "2_2") (pintype "passive"))
      (node (ref "C43") (pin "2") (pinfunction "2_2") (pintype "passive"))
      (node (ref "C44") (pin "2") (pinfunction "2_2") (pintype "passive"))
      (node (ref "C45") (pin "1") (pinfunction "1_1") (pintype "passive"))
      (node (ref "C47") (pin "2") (pinfunction "-_2") (pintype "passive"))
      (node (ref "C48") (pin "2") (pinfunction "2_2") (pintype "passive"))
      (node (ref "C49") (pin "2") (pinfunction "2_2") (pintype "passive"))
      (node (ref "C50") (pin "2") (pinfunction "2_2") (pintype "passive"))
      (node (ref "C53") (pin "2") (pinfunction "-_2") (pintype "passive"))
      (node (ref "C54") (pin "2") (pinfunction "2_2") (pintype "passive"))
      (node (ref "C55") (pin "2") (pinfunction "2_2") (pintype "passive"))
      (node (ref "C56") (pin "2") (pinfunction "2_2") (pintype "passive"))
      (node (ref "C57") (pin "1") (pinfunction "1_1") (pintype "passive"))
      (node (ref "D11") (pin "A") (pinfunction "A_A") (pintype "passive"))
      (node (ref "D14") (pin "A") (pinfunction "A_A") (pintype "passive"))
      (node (ref "IC10") (pin "5") (pinfunction "GND_5") (pintype "power_in"))
      (node (ref "IC11") (pin "5") (pinfunction "GND_5") (pintype "power_in"))
      (node (ref "IC12") (pin "5") (pinfunction "GND_5") (pintype "power_in"))
      (node (ref "IC14") (pin "5") (pinfunction "GND_5") (pintype "power_in"))
      (node (ref "IC16") (pin "5") (pinfunction "GND_5") (pintype "power_in"))
      (node (ref "IC6") (pin "5") (pinfunction "GND_5") (pintype "power_in"))
      (node (ref "IC7") (pin "5") (pinfunction "GND_5") (pintype "power_in"))
      (node (ref "IC8") (pin "5") (pinfunction "GND_5") (pintype "power_in"))
      (node (ref "R104") (pin "2") (pinfunction "2_2") (pintype "passive"))
      (node (ref "R108") (pin "2") (pinfunction "2_2") (pintype "passive"))
      (node (ref "R113") (pin "1") (pinfunction "1_1") (pintype "passive"))
      (node (ref "R115") (pin "2") (pinfunction "2_2") (pintype "passive"))
      (node (ref "R120") (pin "2") (pinfunction "2_2") (pintype "passive"))
      (node (ref "R25") (pin "2") (pinfunction "2_2") (pintype "passive"))
      (node (ref "R26") (pin "2") (pinfunction "2_2") (pintype "passive"))
      (node (ref "R27") (pin "2") (pinfunction "2_2") (pintype "passive"))
      (node (ref "R28") (pin "2") (pinfunction "2_2") (pintype "passive"))
      (node (ref "R29") (pin "2") (pinfunction "2_2") (pintype "passive"))
      (node (ref "R30") (pin "2") (pinfunction "2_2") (pintype "passive"))
      (node (ref "R31") (pin "2") (pinfunction "2_2") (pintype "passive"))
      (node (ref "R32") (pin "2") (pinfunction "2_2") (pintype "passive"))
      (node (ref "R33") (pin "1") (pinfunction "1_1") (pintype "passive"))
      (node (ref "R35") (pin "2") (pinfunction "2_2") (pintype "passive"))
      (node (ref "R40") (pin "2") (pinfunction "2_2") (pintype "passive"))
      (node (ref "R41") (pin "1") (pinfunction "1_1") (pintype "passive"))
      (node (ref "R43") (pin "2") (pinfunction "2_2") (pintype "passive"))
      (node (ref "R48") (pin "2") (pinfunction "2_2") (pintype "passive"))
      (node (ref "R49") (pin "1") (pinfunction "1_1") (pintype "passive"))
      (node (ref "R51") (pin "2") (pinfunction "2_2") (pintype "passive"))
      (node (ref "R56") (pin "2") (pinfunction "2_2") (pintype "passive"))
      (node (ref "R65") (pin "1") (pinfunction "1_1") (pintype "passive"))
      (node (ref "R67") (pin "2") (pinfunction "2_2") (pintype "passive"))
      (node (ref "R72") (pin "2") (pinfunction "2_2") (pintype "passive"))
      (node (ref "R73") (pin "1") (pinfunction "1_1") (pintype "passive"))
      (node (ref "R75") (pin "2") (pinfunction "2_2") (pintype "passive"))
      (node (ref "R80") (pin "2") (pinfunction "2_2") (pintype "passive"))
      (node (ref "R81") (pin "1") (pinfunction "1_1") (pintype "passive"))
      (node (ref "R83") (pin "2") (pinfunction "2_2") (pintype "passive"))
      (node (ref "R88") (pin "2") (pinfunction "2_2") (pintype "passive"))
      (node (ref "R96") (pin "2") (pinfunction "2_2") (pintype "passive"))
      (node (ref "R97") (pin "1") (pinfunction "1_1") (pintype "passive"))
      (node (ref "R99") (pin "2") (pinfunction "2_2") (pintype "passive"))
    )
    (net (code "15") (name "AVDD") (class "Default")
      (node (ref "AVDD") (pin "TP") (pinfunction "P$1_TP") (pintype "bidirectional"))
      (node (ref "C62") (pin "1") (pinfunction "1_1") (pintype "passive"))
      (node (ref "C74") (pin "1") (pinfunction "1_1") (pintype "passive"))
      (node (ref "IC15") (pin "43") (pinfunction "ADC_AVDD_43") (pintype "bidirectional"))
      (node (ref "IC17") (pin "1") (pinfunction "OUT_1") (pintype "output"))
      (node (ref "IC17") (pin "4") (pinfunction "-IN_4") (pintype "input"))
    )
    (net (code "16") (name "BUCK_EN") (class "Default")
      (node (ref "IC15") (pin "37") (pinfunction "GPIO25_37") (pintype "bidirectional"))
      (node (ref "IC2") (pin "6") (pinfunction "EN_6") (pintype "bidirectional"))
      (node (ref "R1") (pin "2") (pinfunction "2_2") (pintype "passive"))
      (node (ref "R2") (pin "2") (pinfunction "2_2") (pintype "passive"))
    )
    (net (code "17") (name "CC1") (class "Default")
      (node (ref "R125") (pin "1") (pinfunction "1_1") (pintype "passive"))
      (node (ref "USB1") (pin "A5") (pinfunction "CC1_A5") (pintype "bidirectional"))
    )
    (net (code "18") (name "CC2") (class "Default")
      (node (ref "R124") (pin "1") (pinfunction "1_1") (pintype "passive"))
      (node (ref "USB1") (pin "B5") (pinfunction "CC2_B5") (pintype "bidirectional"))
    )
    (net (code "19") (name "FAN_CTRL") (class "Default")
      (node (ref "IC15") (pin "39") (pinfunction "GPIO27/ADC1_39") (pintype "bidirectional"))
      (node (ref "R164") (pin "1") (pinfunction "1_1") (pintype "passive"))
      (node (ref "R165") (pin "1") (pinfunction "1_1") (pintype "passive"))
      (node (ref "T1") (pin "1") (pinfunction "G_1") (pintype "passive"))
    )
    (net (code "20") (name "FB1") (class "Default")
      (node (ref "C5") (pin "2") (pinfunction "2_2") (pintype "passive"))
      (node (ref "FB-NI1") (pin "TP") (pinfunction "P$1_TP") (pintype "bidirectional"))
      (node (ref "IC13") (pin "2") (pinfunction "FB_2") (pintype "input"))
      (node (ref "R60") (pin "1") (pinfunction "1_1") (pintype "passive"))
      (node (ref "R61") (pin "2") (pinfunction "2_2") (pintype "passive"))
    )
    (net (code "21") (name "FB2") (class "Default")
      (node (ref "C51") (pin "2") (pinfunction "2_2") (pintype "passive"))
      (node (ref "FB-NI2") (pin "TP") (pinfunction "P$1_TP") (pintype "bidirectional"))
      (node (ref "IC5") (pin "2") (pinfunction "FB_2") (pintype "input"))
      (node (ref "R105") (pin "2") (pinfunction "2_2") (pintype "passive"))
      (node (ref "R107") (pin "1") (pinfunction "1_1") (pintype "passive"))
    )
    (net (code "22") (name "FBIN1") (class "Default")
      (node (ref "C22") (pin "2") (pinfunction "2_2") (pintype "passive"))
      (node (ref "D9") (pin "C") (pinfunction "C_C") (pintype "passive"))
      (node (ref "R61") (pin "1") (pinfunction "1_1") (pintype "passive"))
    )
    (net (code "23") (name "FBIN2") (class "Default")
      (node (ref "C52") (pin "2") (pinfunction "2_2") (pintype "passive"))
      (node (ref "D13") (pin "C") (pinfunction "C_C") (pintype "passive"))
      (node (ref "R105") (pin "1") (pinfunction "1_1") (pintype "passive"))
    )
    (net (code "24") (name "GND") (class "Default")
      (node (ref "AC/DC1") (pin "-V") (pinfunction "-V_-V") (pintype "output"))
      (node (ref "AC/DC2") (pin "-V") (pinfunction "-V_-V") (pintype "output"))
      (node (ref "BOOT") (pin "2") (pinfunction "P$2_2") (pintype "bidirectional"))
      (node (ref "C1") (pin "2") (pinfunction "2_2") (pintype "passive"))
      (node (ref "C10") (pin "2") (pinfunction "-_2") (pintype "passive"))
      (node (ref "C100") (pin "2") (pinfunction "2_2") (pintype "passive"))
      (node (ref "C101") (pin "2") (pinfunction "2_2") (pintype "passive"))
      (node (ref "C102") (pin "2") (pinfunction "2_2") (pintype "passive"))
      (node (ref "C103") (pin "2") (pinfunction "2_2") (pintype "passive"))
      (node (ref "C104") (pin "2") (pinfunction "2_2") (pintype "passive"))
      (node (ref "C13") (pin "2") (pinfunction "-_2") (pintype "passive"))
      (node (ref "C14") (pin "2") (pinfunction "2_2") (pintype "passive"))
      (node (ref "C15") (pin "2") (pinfunction "2_2") (pintype "passive"))
      (node (ref "C16") (pin "2") (pinfunction "-_2") (pintype "passive"))
      (node (ref "C17") (pin "2") (pinfunction "2_2") (pintype "passive"))
      (node (ref "C18") (pin "2") (pinfunction "2_2") (pintype "passive"))
      (node (ref "C19") (pin "2") (pinfunction "2_2") (pintype "passive"))
      (node (ref "C2") (pin "2") (pinfunction "2_2") (pintype "passive"))
      (node (ref "C20") (pin "2") (pinfunction "2_2") (pintype "passive"))
      (node (ref "C3") (pin "2") (pinfunction "2_2") (pintype "passive"))
      (node (ref "C33") (pin "2") (pinfunction "2_2") (pintype "passive"))
      (node (ref "C34") (pin "2") (pinfunction "2_2") (pintype "passive"))
      (node (ref "C4") (pin "2") (pinfunction "2_2") (pintype "passive"))
      (node (ref "C58") (pin "2") (pinfunction "2_2") (pintype "passive"))
      (node (ref "C59") (pin "2") (pinfunction "2_2") (pintype "passive"))
      (node (ref "C6") (pin "2") (pinfunction "2_2") (pintype "passive"))
      (node (ref "C60") (pin "2") (pinfunction "2_2") (pintype "passive"))
      (node (ref "C61") (pin "2") (pinfunction "2_2") (pintype "passive"))
      (node (ref "C62") (pin "2") (pinfunction "2_2") (pintype "passive"))
      (node (ref "C63") (pin "2") (pinfunction "2_2") (pintype "passive"))
      (node (ref "C64") (pin "2") (pinfunction "2_2") (pintype "passive"))
      (node (ref "C65") (pin "2") (pinfunction "2_2") (pintype "passive"))
      (node (ref "C66") (pin "2") (pinfunction "2_2") (pintype "passive"))
      (node (ref "C67") (pin "2") (pinfunction "2_2") (pintype "passive"))
      (node (ref "C68") (pin "2") (pinfunction "2_2") (pintype "passive"))
      (node (ref "C69") (pin "2") (pinfunction "2_2") (pintype "passive"))
      (node (ref "C7") (pin "2") (pinfunction "2_2") (pintype "passive"))
      (node (ref "C70") (pin "2") (pinfunction "2_2") (pintype "passive"))
      (node (ref "C71") (pin "2") (pinfunction "2_2") (pintype "passive"))
      (node (ref "C72") (pin "2") (pinfunction "2_2") (pintype "passive"))
      (node (ref "C73") (pin "2") (pinfunction "2_2") (pintype "passive"))
      (node (ref "C74") (pin "2") (pinfunction "2_2") (pintype "passive"))
      (node (ref "C75") (pin "2") (pinfunction "2_2") (pintype "passive"))
      (node (ref "C76") (pin "2") (pinfunction "2_2") (pintype "passive"))
      (node (ref "C77") (pin "2") (pinfunction "2_2") (pintype "passive"))
      (node (ref "C78") (pin "2") (pinfunction "2_2") (pintype "passive"))
      (node (ref "C79") (pin "2") (pinfunction "2_2") (pintype "passive"))
      (node (ref "C80") (pin "2") (pinfunction "2_2") (pintype "passive"))
      (node (ref "C83") (pin "1") (pinfunction "1_1") (pintype "passive"))
      (node (ref "C84") (pin "2") (pinfunction "2_2") (pintype "passive"))
      (node (ref "C85") (pin "2") (pinfunction "2_2") (pintype "passive"))
      (node (ref "C86") (pin "2") (pinfunction "2_2") (pintype "passive"))
      (node (ref "C87") (pin "2") (pinfunction "2_2") (pintype "passive"))
      (node (ref "C88") (pin "2") (pinfunction "2_2") (pintype "passive"))
      (node (ref "C89") (pin "2") (pinfunction "2_2") (pintype "passive"))
      (node (ref "C90") (pin "2") (pinfunction "2_2") (pintype "passive"))
      (node (ref "C91") (pin "2") (pinfunction "2_2") (pintype "passive"))
      (node (ref "C92") (pin "2") (pinfunction "2_2") (pintype "passive"))
      (node (ref "C93") (pin "2") (pinfunction "2_2") (pintype "passive"))
      (node (ref "C94") (pin "2") (pinfunction "2_2") (pintype "passive"))
      (node (ref "C95") (pin "2") (pinfunction "2_2") (pintype "passive"))
      (node (ref "C96") (pin "2") (pinfunction "2_2") (pintype "passive"))
      (node (ref "C97") (pin "2") (pinfunction "2_2") (pintype "passive"))
      (node (ref "C98") (pin "2") (pinfunction "2_2") (pintype "passive"))
      (node (ref "C99") (pin "2") (pinfunction "2_2") (pintype "passive"))
      (node (ref "D16") (pin "A") (pinfunction "A_A") (pintype "passive"))
      (node (ref "DAT") (pin "C") (pinfunction "C_C") (pintype "passive"))
      (node (ref "DSP") (pin "5") (pinfunction "5_5") (pintype "bidirectional"))
      (node (ref "DSP") (pin "8") (pinfunction "8_8") (pintype "bidirectional"))
      (node (ref "DSP") (pin "Z0") (pinfunction "Z1_Z0") (pintype "bidirectional"))
      (node (ref "DSP") (pin "Z1") (pinfunction "Z1_Z1") (pintype "bidirectional"))
      (node (ref "DSP") (pin "Z2") (pinfunction "Z2_Z2") (pintype "bidirectional"))
      (node (ref "DSP") (pin "Z3") (pinfunction "Z3_Z3") (pintype "bidirectional"))
      (node (ref "DSP") (pin "Z4") (pinfunction "Z3_Z4") (pintype "bidirectional"))
      (node (ref "DSP") (pin "Z5") (pinfunction "Z4_Z5") (pintype "bidirectional"))
      (node (ref "ESD1") (pin "1") (pinfunction "A_1") (pintype "bidirectional"))
      (node (ref "ETH1") (pin "8") (pinfunction "GND_8") (pintype "power_in"))
      (node (ref "GDGC") (pin "4") (pinfunction "P$4_4") (pintype "bidirectional"))
      (node (ref "GND") (pin "TP") (pinfunction "P$1_TP") (pintype "bidirectional"))
      (node (ref "GND-3") (pin "TP") (pinfunction "P$1_TP") (pintype "bidirectional"))
      (node (ref "GND-5") (pin "TP") (pinfunction "P$1_TP") (pintype "bidirectional"))
      (node (ref "IC1") (pin "4") (pinfunction "GND_4") (pintype "bidirectional"))
      (node (ref "IC15") (pin "19") (pinfunction "TESTEN_19") (pintype "bidirectional"))
      (node (ref "IC15") (pin "PAD") (pinfunction "GND_PAD") (pintype "bidirectional"))
      (node (ref "IC17") (pin "5") (pinfunction "V-_5") (pintype "power_in"))
      (node (ref "IC18") (pin "4") (pinfunction "GND_4") (pintype "power_in"))
      (node (ref "IC18") (pin "PAD") (pinfunction "GND_PAD") (pintype "power_in"))
      (node (ref "IC19") (pin "2") (pinfunction "A1_2") (pintype "bidirectional"))
      (node (ref "IC19") (pin "3") (pinfunction "A2_3") (pintype "bidirectional"))
      (node (ref "IC19") (pin "4") (pinfunction "GND_4") (pintype "power_in"))
      (node (ref "IC19") (pin "7") (pinfunction "WP_7") (pintype "bidirectional"))
      (node (ref "IC19") (pin "9") (pinfunction "GND_9") (pintype "power_in"))
      (node (ref "IC2") (pin "4") (pinfunction "GND_4") (pintype "bidirectional"))
      (node (ref "IC20") (pin "14") (pinfunction "AGND_14") (pintype "power_in"))
      (node (ref "IC20") (pin "16") (pinfunction "AGND_16") (pintype "power_in"))
      (node (ref "IC20") (pin "19") (pinfunction "AGND_19") (pintype "power_in"))
      (node (ref "IC20") (pin "29") (pinfunction "GND_29") (pintype "passive"))
      (node (ref "IC20") (pin "3") (pinfunction "AGND_3") (pintype "power_in"))
      (node (ref "IC20") (pin "48") (pinfunction "AGND_48") (pintype "power_in"))
      (node (ref "IC20") (pin "9") (pinfunction "AGND_9") (pintype "power_in"))
      (node (ref "IC21") (pin "2") (pinfunction "GND_2") (pintype "bidirectional"))
      (node (ref "IC22") (pin "5") (pinfunction "V-_5") (pintype "power_in"))
      (node (ref "IC3") (pin "9") (pinfunction "GND_9") (pintype "bidirectional"))
      (node (ref "IC4") (pin "11") (pinfunction "A0_11") (pintype "bidirectional"))
      (node (ref "IC4") (pin "12") (pinfunction "A1_12") (pintype "bidirectional"))
      (node (ref "IC4") (pin "13") (pinfunction "A2_13") (pintype "bidirectional"))
      (node (ref "IC4") (pin "6") (pinfunction "VSS_6") (pintype "bidirectional"))
      (node (ref "IC4") (pin "PAD") (pinfunction "VSS_PAD") (pintype "bidirectional"))
      (node (ref "IC9") (pin "8") (pinfunction "GND_8") (pintype "power_in"))
      (node (ref "OPT1") (pin "11") (pinfunction "11_11") (pintype "passive"))
      (node (ref "OPT1") (pin "13") (pinfunction "13_13") (pintype "passive"))
      (node (ref "OPT1") (pin "15") (pinfunction "15_15") (pintype "passive"))
      (node (ref "OPT1") (pin "9") (pinfunction "9_9") (pintype "passive"))
      (node (ref "OPT2") (pin "11") (pinfunction "11_11") (pintype "passive"))
      (node (ref "OPT2") (pin "13") (pinfunction "13_13") (pintype "passive"))
      (node (ref "OPT2") (pin "15") (pinfunction "15_15") (pintype "passive"))
      (node (ref "OPT2") (pin "9") (pinfunction "9_9") (pintype "passive"))
      (node (ref "P12ON") (pin "C") (pinfunction "C_C") (pintype "passive"))
      (node (ref "P3ON") (pin "C") (pinfunction "C_C") (pintype "passive"))
      (node (ref "P5ON") (pin "C") (pinfunction "C_C") (pintype "passive"))
      (node (ref "PROC") (pin "C") (pinfunction "C_C") (pintype "passive"))
      (node (ref "R110") (pin "1") (pinfunction "1_1") (pintype "passive"))
      (node (ref "R12") (pin "2") (pinfunction "2_2") (pintype "passive"))
      (node (ref "R121") (pin "2") (pinfunction "2_2") (pintype "passive"))
      (node (ref "R124") (pin "2") (pinfunction "2_2") (pintype "passive"))
      (node (ref "R125") (pin "2") (pinfunction "2_2") (pintype "passive"))
      (node (ref "R127") (pin "2") (pinfunction "2_2") (pintype "passive"))
      (node (ref "R129") (pin "1") (pinfunction "1_1") (pintype "passive"))
      (node (ref "R131") (pin "2") (pinfunction "2_2") (pintype "passive"))
      (node (ref "R14") (pin "2") (pinfunction "2_2") (pintype "passive"))
      (node (ref "R143") (pin "1") (pinfunction "1_1") (pintype "passive"))
      (node (ref "R151") (pin "1") (pinfunction "1_1") (pintype "passive"))
      (node (ref "R161") (pin "1") (pinfunction "1_1") (pintype "passive"))
      (node (ref "R164") (pin "2") (pinfunction "2_2") (pintype "passive"))
      (node (ref "R2") (pin "1") (pinfunction "1_1") (pintype "passive"))
      (node (ref "R4") (pin "2") (pinfunction "2_2") (pintype "passive"))
      (node (ref "R6") (pin "2") (pinfunction "2_2") (pintype "passive"))
      (node (ref "R93") (pin "A2") (pinfunction "8_A2") (pintype "passive"))
      (node (ref "R93") (pin "B2") (pinfunction "7_B2") (pintype "passive"))
      (node (ref "R93") (pin "C2") (pinfunction "6_C2") (pintype "passive"))
      (node (ref "R93") (pin "D2") (pinfunction "5_D2") (pintype "passive"))
      (node (ref "R95") (pin "1") (pinfunction "1_1") (pintype "passive"))
      (node (ref "REF1") (pin "2") (pinfunction "A_2") (pintype "passive"))
      (node (ref "REF1") (pin "3") (pinfunction "A_3") (pintype "passive"))
      (node (ref "RESET") (pin "1") (pinfunction "P$1_1") (pintype "bidirectional"))
      (node (ref "RGTG") (pin "2") (pinfunction "P$2_2") (pintype "bidirectional"))
      (node (ref "RGTG") (pin "4") (pinfunction "P$4_4") (pintype "bidirectional"))
      (node (ref "T1") (pin "2") (pinfunction "S_2") (pintype "passive"))
      (node (ref "USB1") (pin "GND") (pinfunction "GND_GND") (pintype "power_in"))
      (node (ref "USB1") (pin "GND2") (pinfunction "GND_GND2") (pintype "power_in"))
      (node (ref "X1") (pin "2") (pinfunction "GND_2") (pintype "passive"))
      (node (ref "X1") (pin "4") (pinfunction "GND_4") (pintype "passive"))
      (node (ref "X2") (pin "2") (pinfunction "GND_2") (pintype "passive"))
      (node (ref "X2") (pin "4") (pinfunction "GND_4") (pintype "passive"))
    )
    (net (code "25") (name "I2C0_SCL") (class "Default")
      (node (ref "DSP") (pin "7") (pinfunction "7_7") (pintype "bidirectional"))
      (node (ref "IC15") (pin "7") (pinfunction "GPIO5_7") (pintype "bidirectional"))
      (node (ref "R130") (pin "A1") (pinfunction "1_A1") (pintype "passive"))
      (node (ref "SCL0") (pin "TP") (pinfunction "P$1_TP") (pintype "bidirectional"))
    )
    (net (code "26") (name "I2C0_SDA") (class "Default")
      (node (ref "DSP") (pin "6") (pinfunction "6_6") (pintype "bidirectional"))
      (node (ref "IC15") (pin "6") (pinfunction "GPIO4_6") (pintype "bidirectional"))
      (node (ref "R130") (pin "B1") (pinfunction "2_B1") (pintype "passive"))
      (node (ref "SDA0") (pin "TP") (pinfunction "P$1_TP") (pintype "bidirectional"))
    )
    (net (code "27") (name "I2C1_SCL") (class "Default")
      (node (ref "IC15") (pin "5") (pinfunction "GPIO3_5") (pintype "bidirectional"))
      (node (ref "IC19") (pin "6") (pinfunction "SCL_6") (pintype "bidirectional"))
      (node (ref "IC4") (pin "8") (pinfunction "SCL_8") (pintype "bidirectional"))
      (node (ref "R130") (pin "C1") (pinfunction "3_C1") (pintype "passive"))
      (node (ref "SCL1") (pin "TP") (pinfunction "P$1_TP") (pintype "bidirectional"))
    )
    (net (code "28") (name "I2C1_SDA") (class "Default")
      (node (ref "IC15") (pin "4") (pinfunction "GPIO2_4") (pintype "bidirectional"))
      (node (ref "IC19") (pin "5") (pinfunction "SDA_5") (pintype "bidirectional"))
      (node (ref "IC4") (pin "9") (pinfunction "SDA_9") (pintype "bidirectional"))
      (node (ref "R130") (pin "D1") (pinfunction "4_D1") (pintype "passive"))
      (node (ref "SDA1") (pin "TP") (pinfunction "P$1_TP") (pintype "bidirectional"))
    )
    (net (code "29") (name "KEY_0") (class "Default")
      (node (ref "DSP") (pin "12") (pinfunction "12_12") (pintype "bidirectional"))
      (node (ref "IC15") (pin "15") (pinfunction "GPIO12_15") (pintype "bidirectional"))
    )
    (net (code "30") (name "KEY_1") (class "Default")
      (node (ref "DSP") (pin "11") (pinfunction "11_11") (pintype "bidirectional"))
      (node (ref "IC15") (pin "16") (pinfunction "GPIO13_16") (pintype "bidirectional"))
    )
    (net (code "31") (name "KEY_2") (class "Default")
      (node (ref "DSP") (pin "10") (pinfunction "10_10") (pintype "bidirectional"))
      (node (ref "IC15") (pin "17") (pinfunction "GPIO14_17") (pintype "bidirectional"))
    )
    (net (code "32") (name "KEY_3") (class "Default")
      (node (ref "DSP") (pin "9") (pinfunction "9_9") (pintype "bidirectional"))
      (node (ref "IC15") (pin "18") (pinfunction "GPIO15_18") (pintype "bidirectional"))
    )
    (net (code "33") (name "LCD_BL") (class "Default")
      (node (ref "DSP") (pin "13") (pinfunction "13_13") (pintype "bidirectional"))
      (node (ref "IC15") (pin "9") (pinfunction "GPIO7_9") (pintype "bidirectional"))
    )
    (net (code "34") (name "LCD_DC") (class "Default")
      (node (ref "DSP") (pin "18") (pinfunction "18_18") (pintype "bidirectional"))
      (node (ref "IC15") (pin "8") (pinfunction "GPIO6_8") (pintype "bidirectional"))
    )
    (net (code "35") (name "LCD_RES") (class "Default")
      (node (ref "DSP") (pin "14") (pinfunction "14_14") (pintype "bidirectional"))
      (node (ref "IC15") (pin "34") (pinfunction "GPIO22_34") (pintype "bidirectional"))
      (node (ref "R149") (pin "A2") (pinfunction "8_A2") (pintype "passive"))
    )
    (net (code "36") (name "LREC1") (class "Default")
      (node (ref "C35") (pin "1") (pinfunction "+_1") (pintype "passive"))
      (node (ref "D10") (pin "C") (pinfunction "C_C") (pintype "passive"))
      (node (ref "IC13") (pin "5") (pinfunction "DRAIN_5") (pintype "input"))
      (node (ref "L-REC1") (pin "TP") (pinfunction "P$1_TP") (pintype "bidirectional"))
    )
    (net (code "37") (name "LREC2") (class "Default")
      (node (ref "C47") (pin "1") (pinfunction "+_1") (pintype "passive"))
      (node (ref "D12") (pin "C") (pinfunction "C_C") (pintype "passive"))
      (node (ref "IC5") (pin "5") (pinfunction "DRAIN_5") (pintype "input"))
      (node (ref "L-REC2") (pin "TP") (pinfunction "P$1_TP") (pintype "bidirectional"))
    )
    (net (code "38") (name "MCP_DSP_RST") (class "Default")
      (node (ref "DSP") (pin "20") (pinfunction "20_20") (pintype "bidirectional"))
      (node (ref "IC15") (pin "36") (pinfunction "GPIO24_36") (pintype "bidirectional"))
      (node (ref "R147") (pin "1") (pinfunction "1_1") (pintype "passive"))
    )
    (net (code "39") (name "MCP_REL_RST") (class "Default")
      (node (ref "IC15") (pin "35") (pinfunction "GPIO23_35") (pintype "bidirectional"))
      (node (ref "IC4") (pin "14") (pinfunction "~{RESET}_14") (pintype "bidirectional"))
    )
    (net (code "40") (name "MCP_VIN") (class "Default")
      (node (ref "C102") (pin "1") (pinfunction "1_1") (pintype "passive"))
      (node (ref "C63") (pin "1") (pinfunction "1_1") (pintype "passive"))
      (node (ref "IC17") (pin "2") (pinfunction "V+_2") (pintype "power_in"))
      (node (ref "R152") (pin "2") (pinfunction "2_2") (pintype "passive"))
    )
    (net (code "41") (name "MUX_A") (class "Default")
      (node (ref "IC4") (pin "25") (pinfunction "IO2.0_25") (pintype "bidirectional"))
      (node (ref "IC9") (pin "11") (pinfunction "A_11") (pintype "input"))
      (node (ref "R93") (pin "D1") (pinfunction "4_D1") (pintype "passive"))
    )
    (net (code "42") (name "MUX_B") (class "Default")
      (node (ref "IC4") (pin "26") (pinfunction "IO2.1_26") (pintype "bidirectional"))
      (node (ref "IC9") (pin "10") (pinfunction "B_10") (pintype "input"))
      (node (ref "R93") (pin "C1") (pinfunction "3_C1") (pintype "passive"))
    )
    (net (code "43") (name "MUX_C") (class "Default")
      (node (ref "IC4") (pin "27") (pinfunction "IO2.2_27") (pintype "bidirectional"))
      (node (ref "IC9") (pin "9") (pinfunction "C_9") (pintype "input"))
      (node (ref "R93") (pin "B1") (pinfunction "2_B1") (pintype "passive"))
    )
    (net (code "44") (name "MUX_EN") (class "Default")
      (node (ref "IC4") (pin "28") (pinfunction "IO2.3_28") (pintype "bidirectional"))
      (node (ref "IC9") (pin "7") (pinfunction "~{EN}_7") (pintype "input"))
      (node (ref "R93") (pin "A1") (pinfunction "1_A1") (pintype "passive"))
    )
    (net (code "45") (name "N_OUT1") (class "Default")
      (node (ref "N_OUT1") (pin "B2,8") (pinfunction "MOUNT_B2,8") (pintype "passive"))
      (node (ref "R25") (pin "1") (pinfunction "1_1") (pintype "passive"))
      (node (ref "R34") (pin "1") (pinfunction "1_1") (pintype "passive"))
      (node (ref "R35") (pin "1") (pinfunction "1_1") (pintype "passive"))
    )
    (net (code "46") (name "N_OUT2") (class "Default")
      (node (ref "N_OUT2") (pin "B2,8") (pinfunction "MOUNT_B2,8") (pintype "passive"))
      (node (ref "R32") (pin "1") (pinfunction "1_1") (pintype "passive"))
      (node (ref "R50") (pin "1") (pinfunction "1_1") (pintype "passive"))
      (node (ref "R51") (pin "1") (pinfunction "1_1") (pintype "passive"))
    )
    (net (code "47") (name "N_OUT3") (class "Default")
      (node (ref "N_OUT3") (pin "B2,8") (pinfunction "MOUNT_B2,8") (pintype "passive"))
      (node (ref "R31") (pin "1") (pinfunction "1_1") (pintype "passive"))
      (node (ref "R66") (pin "1") (pinfunction "1_1") (pintype "passive"))
      (node (ref "R67") (pin "1") (pinfunction "1_1") (pintype "passive"))
    )
    (net (code "48") (name "N_OUT4") (class "Default")
      (node (ref "N_OUT4") (pin "B2,8") (pinfunction "MOUNT_B2,8") (pintype "passive"))
      (node (ref "R30") (pin "1") (pinfunction "1_1") (pintype "passive"))
      (node (ref "R82") (pin "1") (pinfunction "1_1") (pintype "passive"))
      (node (ref "R83") (pin "1") (pinfunction "1_1") (pintype "passive"))
    )
    (net (code "49") (name "N_OUT5") (class "Default")
      (node (ref "N_OUT5") (pin "B2,8") (pinfunction "MOUNT_B2,8") (pintype "passive"))
      (node (ref "R26") (pin "1") (pinfunction "1_1") (pintype "passive"))
      (node (ref "R42") (pin "1") (pinfunction "1_1") (pintype "passive"))
      (node (ref "R43") (pin "1") (pinfunction "1_1") (pintype "passive"))
    )
    (net (code "50") (name "N_OUT6") (class "Default")
      (node (ref "N_OUT6") (pin "B2,8") (pinfunction "MOUNT_B2,8") (pintype "passive"))
      (node (ref "R27") (pin "1") (pinfunction "1_1") (pintype "passive"))
      (node (ref "R74") (pin "1") (pinfunction "1_1") (pintype "passive"))
      (node (ref "R75") (pin "1") (pinfunction "1_1") (pintype "passive"))
    )
    (net (code "51") (name "N_OUT7") (class "Default")
      (node (ref "N_OUT7") (pin "B2,8") (pinfunction "MOUNT_B2,8") (pintype "passive"))
      (node (ref "R28") (pin "1") (pinfunction "1_1") (pintype "passive"))
      (node (ref "R98") (pin "1") (pinfunction "1_1") (pintype "passive"))
      (node (ref "R99") (pin "1") (pinfunction "1_1") (pintype "passive"))
    )
    (net (code "52") (name "N_OUT8") (class "Default")
      (node (ref "N_OUT8") (pin "B2,8") (pinfunction "MOUNT_B2,8") (pintype "passive"))
      (node (ref "R114") (pin "1") (pinfunction "1_1") (pintype "passive"))
      (node (ref "R115") (pin "1") (pinfunction "1_1") (pintype "passive"))
      (node (ref "R29") (pin "1") (pinfunction "1_1") (pintype "passive"))
    )
    (net (code "53") (name "Net-(3VFB-P$1)") (class "Default")
      (node (ref "3VFB") (pin "TP") (pinfunction "P$1_TP") (pintype "bidirectional"))
      (node (ref "C12") (pin "2") (pinfunction "2_2") (pintype "passive"))
      (node (ref "R10") (pin "2") (pinfunction "2_2") (pintype "passive"))
      (node (ref "R13") (pin "2") (pinfunction "2_2") (pintype "passive"))
      (node (ref "R14") (pin "1") (pinfunction "1_1") (pintype "passive"))
    )
    (net (code "54") (name "Net-(5VFB-P$1)") (class "Default")
      (node (ref "5VFB") (pin "TP") (pinfunction "P$1_TP") (pintype "bidirectional"))
      (node (ref "C11") (pin "2") (pinfunction "2_2") (pintype "passive"))
      (node (ref "R11") (pin "2") (pinfunction "2_2") (pintype "passive"))
      (node (ref "R12") (pin "1") (pinfunction "1_1") (pintype "passive"))
      (node (ref "R8") (pin "2") (pinfunction "2_2") (pintype "passive"))
    )
    (net (code "55") (name "Net-(12VDC-P$1)") (class "Default")
      (node (ref "12VDC") (pin "TP") (pinfunction "P$1_TP") (pintype "bidirectional"))
      (node (ref "AC/DC1") (pin "+V") (pinfunction "+V_+V") (pintype "output"))
      (node (ref "AC/DC2") (pin "+V") (pinfunction "+V_+V") (pintype "output"))
      (node (ref "C10") (pin "1") (pinfunction "+_1") (pintype "passive"))
      (node (ref "C13") (pin "1") (pinfunction "+_1") (pintype "passive"))
      (node (ref "C16") (pin "1") (pinfunction "+_1") (pintype "passive"))
      (node (ref "D16") (pin "C") (pinfunction "C_C") (pintype "passive"))
      (node (ref "J10") (pin "2") (pinfunction "2_2") (pintype "passive"))
      (node (ref "J8") (pin "2") (pinfunction "2_2") (pintype "passive"))
      (node (ref "J9") (pin "2") (pinfunction "2_2") (pintype "passive"))
    )
    (net (code "56") (name "Net-(C8-Pad1)") (class "Default")
      (node (ref "C8") (pin "1") (pinfunction "1_1") (pintype "passive"))
      (node (ref "R7") (pin "1") (pinfunction "1_1") (pintype "passive"))
    )
    (net (code "57") (name "Net-(C9-Pad1)") (class "Default")
      (node (ref "C9") (pin "1") (pinfunction "1_1") (pintype "passive"))
      (node (ref "R9") (pin "1") (pinfunction "1_1") (pintype "passive"))
    )
    (net (code "58") (name "Net-(C106-Pad1)") (class "Default")
      (node (ref "C106") (pin "1") (pinfunction "1_1") (pintype "passive"))
      (node (ref "OPT1") (pin "2") (pinfunction "2_2") (pintype "passive"))
      (node (ref "R59") (pin "2") (pinfunction "2_2") (pintype "passive"))
    )
    (net (code "59") (name "Net-(C107-Pad1)") (class "Default")
      (node (ref "C107") (pin "1") (pinfunction "1_1") (pintype "passive"))
      (node (ref "OPT1") (pin "4") (pinfunction "4_4") (pintype "passive"))
      (node (ref "R153") (pin "2") (pinfunction "2_2") (pintype "passive"))
    )
    (net (code "60") (name "Net-(C108-Pad1)") (class "Default")
      (node (ref "C108") (pin "1") (pinfunction "1_1") (pintype "passive"))
      (node (ref "OPT1") (pin "6") (pinfunction "6_6") (pintype "passive"))
      (node (ref "R154") (pin "2") (pinfunction "2_2") (pintype "passive"))
    )
    (net (code "61") (name "Net-(C109-Pad1)") (class "Default")
      (node (ref "C109") (pin "1") (pinfunction "1_1") (pintype "passive"))
      (node (ref "OPT1") (pin "8") (pinfunction "8_8") (pintype "passive"))
      (node (ref "R155") (pin "2") (pinfunction "2_2") (pintype "passive"))
    )
    (net (code "62") (name "Net-(C110-Pad1)") (class "Default")
      (node (ref "C110") (pin "1") (pinfunction "1_1") (pintype "passive"))
      (node (ref "OPT2") (pin "2") (pinfunction "2_2") (pintype "passive"))
      (node (ref "R156") (pin "2") (pinfunction "2_2") (pintype "passive"))
    )
    (net (code "63") (name "Net-(C111-Pad1)") (class "Default")
      (node (ref "C111") (pin "1") (pinfunction "1_1") (pintype "passive"))
      (node (ref "OPT2") (pin "4") (pinfunction "4_4") (pintype "passive"))
      (node (ref "R157") (pin "2") (pinfunction "2_2") (pintype "passive"))
    )
    (net (code "64") (name "Net-(C112-Pad1)") (class "Default")
      (node (ref "C112") (pin "1") (pinfunction "1_1") (pintype "passive"))
      (node (ref "OPT2") (pin "6") (pinfunction "6_6") (pintype "passive"))
      (node (ref "R158") (pin "2") (pinfunction "2_2") (pintype "passive"))
    )
    (net (code "65") (name "Net-(C113-Pad1)") (class "Default")
      (node (ref "C113") (pin "1") (pinfunction "1_1") (pintype "passive"))
      (node (ref "OPT2") (pin "8") (pinfunction "8_8") (pintype "passive"))
      (node (ref "R159") (pin "2") (pinfunction "2_2") (pintype "passive"))
    )
    (net (code "66") (name "Net-(D10-PadA)") (class "Default")
      (node (ref "D10") (pin "A") (pinfunction "A_A") (pintype "passive"))
      (node (ref "R62") (pin "2") (pinfunction "2_2") (pintype "passive"))
    )
    (net (code "67") (name "Net-(D12-PadA)") (class "Default")
      (node (ref "D12") (pin "A") (pinfunction "A_A") (pintype "passive"))
      (node (ref "R106") (pin "2") (pinfunction "2_2") (pintype "passive"))
    )
    (net (code "68") (name "Net-(DAT-PadA)") (class "Default")
      (node (ref "DAT") (pin "A") (pinfunction "A_A") (pintype "passive"))
      (node (ref "R122") (pin "2") (pinfunction "2_2") (pintype "passive"))
    )
    (net (code "69") (name "Net-(ETH1-GREEN-)") (class "Default")
      (node (ref "ETH1") (pin "9") (pinfunction "GREEN-_9") (pintype "passive"))
      (node (ref "R142") (pin "2") (pinfunction "2_2") (pintype "passive"))
    )
    (net (code "70") (name "Net-(ETH1-YELLOW-)") (class "Default")
      (node (ref "ETH1") (pin "11") (pinfunction "YELLOW-_11") (pintype "passive"))
      (node (ref "R141") (pin "2") (pinfunction "2_2") (pintype "passive"))
    )
    (net (code "71") (name "Net-(IC1-AAM)") (class "Default")
      (node (ref "IC1") (pin "1") (pinfunction "AAM_1") (pintype "bidirectional"))
      (node (ref "R3") (pin "2") (pinfunction "2_2") (pintype "passive"))
      (node (ref "R4") (pin "1") (pinfunction "1_1") (pintype "passive"))
    )
    (net (code "72") (name "Net-(IC1-BST)") (class "Default")
      (node (ref "IC1") (pin "5") (pinfunction "BST_5") (pintype "bidirectional"))
      (node (ref "R7") (pin "2") (pinfunction "2_2") (pintype "passive"))
    )
    (net (code "73") (name "Net-(IC1-FB)") (class "Default")
      (node (ref "IC1") (pin "8") (pinfunction "FB_8") (pintype "bidirectional"))
      (node (ref "R8") (pin "1") (pinfunction "1_1") (pintype "passive"))
    )
    (net (code "74") (name "Net-(IC1-SW)") (class "Default")
      (node (ref "C8") (pin "2") (pinfunction "2_2") (pintype "passive"))
      (node (ref "IC1") (pin "3") (pinfunction "SW_3") (pintype "bidirectional"))
      (node (ref "L1") (pin "1") (pinfunction "1_1") (pintype "passive"))
      (node (ref "SW") (pin "TP") (pinfunction "P$1_TP") (pintype "bidirectional"))
    )
    (net (code "75") (name "Net-(IC1-VCC)") (class "Default")
      (node (ref "C6") (pin "1") (pinfunction "1_1") (pintype "passive"))
      (node (ref "IC1") (pin "7") (pinfunction "VCC_7") (pintype "bidirectional"))
      (node (ref "R3") (pin "1") (pinfunction "1_1") (pintype "passive"))
    )
    (net (code "76") (name "Net-(IC2-AAM)") (class "Default")
      (node (ref "IC2") (pin "1") (pinfunction "AAM_1") (pintype "bidirectional"))
      (node (ref "R5") (pin "2") (pinfunction "2_2") (pintype "passive"))
      (node (ref "R6") (pin "1") (pinfunction "1_1") (pintype "passive"))
    )
    (net (code "77") (name "Net-(IC2-BST)") (class "Default")
      (node (ref "IC2") (pin "5") (pinfunction "BST_5") (pintype "bidirectional"))
      (node (ref "R9") (pin "2") (pinfunction "2_2") (pintype "passive"))
    )
    (net (code "78") (name "Net-(IC2-FB)") (class "Default")
      (node (ref "IC2") (pin "8") (pinfunction "FB_8") (pintype "bidirectional"))
      (node (ref "R10") (pin "1") (pinfunction "1_1") (pintype "passive"))
    )
    (net (code "79") (name "Net-(IC2-SW)") (class "Default")
      (node (ref "C9") (pin "2") (pinfunction "2_2") (pintype "passive"))
      (node (ref "IC2") (pin "3") (pinfunction "SW_3") (pintype "bidirectional"))
      (node (ref "L2") (pin "1") (pinfunction "1_1") (pintype "passive"))
      (node (ref "SW3") (pin "TP") (pinfunction "P$1_TP") (pintype "bidirectional"))
    )
    (net (code "80") (name "Net-(IC2-VCC)") (class "Default")
      (node (ref "C7") (pin "1") (pinfunction "1_1") (pintype "passive"))
      (node (ref "IC2") (pin "7") (pinfunction "VCC_7") (pintype "bidirectional"))
      (node (ref "R5") (pin "1") (pinfunction "1_1") (pintype "passive"))
    )
    (net (code "81") (name "Net-(IC3-1C)") (class "Default")
      (node (ref "IC3") (pin "18") (pinfunction "1C_18") (pintype "bidirectional"))
      (node (ref "R17") (pin "1") (pinfunction "1_1") (pintype "passive"))
    )
    (net (code "82") (name "Net-(IC3-2C)") (class "Default")
      (node (ref "IC3") (pin "17") (pinfunction "2C_17") (pintype "bidirectional"))
      (node (ref "R18") (pin "1") (pinfunction "1_1") (pintype "passive"))
    )
    (net (code "83") (name "Net-(IC3-3C)") (class "Default")
      (node (ref "IC3") (pin "16") (pinfunction "3C_16") (pintype "bidirectional"))
      (node (ref "R19") (pin "1") (pinfunction "1_1") (pintype "passive"))
    )
    (net (code "84") (name "Net-(IC3-4C)") (class "Default")
      (node (ref "IC3") (pin "15") (pinfunction "4C_15") (pintype "bidirectional"))
      (node (ref "R20") (pin "1") (pinfunction "1_1") (pintype "passive"))
    )
    (net (code "85") (name "Net-(IC3-5C)") (class "Default")
      (node (ref "IC3") (pin "14") (pinfunction "5C_14") (pintype "bidirectional"))
      (node (ref "R21") (pin "1") (pinfunction "1_1") (pintype "passive"))
    )
    (net (code "86") (name "Net-(IC3-6C)") (class "Default")
      (node (ref "IC3") (pin "13") (pinfunction "6C_13") (pintype "bidirectional"))
      (node (ref "R22") (pin "1") (pinfunction "1_1") (pintype "passive"))
    )
    (net (code "87") (name "Net-(IC3-7C)") (class "Default")
      (node (ref "IC3") (pin "12") (pinfunction "7C_12") (pintype "bidirectional"))
      (node (ref "R23") (pin "1") (pinfunction "1_1") (pintype "passive"))
    )
    (net (code "88") (name "Net-(IC3-8C)") (class "Default")
      (node (ref "IC3") (pin "11") (pinfunction "8C_11") (pintype "bidirectional"))
      (node (ref "R24") (pin "1") (pinfunction "1_1") (pintype "passive"))
    )
    (net (code "89") (name "Net-(IC6-INN)") (class "Default")
      (node (ref "C25") (pin "1") (pinfunction "1_1") (pintype "passive"))
      (node (ref "IC6") (pin "3") (pinfunction "INN_3") (pintype "input"))
      (node (ref "R34") (pin "2") (pinfunction "2_2") (pintype "passive"))
    )
    (net (code "90") (name "Net-(IC6-INP)") (class "Default")
      (node (ref "C24") (pin "1") (pinfunction "1_1") (pintype "passive"))
      (node (ref "IC6") (pin "2") (pinfunction "INP_2") (pintype "input"))
      (node (ref "R33") (pin "2") (pinfunction "2_2") (pintype "passive"))
    )
    (net (code "91") (name "Net-(IC6-VP)") (class "Default")
      (node (ref "C26") (pin "1") (pinfunction "1_1") (pintype "passive"))
      (node (ref "IC6") (pin "4") (pinfunction "VP_4") (pintype "input"))
      (node (ref "R39") (pin "2") (pinfunction "2_2") (pintype "passive"))
      (node (ref "R40") (pin "1") (pinfunction "1_1") (pintype "passive"))
    )
    (net (code "92") (name "Net-(IC7-INN)") (class "Default")
      (node (ref "C28") (pin "1") (pinfunction "1_1") (pintype "passive"))
      (node (ref "IC7") (pin "3") (pinfunction "INN_3") (pintype "input"))
      (node (ref "R42") (pin "2") (pinfunction "2_2") (pintype "passive"))
    )
    (net (code "93") (name "Net-(IC7-INP)") (class "Default")
      (node (ref "C27") (pin "1") (pinfunction "1_1") (pintype "passive"))
      (node (ref "IC7") (pin "2") (pinfunction "INP_2") (pintype "input"))
      (node (ref "R41") (pin "2") (pinfunction "2_2") (pintype "passive"))
    )
    (net (code "94") (name "Net-(IC7-VP)") (class "Default")
      (node (ref "C29") (pin "1") (pinfunction "1_1") (pintype "passive"))
      (node (ref "IC7") (pin "4") (pinfunction "VP_4") (pintype "input"))
      (node (ref "R47") (pin "2") (pinfunction "2_2") (pintype "passive"))
      (node (ref "R48") (pin "1") (pinfunction "1_1") (pintype "passive"))
    )
    (net (code "95") (name "Net-(IC8-INN)") (class "Default")
      (node (ref "C31") (pin "1") (pinfunction "1_1") (pintype "passive"))
      (node (ref "IC8") (pin "3") (pinfunction "INN_3") (pintype "input"))
      (node (ref "R50") (pin "2") (pinfunction "2_2") (pintype "passive"))
    )
    (net (code "96") (name "Net-(IC8-INP)") (class "Default")
      (node (ref "C30") (pin "1") (pinfunction "1_1") (pintype "passive"))
      (node (ref "IC8") (pin "2") (pinfunction "INP_2") (pintype "input"))
      (node (ref "R49") (pin "2") (pinfunction "2_2") (pintype "passive"))
    )
    (net (code "97") (name "Net-(IC8-VP)") (class "Default")
      (node (ref "C32") (pin "1") (pinfunction "1_1") (pintype "passive"))
      (node (ref "IC8") (pin "4") (pinfunction "VP_4") (pintype "input"))
      (node (ref "R55") (pin "2") (pinfunction "2_2") (pintype "passive"))
      (node (ref "R56") (pin "1") (pinfunction "1_1") (pintype "passive"))
    )
    (net (code "98") (name "Net-(IC10-INN)") (class "Default")
      (node (ref "C37") (pin "1") (pinfunction "1_1") (pintype "passive"))
      (node (ref "IC10") (pin "3") (pinfunction "INN_3") (pintype "input"))
      (node (ref "R66") (pin "2") (pinfunction "2_2") (pintype "passive"))
    )
    (net (code "99") (name "Net-(IC10-INP)") (class "Default")
      (node (ref "C36") (pin "1") (pinfunction "1_1") (pintype "passive"))
      (node (ref "IC10") (pin "2") (pinfunction "INP_2") (pintype "input"))
      (node (ref "R65") (pin "2") (pinfunction "2_2") (pintype "passive"))
    )
    (net (code "100") (name "Net-(IC10-VP)") (class "Default")
      (node (ref "C38") (pin "1") (pinfunction "1_1") (pintype "passive"))
      (node (ref "IC10") (pin "4") (pinfunction "VP_4") (pintype "input"))
      (node (ref "R71") (pin "2") (pinfunction "2_2") (pintype "passive"))
      (node (ref "R72") (pin "1") (pinfunction "1_1") (pintype "passive"))
    )
    (net (code "101") (name "Net-(IC11-INN)") (class "Default")
      (node (ref "C40") (pin "1") (pinfunction "1_1") (pintype "passive"))
      (node (ref "IC11") (pin "3") (pinfunction "INN_3") (pintype "input"))
      (node (ref "R74") (pin "2") (pinfunction "2_2") (pintype "passive"))
    )
    (net (code "102") (name "Net-(IC11-INP)") (class "Default")
      (node (ref "C39") (pin "1") (pinfunction "1_1") (pintype "passive"))
      (node (ref "IC11") (pin "2") (pinfunction "INP_2") (pintype "input"))
      (node (ref "R73") (pin "2") (pinfunction "2_2") (pintype "passive"))
    )
    (net (code "103") (name "Net-(IC11-VP)") (class "Default")
      (node (ref "C41") (pin "1") (pinfunction "1_1") (pintype "passive"))
      (node (ref "IC11") (pin "4") (pinfunction "VP_4") (pintype "input"))
      (node (ref "R79") (pin "2") (pinfunction "2_2") (pintype "passive"))
      (node (ref "R80") (pin "1") (pinfunction "1_1") (pintype "passive"))
    )
    (net (code "104") (name "Net-(IC12-INN)") (class "Default")
      (node (ref "C43") (pin "1") (pinfunction "1_1") (pintype "passive"))
      (node (ref "IC12") (pin "3") (pinfunction "INN_3") (pintype "input"))
      (node (ref "R82") (pin "2") (pinfunction "2_2") (pintype "passive"))
    )
    (net (code "105") (name "Net-(IC12-INP)") (class "Default")
      (node (ref "C42") (pin "1") (pinfunction "1_1") (pintype "passive"))
      (node (ref "IC12") (pin "2") (pinfunction "INP_2") (pintype "input"))
      (node (ref "R81") (pin "2") (pinfunction "2_2") (pintype "passive"))
    )
    (net (code "106") (name "Net-(IC12-VP)") (class "Default")
      (node (ref "C44") (pin "1") (pinfunction "1_1") (pintype "passive"))
      (node (ref "IC12") (pin "4") (pinfunction "VP_4") (pintype "input"))
      (node (ref "R87") (pin "2") (pinfunction "2_2") (pintype "passive"))
      (node (ref "R88") (pin "1") (pinfunction "1_1") (pintype "passive"))
    )
    (net (code "107") (name "Net-(IC14-INN)") (class "Default")
      (node (ref "C49") (pin "1") (pinfunction "1_1") (pintype "passive"))
      (node (ref "IC14") (pin "3") (pinfunction "INN_3") (pintype "input"))
      (node (ref "R98") (pin "2") (pinfunction "2_2") (pintype "passive"))
    )
    (net (code "108") (name "Net-(IC14-INP)") (class "Default")
      (node (ref "C48") (pin "1") (pinfunction "1_1") (pintype "passive"))
      (node (ref "IC14") (pin "2") (pinfunction "INP_2") (pintype "input"))
      (node (ref "R97") (pin "2") (pinfunction "2_2") (pintype "passive"))
    )
    (net (code "109") (name "Net-(IC14-VP)") (class "Default")
      (node (ref "C50") (pin "1") (pinfunction "1_1") (pintype "passive"))
      (node (ref "IC14") (pin "4") (pinfunction "VP_4") (pintype "input"))
      (node (ref "R103") (pin "2") (pinfunction "2_2") (pintype "passive"))
      (node (ref "R104") (pin "1") (pinfunction "1_1") (pintype "passive"))
    )
    (net (code "110") (name "Net-(IC15-GPIO28{slash}ADC2)") (class "Default")
      (node (ref "IC15") (pin "40") (pinfunction "GPIO28/ADC2_40") (pintype "bidirectional"))
      (node (ref "R163") (pin "2") (pinfunction "2_2") (pintype "passive"))
    )
    (net (code "111") (name "Net-(IC15-USB_DM)") (class "Default")
      (node (ref "IC15") (pin "46") (pinfunction "USB_DM_46") (pintype "bidirectional"))
      (node (ref "R15") (pin "2") (pinfunction "2_2") (pintype "passive"))
    )
    (net (code "112") (name "Net-(IC15-USB_DP)") (class "Default")
      (node (ref "IC15") (pin "47") (pinfunction "USB_DP_47") (pintype "bidirectional"))
      (node (ref "R160") (pin "2") (pinfunction "2_2") (pintype "passive"))
    )
    (net (code "113") (name "Net-(IC16-INN)") (class "Default")
      (node (ref "C55") (pin "1") (pinfunction "1_1") (pintype "passive"))
      (node (ref "IC16") (pin "3") (pinfunction "INN_3") (pintype "input"))
      (node (ref "R114") (pin "2") (pinfunction "2_2") (pintype "passive"))
    )
    (net (code "114") (name "Net-(IC16-INP)") (class "Default")
      (node (ref "C54") (pin "1") (pinfunction "1_1") (pintype "passive"))
      (node (ref "IC16") (pin "2") (pinfunction "INP_2") (pintype "input"))
      (node (ref "R113") (pin "2") (pinfunction "2_2") (pintype "passive"))
    )
    (net (code "115") (name "Net-(IC16-VP)") (class "Default")
      (node (ref "C56") (pin "1") (pinfunction "1_1") (pintype "passive"))
      (node (ref "IC16") (pin "4") (pinfunction "VP_4") (pintype "input"))
      (node (ref "R119") (pin "2") (pinfunction "2_2") (pintype "passive"))
      (node (ref "R120") (pin "1") (pinfunction "1_1") (pintype "passive"))
    )
    (net (code "116") (name "Net-(IC17-+IN)") (class "Default")
      (node (ref "C60") (pin "1") (pinfunction "1_1") (pintype "passive"))
      (node (ref "C61") (pin "1") (pinfunction "1_1") (pintype "passive"))
      (node (ref "IC17") (pin "3") (pinfunction "+IN_3") (pintype "input"))
      (node (ref "R109") (pin "1") (pinfunction "1_1") (pintype "passive"))
      (node (ref "REF1") (pin "1") (pinfunction "C_1") (pintype "passive"))
      (node (ref "VREF") (pin "TP") (pinfunction "P$1_TP") (pintype "bidirectional"))
    )
    (net (code "117") (name "Net-(IC19-A0)") (class "Default")
      (node (ref "IC19") (pin "1") (pinfunction "A0_1") (pintype "bidirectional"))
      (node (ref "R128") (pin "1") (pinfunction "1_1") (pintype "passive"))
      (node (ref "R129") (pin "2") (pinfunction "2_2") (pintype "passive"))
    )
    (net (code "118") (name "Net-(IC20-1V2O)") (class "Default")
      (node (ref "C84") (pin "1") (pinfunction "1_1") (pintype "passive"))
      (node (ref "IC20") (pin "22") (pinfunction "1V2O_22") (pintype "output"))
    )
    (net (code "119") (name "Net-(IC20-EXRES1)") (class "Default")
      (node (ref "IC20") (pin "10") (pinfunction "EXRES1_10") (pintype "bidirectional"))
      (node (ref "R143") (pin "2") (pinfunction "2_2") (pintype "passive"))
    )
    (net (code "120") (name "Net-(IC20-TOCAP)") (class "Default")
      (node (ref "C85") (pin "1") (pinfunction "1_1") (pintype "passive"))
      (node (ref "IC20") (pin "20") (pinfunction "TOCAP_20") (pintype "output"))
    )
    (net (code "121") (name "Net-(IC20-XI)") (class "Default")
      (node (ref "C87") (pin "1") (pinfunction "1_1") (pintype "passive"))
      (node (ref "IC20") (pin "30") (pinfunction "XI_30") (pintype "input"))
      (node (ref "R144") (pin "1") (pinfunction "1_1") (pintype "passive"))
      (node (ref "X2") (pin "3") (pinfunction "2_3") (pintype "passive"))
    )
    (net (code "122") (name "Net-(IC20-XO)") (class "Default")
      (node (ref "C86") (pin "1") (pinfunction "1_1") (pintype "passive"))
      (node (ref "IC20") (pin "31") (pinfunction "XO_31") (pintype "output"))
      (node (ref "R144") (pin "2") (pinfunction "2_2") (pintype "passive"))
      (node (ref "X2") (pin "1") (pinfunction "1_1") (pintype "passive"))
    )
    (net (code "123") (name "Net-(IC22--IN)") (class "Default")
      (node (ref "IC22") (pin "1") (pinfunction "OUT_1") (pintype "output"))
      (node (ref "IC22") (pin "4") (pinfunction "-IN_4") (pintype "input"))
      (node (ref "R122") (pin "1") (pinfunction "1_1") (pintype "passive"))
    )
    (net (code "124") (name "Net-(P3ON-PadA)") (class "Default")
      (node (ref "P3ON") (pin "A") (pinfunction "A_A") (pintype "passive"))
      (node (ref "R123") (pin "2") (pinfunction "2_2") (pintype "passive"))
    )
    (net (code "125") (name "Net-(P5ON-PadA)") (class "Default")
      (node (ref "P5ON") (pin "A") (pinfunction "A_A") (pintype "passive"))
      (node (ref "R148") (pin "2") (pinfunction "2_2") (pintype "passive"))
    )
    (net (code "126") (name "Net-(P12ON-PadA)") (class "Default")
      (node (ref "P12ON") (pin "A") (pinfunction "A_A") (pintype "passive"))
      (node (ref "R150") (pin "2") (pinfunction "2_2") (pintype "passive"))
    )
    (net (code "127") (name "Net-(PROC-PadA)") (class "Default")
      (node (ref "PROC") (pin "A") (pinfunction "A_A") (pintype "passive"))
      (node (ref "R163") (pin "1") (pinfunction "1_1") (pintype "passive"))
    )
    (net (code "128") (name "Net-(PWR-PadC)") (class "Default")
      (node (ref "PWR") (pin "C") (pinfunction "C_C") (pintype "passive"))
      (node (ref "R151") (pin "2") (pinfunction "2_2") (pintype "passive"))
    )
    (net (code "129") (name "Net-(R36-Pad1)") (class "Default")
      (node (ref "R36") (pin "1") (pinfunction "1_1") (pintype "passive"))
      (node (ref "R37") (pin "2") (pinfunction "2_2") (pintype "passive"))
    )
    (net (code "130") (name "Net-(R37-Pad1)") (class "Default")
      (node (ref "R37") (pin "1") (pinfunction "1_1") (pintype "passive"))
      (node (ref "R38") (pin "1") (pinfunction "1_1") (pintype "passive"))
    )
    (net (code "131") (name "Net-(R38-Pad2)") (class "Default")
      (node (ref "R38") (pin "2") (pinfunction "2_2") (pintype "passive"))
      (node (ref "R39") (pin "1") (pinfunction "1_1") (pintype "passive"))
    )
    (net (code "132") (name "Net-(R44-Pad2)") (class "Default")
      (node (ref "R44") (pin "2") (pinfunction "2_2") (pintype "passive"))
      (node (ref "R45") (pin "2") (pinfunction "2_2") (pintype "passive"))
    )
    (net (code "133") (name "Net-(R45-Pad1)") (class "Default")
      (node (ref "R45") (pin "1") (pinfunction "1_1") (pintype "passive"))
      (node (ref "R46") (pin "1") (pinfunction "1_1") (pintype "passive"))
    )
    (net (code "134") (name "Net-(R46-Pad2)") (class "Default")
      (node (ref "R46") (pin "2") (pinfunction "2_2") (pintype "passive"))
      (node (ref "R47") (pin "1") (pinfunction "1_1") (pintype "passive"))
    )
    (net (code "135") (name "Net-(R52-Pad2)") (class "Default")
      (node (ref "R52") (pin "2") (pinfunction "2_2") (pintype "passive"))
      (node (ref "R53") (pin "2") (pinfunction "2_2") (pintype "passive"))
    )
    (net (code "136") (name "Net-(R53-Pad1)") (class "Default")
      (node (ref "R53") (pin "1") (pinfunction "1_1") (pintype "passive"))
      (node (ref "R54") (pin "1") (pinfunction "1_1") (pintype "passive"))
    )
    (net (code "137") (name "Net-(R54-Pad2)") (class "Default")
      (node (ref "R54") (pin "2") (pinfunction "2_2") (pintype "passive"))
      (node (ref "R55") (pin "1") (pinfunction "1_1") (pintype "passive"))
    )
    (net (code "138") (name "Net-(R57-Pad1)") (class "Default")
      (node (ref "R57") (pin "1") (pinfunction "1_1") (pintype "passive"))
      (node (ref "R58") (pin "1") (pinfunction "1_1") (pintype "passive"))
      (node (ref "R91") (pin "2") (pinfunction "2_2") (pintype "passive"))
      (node (ref "R92") (pin "2") (pinfunction "2_2") (pintype "passive"))
    )
    (net (code "139") (name "Net-(R63-5)") (class "Default")
      (node (ref "OPT1") (pin "7") (pinfunction "7_7") (pintype "passive"))
      (node (ref "R63") (pin "D2") (pinfunction "5_D2") (pintype "passive"))
    )
    (net (code "140") (name "Net-(R63-6)") (class "Default")
      (node (ref "OPT1") (pin "5") (pinfunction "5_5") (pintype "passive"))
      (node (ref "R63") (pin "C2") (pinfunction "6_C2") (pintype "passive"))
    )
    (net (code "141") (name "Net-(R63-7)") (class "Default")
      (node (ref "OPT1") (pin "3") (pinfunction "3_3") (pintype "passive"))
      (node (ref "R63") (pin "B2") (pinfunction "7_B2") (pintype "passive"))
    )
    (net (code "142") (name "Net-(R63-8)") (class "Default")
      (node (ref "OPT1") (pin "1") (pinfunction "1_1") (pintype "passive"))
      (node (ref "R63") (pin "A2") (pinfunction "8_A2") (pintype "passive"))
    )
    (net (code "143") (name "Net-(R64-5)") (class "Default")
      (node (ref "OPT2") (pin "7") (pinfunction "7_7") (pintype "passive"))
      (node (ref "R64") (pin "D2") (pinfunction "5_D2") (pintype "passive"))
    )
    (net (code "144") (name "Net-(R64-6)") (class "Default")
      (node (ref "OPT2") (pin "5") (pinfunction "5_5") (pintype "passive"))
      (node (ref "R64") (pin "C2") (pinfunction "6_C2") (pintype "passive"))
    )
    (net (code "145") (name "Net-(R64-7)") (class "Default")
      (node (ref "OPT2") (pin "3") (pinfunction "3_3") (pintype "passive"))
      (node (ref "R64") (pin "B2") (pinfunction "7_B2") (pintype "passive"))
    )
    (net (code "146") (name "Net-(R64-8)") (class "Default")
      (node (ref "OPT2") (pin "1") (pinfunction "1_1") (pintype "passive"))
      (node (ref "R64") (pin "A2") (pinfunction "8_A2") (pintype "passive"))
    )
    (net (code "147") (name "Net-(R68-Pad2)") (class "Default")
      (node (ref "R68") (pin "2") (pinfunction "2_2") (pintype "passive"))
      (node (ref "R69") (pin "2") (pinfunction "2_2") (pintype "passive"))
    )
    (net (code "148") (name "Net-(R69-Pad1)") (class "Default")
      (node (ref "R69") (pin "1") (pinfunction "1_1") (pintype "passive"))
      (node (ref "R70") (pin "1") (pinfunction "1_1") (pintype "passive"))
    )
    (net (code "149") (name "Net-(R70-Pad2)") (class "Default")
      (node (ref "R70") (pin "2") (pinfunction "2_2") (pintype "passive"))
      (node (ref "R71") (pin "1") (pinfunction "1_1") (pintype "passive"))
    )
    (net (code "150") (name "Net-(R76-Pad2)") (class "Default")
      (node (ref "R76") (pin "2") (pinfunction "2_2") (pintype "passive"))
      (node (ref "R77") (pin "2") (pinfunction "2_2") (pintype "passive"))
    )
    (net (code "151") (name "Net-(R77-Pad1)") (class "Default")
      (node (ref "R77") (pin "1") (pinfunction "1_1") (pintype "passive"))
      (node (ref "R78") (pin "1") (pinfunction "1_1") (pintype "passive"))
    )
    (net (code "152") (name "Net-(R78-Pad2)") (class "Default")
      (node (ref "R78") (pin "2") (pinfunction "2_2") (pintype "passive"))
      (node (ref "R79") (pin "1") (pinfunction "1_1") (pintype "passive"))
    )
    (net (code "153") (name "Net-(R84-Pad2)") (class "Default")
      (node (ref "R84") (pin "2") (pinfunction "2_2") (pintype "passive"))
      (node (ref "R85") (pin "2") (pinfunction "2_2") (pintype "passive"))
    )
    (net (code "154") (name "Net-(R85-Pad1)") (class "Default")
      (node (ref "R85") (pin "1") (pinfunction "1_1") (pintype "passive"))
      (node (ref "R86") (pin "1") (pinfunction "1_1") (pintype "passive"))
    )
    (net (code "155") (name "Net-(R86-Pad2)") (class "Default")
      (node (ref "R86") (pin "2") (pinfunction "2_2") (pintype "passive"))
      (node (ref "R87") (pin "1") (pinfunction "1_1") (pintype "passive"))
    )
    (net (code "156") (name "Net-(R100-Pad2)") (class "Default")
      (node (ref "R100") (pin "2") (pinfunction "2_2") (pintype "passive"))
      (node (ref "R101") (pin "2") (pinfunction "2_2") (pintype "passive"))
    )
    (net (code "157") (name "Net-(R101-Pad1)") (class "Default")
      (node (ref "R101") (pin "1") (pinfunction "1_1") (pintype "passive"))
      (node (ref "R102") (pin "1") (pinfunction "1_1") (pintype "passive"))
    )
    (net (code "158") (name "Net-(R102-Pad2)") (class "Default")
      (node (ref "R102") (pin "2") (pinfunction "2_2") (pintype "passive"))
      (node (ref "R103") (pin "1") (pinfunction "1_1") (pintype "passive"))
    )
    (net (code "159") (name "Net-(R116-Pad2)") (class "Default")
      (node (ref "R116") (pin "2") (pinfunction "2_2") (pintype "passive"))
      (node (ref "R117") (pin "2") (pinfunction "2_2") (pintype "passive"))
    )
    (net (code "160") (name "Net-(R117-Pad1)") (class "Default")
      (node (ref "R117") (pin "1") (pinfunction "1_1") (pintype "passive"))
      (node (ref "R118") (pin "1") (pinfunction "1_1") (pintype "passive"))
    )
    (net (code "161") (name "Net-(R118-Pad2)") (class "Default")
      (node (ref "R118") (pin "2") (pinfunction "2_2") (pintype "passive"))
      (node (ref "R119") (pin "1") (pinfunction "1_1") (pintype "passive"))
    )
    (net (code "162") (name "Net-(T1-D)") (class "Default")
      (node (ref "FAN") (pin "1") (pinfunction "1_1") (pintype "passive"))
      (node (ref "T1") (pin "3") (pinfunction "D_3") (pintype "passive"))
    )
    (net (code "163") (name "Net-(X1-2)") (class "Default")
      (node (ref "C59") (pin "1") (pinfunction "1_1") (pintype "passive"))
      (node (ref "R16") (pin "1") (pinfunction "1_1") (pintype "passive"))
      (node (ref "X1") (pin "3") (pinfunction "2_3") (pintype "passive"))
    )
    (net (code "164") (name "OUT_1") (class "Default")
      (node (ref "K1") (pin "4") (pinfunction "4_4") (pintype "passive"))
      (node (ref "K1") (pin "5") (pinfunction "5_5") (pintype "passive"))
      (node (ref "L_OUT1") (pin "B2,8") (pinfunction "MOUNT_B2,8") (pintype "passive"))
      (node (ref "R36") (pin "2") (pinfunction "2_2") (pintype "passive"))
    )
    (net (code "165") (name "OUT_2") (class "Default")
      (node (ref "K2") (pin "4") (pinfunction "4_4") (pintype "passive"))
      (node (ref "K2") (pin "5") (pinfunction "5_5") (pintype "passive"))
      (node (ref "L_OUT2") (pin "B2,8") (pinfunction "MOUNT_B2,8") (pintype "passive"))
      (node (ref "R52") (pin "1") (pinfunction "1_1") (pintype "passive"))
    )
    (net (code "166") (name "OUT_3") (class "Default")
      (node (ref "K3") (pin "4") (pinfunction "4_4") (pintype "passive"))
      (node (ref "K3") (pin "5") (pinfunction "5_5") (pintype "passive"))
      (node (ref "L_OUT3") (pin "B2,8") (pinfunction "MOUNT_B2,8") (pintype "passive"))
      (node (ref "R68") (pin "1") (pinfunction "1_1") (pintype "passive"))
    )
    (net (code "167") (name "OUT_4") (class "Default")
      (node (ref "K4") (pin "4") (pinfunction "4_4") (pintype "passive"))
      (node (ref "K4") (pin "5") (pinfunction "5_5") (pintype "passive"))
      (node (ref "L_OUT4") (pin "B2,8") (pinfunction "MOUNT_B2,8") (pintype "passive"))
      (node (ref "R84") (pin "1") (pinfunction "1_1") (pintype "passive"))
    )
    (net (code "168") (name "OUT_5") (class "Default")
      (node (ref "K5") (pin "4") (pinfunction "4_4") (pintype "passive"))
      (node (ref "K5") (pin "5") (pinfunction "5_5") (pintype "passive"))
      (node (ref "L_OUT5") (pin "B2,8") (pinfunction "MOUNT_B2,8") (pintype "passive"))
      (node (ref "R44") (pin "1") (pinfunction "1_1") (pintype "passive"))
    )
    (net (code "169") (name "OUT_6") (class "Default")
      (node (ref "K6") (pin "4") (pinfunction "4_4") (pintype "passive"))
      (node (ref "K6") (pin "5") (pinfunction "5_5") (pintype "passive"))
      (node (ref "L_OUT6") (pin "B2,8") (pinfunction "MOUNT_B2,8") (pintype "passive"))
      (node (ref "R76") (pin "1") (pinfunction "1_1") (pintype "passive"))
    )
    (net (code "170") (name "OUT_7") (class "Default")
      (node (ref "K7") (pin "4") (pinfunction "4_4") (pintype "passive"))
      (node (ref "K7") (pin "5") (pinfunction "5_5") (pintype "passive"))
      (node (ref "L_OUT7") (pin "B2,8") (pinfunction "MOUNT_B2,8") (pintype "passive"))
      (node (ref "R100") (pin "1") (pinfunction "1_1") (pintype "passive"))
    )
    (net (code "171") (name "OUT_8") (class "Default")
      (node (ref "K8") (pin "4") (pinfunction "4_4") (pintype "passive"))
      (node (ref "K8") (pin "5") (pinfunction "5_5") (pintype "passive"))
      (node (ref "L_OUT8") (pin "B2,8") (pinfunction "MOUNT_B2,8") (pintype "passive"))
      (node (ref "R116") (pin "1") (pinfunction "1_1") (pintype "passive"))
    )
    (net (code "172") (name "QSPI_SCLK") (class "Default")
      (node (ref "IC15") (pin "52") (pinfunction "QSPI_SCLK_52") (pintype "bidirectional"))
      (node (ref "IC18") (pin "6") (pinfunction "CLK_6") (pintype "bidirectional"))
    )
    (net (code "173") (name "QSPI_SD0") (class "Default")
      (node (ref "IC15") (pin "53") (pinfunction "QSPI_SD0_53") (pintype "bidirectional"))
      (node (ref "IC18") (pin "5") (pinfunction "DI/IO0_5") (pintype "bidirectional"))
    )
    (net (code "174") (name "QSPI_SD1") (class "Default")
      (node (ref "IC15") (pin "55") (pinfunction "QSPI_SD1_55") (pintype "bidirectional"))
      (node (ref "IC18") (pin "2") (pinfunction "DO/IO1_2") (pintype "bidirectional"))
    )
    (net (code "175") (name "QSPI_SD2") (class "Default")
      (node (ref "IC15") (pin "54") (pinfunction "QSPI_SD2_54") (pintype "bidirectional"))
      (node (ref "IC18") (pin "3") (pinfunction "~{WP}/IO2_3") (pintype "bidirectional"))
    )
    (net (code "176") (name "QSPI_SD3") (class "Default")
      (node (ref "IC15") (pin "51") (pinfunction "QSPI_SD3_51") (pintype "bidirectional"))
      (node (ref "IC18") (pin "7") (pinfunction "~{HOLD}/IO3_7") (pintype "bidirectional"))
    )
    (net (code "177") (name "RCT") (class "Default")
      (node (ref "C79") (pin "1") (pinfunction "1_1") (pintype "passive"))
      (node (ref "ETH1") (pin "5") (pinfunction "P5/RCT_5") (pintype "passive"))
      (node (ref "R137") (pin "1") (pinfunction "1_1") (pintype "passive"))
      (node (ref "R138") (pin "1") (pinfunction "1_1") (pintype "passive"))
    )
    (net (code "178") (name "RDC_RD_N") (class "Default")
      (node (ref "C81") (pin "1") (pinfunction "1_1") (pintype "passive"))
      (node (ref "R136") (pin "2") (pinfunction "2_2") (pintype "passive"))
      (node (ref "R137") (pin "2") (pinfunction "2_2") (pintype "passive"))
    )
    (net (code "179") (name "RDC_RD_P") (class "Default")
      (node (ref "C82") (pin "1") (pinfunction "1_1") (pintype "passive"))
      (node (ref "R135") (pin "2") (pinfunction "2_2") (pintype "passive"))
      (node (ref "R138") (pin "2") (pinfunction "2_2") (pintype "passive"))
    )
    (net (code "180") (name "RD_N") (class "Default")
      (node (ref "C81") (pin "2") (pinfunction "2_2") (pintype "passive"))
      (node (ref "ETH1") (pin "6") (pinfunction "RD-_6") (pintype "passive"))
    )
    (net (code "181") (name "RD_P") (class "Default")
      (node (ref "C82") (pin "2") (pinfunction "2_2") (pintype "passive"))
      (node (ref "ETH1") (pin "4") (pinfunction "RD+_4") (pintype "passive"))
    )
    (net (code "182") (name "RELAY_1") (class "Default")
      (node (ref "D1") (pin "A") (pinfunction "A_A") (pintype "passive"))
      (node (ref "K1") (pin "1") (pinfunction "1_1") (pintype "passive"))
      (node (ref "R24") (pin "2") (pinfunction "2_2") (pintype "passive"))
    )
    (net (code "183") (name "RELAY_2") (class "Default")
      (node (ref "D2") (pin "A") (pinfunction "A_A") (pintype "passive"))
      (node (ref "K2") (pin "1") (pinfunction "1_1") (pintype "passive"))
      (node (ref "R23") (pin "2") (pinfunction "2_2") (pintype "passive"))
    )
    (net (code "184") (name "RELAY_3") (class "Default")
      (node (ref "D3") (pin "A") (pinfunction "A_A") (pintype "passive"))
      (node (ref "K3") (pin "1") (pinfunction "1_1") (pintype "passive"))
      (node (ref "R22") (pin "2") (pinfunction "2_2") (pintype "passive"))
    )
    (net (code "185") (name "RELAY_4") (class "Default")
      (node (ref "D4") (pin "A") (pinfunction "A_A") (pintype "passive"))
      (node (ref "K4") (pin "1") (pinfunction "1_1") (pintype "passive"))
      (node (ref "R21") (pin "2") (pinfunction "2_2") (pintype "passive"))
    )
    (net (code "186") (name "RELAY_5") (class "Default")
      (node (ref "D5") (pin "A") (pinfunction "A_A") (pintype "passive"))
      (node (ref "K5") (pin "1") (pinfunction "1_1") (pintype "passive"))
      (node (ref "R20") (pin "2") (pinfunction "2_2") (pintype "passive"))
    )
    (net (code "187") (name "RELAY_6") (class "Default")
      (node (ref "D6") (pin "A") (pinfunction "A_A") (pintype "passive"))
      (node (ref "K6") (pin "1") (pinfunction "1_1") (pintype "passive"))
      (node (ref "R19") (pin "2") (pinfunction "2_2") (pintype "passive"))
    )
    (net (code "188") (name "RELAY_7") (class "Default")
      (node (ref "D7") (pin "A") (pinfunction "A_A") (pintype "passive"))
      (node (ref "K7") (pin "1") (pinfunction "1_1") (pintype "passive"))
      (node (ref "R18") (pin "2") (pinfunction "2_2") (pintype "passive"))
    )
    (net (code "189") (name "RELAY_8") (class "Default")
      (node (ref "D8") (pin "A") (pinfunction "A_A") (pintype "passive"))
      (node (ref "K8") (pin "1") (pinfunction "1_1") (pintype "passive"))
      (node (ref "R17") (pin "2") (pinfunction "2_2") (pintype "passive"))
    )
    (net (code "190") (name "REL_0") (class "Default")
      (node (ref "IC3") (pin "8") (pinfunction "8B_8") (pintype "bidirectional"))
      (node (ref "IC4") (pin "17") (pinfunction "IO1.0_17") (pintype "bidirectional"))
      (node (ref "REL0") (pin "TP") (pinfunction "P$1_TP") (pintype "bidirectional"))
    )
    (net (code "191") (name "REL_1") (class "Default")
      (node (ref "IC3") (pin "7") (pinfunction "7B_7") (pintype "bidirectional"))
      (node (ref "IC4") (pin "18") (pinfunction "IO1.1_18") (pintype "bidirectional"))
      (node (ref "REL1") (pin "TP") (pinfunction "P$1_TP") (pintype "bidirectional"))
    )
    (net (code "192") (name "REL_2") (class "Default")
      (node (ref "IC3") (pin "6") (pinfunction "6B_6") (pintype "bidirectional"))
      (node (ref "IC4") (pin "19") (pinfunction "IO1.2_19") (pintype "bidirectional"))
      (node (ref "REL2") (pin "TP") (pinfunction "P$1_TP") (pintype "bidirectional"))
    )
    (net (code "193") (name "REL_3") (class "Default")
      (node (ref "IC3") (pin "5") (pinfunction "5B_5") (pintype "bidirectional"))
      (node (ref "IC4") (pin "20") (pinfunction "IO1.3_20") (pintype "bidirectional"))
      (node (ref "REL3") (pin "TP") (pinfunction "P$1_TP") (pintype "bidirectional"))
    )
    (net (code "194") (name "REL_4") (class "Default")
      (node (ref "IC3") (pin "4") (pinfunction "4B_4") (pintype "bidirectional"))
      (node (ref "IC4") (pin "21") (pinfunction "IO1.4_21") (pintype "bidirectional"))
      (node (ref "REL4") (pin "TP") (pinfunction "P$1_TP") (pintype "bidirectional"))
    )
    (net (code "195") (name "REL_5") (class "Default")
      (node (ref "IC3") (pin "3") (pinfunction "3B_3") (pintype "bidirectional"))
      (node (ref "IC4") (pin "22") (pinfunction "IO1.5_22") (pintype "bidirectional"))
      (node (ref "REL5") (pin "TP") (pinfunction "P$1_TP") (pintype "bidirectional"))
    )
    (net (code "196") (name "REL_6") (class "Default")
      (node (ref "IC3") (pin "2") (pinfunction "2B_2") (pintype "bidirectional"))
      (node (ref "IC4") (pin "23") (pinfunction "IO1.6_23") (pintype "bidirectional"))
      (node (ref "REL6") (pin "TP") (pinfunction "P$1_TP") (pintype "bidirectional"))
    )
    (net (code "197") (name "REL_7") (class "Default")
      (node (ref "IC3") (pin "1") (pinfunction "1B_1") (pintype "bidirectional"))
      (node (ref "IC4") (pin "24") (pinfunction "IO1.7_24") (pintype "bidirectional"))
      (node (ref "REL7") (pin "TP") (pinfunction "P$1_TP") (pintype "bidirectional"))
    )
    (net (code "198") (name "RP_XI") (class "Default")
      (node (ref "C58") (pin "1") (pinfunction "1_1") (pintype "passive"))
      (node (ref "IC15") (pin "20") (pinfunction "XIN_20") (pintype "bidirectional"))
      (node (ref "X1") (pin "1") (pinfunction "1_1") (pintype "passive"))
    )
    (net (code "199") (name "RP_XO") (class "Default")
      (node (ref "IC15") (pin "21") (pinfunction "XOUT_21") (pintype "bidirectional"))
      (node (ref "R16") (pin "2") (pinfunction "2_2") (pintype "passive"))
    )
    (net (code "200") (name "RUN") (class "Default")
      (node (ref "GDGC") (pin "2") (pinfunction "P$2_2") (pintype "bidirectional"))
      (node (ref "IC15") (pin "26") (pinfunction "RUN_26") (pintype "bidirectional"))
      (node (ref "R132") (pin "2") (pinfunction "2_2") (pintype "passive"))
      (node (ref "RESET") (pin "2") (pinfunction "P$2_2") (pintype "bidirectional"))
    )
    (net (code "201") (name "RX_RD_N") (class "Default")
      (node (ref "IC20") (pin "5") (pinfunction "RXN_5") (pintype "input"))
      (node (ref "R136") (pin "1") (pinfunction "1_1") (pintype "passive"))
    )
    (net (code "202") (name "RX_RD_P") (class "Default")
      (node (ref "IC20") (pin "6") (pinfunction "RXP_6") (pintype "input"))
      (node (ref "R135") (pin "1") (pinfunction "1_1") (pintype "passive"))
    )
    (net (code "203") (name "SH") (class "Default")
      (node (ref "C78") (pin "1") (pinfunction "1_1") (pintype "passive"))
      (node (ref "C83") (pin "2") (pinfunction "2_2") (pintype "passive"))
      (node (ref "ETH1") (pin "13") (pinfunction "SHIELD_13") (pintype "passive"))
      (node (ref "ETH1") (pin "14") (pinfunction "SHIELD_14") (pintype "passive"))
      (node (ref "R110") (pin "2") (pinfunction "2_2") (pintype "passive"))
      (node (ref "R131") (pin "1") (pinfunction "1_1") (pintype "passive"))
      (node (ref "USB1") (pin "SHLD1") (pinfunction "SHILED_SHLD1") (pintype "power_in"))
      (node (ref "USB1") (pin "SHLD2") (pinfunction "SHILED_SHLD2") (pintype "power_in"))
      (node (ref "USB1") (pin "SHLD3") (pinfunction "SHILED_SHLD3") (pintype "power_in"))
      (node (ref "USB1") (pin "SHLD4") (pinfunction "SHILED_SHLD4") (pintype "power_in"))
    )
    (net (code "204") (name "SPI1_CS") (class "Default")
      (node (ref "CS0") (pin "TP") (pinfunction "P$1_TP") (pintype "bidirectional"))
      (node (ref "DSP") (pin "19") (pinfunction "19_19") (pintype "bidirectional"))
      (node (ref "IC15") (pin "12") (pinfunction "GPIO9_12") (pintype "bidirectional"))
      (node (ref "R149") (pin "C2") (pinfunction "6_C2") (pintype "passive"))
    )
    (net (code "205") (name "SPI1_MISO") (class "Default")
      (node (ref "DSP") (pin "15") (pinfunction "15_15") (pintype "bidirectional"))
      (node (ref "IC15") (pin "11") (pinfunction "GPIO8_11") (pintype "bidirectional"))
      (node (ref "MISO0") (pin "TP") (pinfunction "P$1_TP") (pintype "bidirectional"))
      (node (ref "R149") (pin "B2") (pinfunction "7_B2") (pintype "passive"))
    )
    (net (code "206") (name "SPI1_MOSI") (class "Default")
      (node (ref "DSP") (pin "16") (pinfunction "16_16") (pintype "bidirectional"))
      (node (ref "IC15") (pin "14") (pinfunction "GPIO11_14") (pintype "bidirectional"))
      (node (ref "MOSI0") (pin "TP") (pinfunction "P$1_TP") (pintype "bidirectional"))
    )
    (net (code "207") (name "SPI1_SCLK") (class "Default")
      (node (ref "DSP") (pin "17") (pinfunction "17_17") (pintype "bidirectional"))
      (node (ref "IC15") (pin "13") (pinfunction "GPIO10_13") (pintype "bidirectional"))
      (node (ref "SCLK0") (pin "TP") (pinfunction "P$1_TP") (pintype "bidirectional"))
    )
    (net (code "208") (name "SRC1") (class "Default")
      (node (ref "C21") (pin "1") (pinfunction "1_1") (pintype "passive"))
      (node (ref "C22") (pin "1") (pinfunction "1_1") (pintype "passive"))
      (node (ref "C5") (pin "1") (pinfunction "1_1") (pintype "passive"))
      (node (ref "D11") (pin "C") (pinfunction "C_C") (pintype "passive"))
      (node (ref "IC13") (pin "3") (pinfunction "SRC2_3") (pintype "output"))
      (node (ref "IC13") (pin "4") (pinfunction "SRC_4") (pintype "output"))
      (node (ref "L3") (pin "1") (pinfunction "1_1") (pintype "passive"))
      (node (ref "R60") (pin "2") (pinfunction "2_2") (pintype "passive"))
    )
    (net (code "209") (name "SRC2") (class "Default")
      (node (ref "C46") (pin "1") (pinfunction "1_1") (pintype "passive"))
      (node (ref "C51") (pin "1") (pinfunction "1_1") (pintype "passive"))
      (node (ref "C52") (pin "1") (pinfunction "1_1") (pintype "passive"))
      (node (ref "D14") (pin "C") (pinfunction "C_C") (pintype "passive"))
      (node (ref "IC5") (pin "3") (pinfunction "SRC2_3") (pintype "output"))
      (node (ref "IC5") (pin "4") (pinfunction "SRC_4") (pintype "output"))
      (node (ref "L5") (pin "1") (pinfunction "1_1") (pintype "passive"))
      (node (ref "R107") (pin "2") (pinfunction "2_2") (pintype "passive"))
    )
    (net (code "210") (name "SWCLK") (class "Default")
      (node (ref "GDGC") (pin "1") (pinfunction "P$1_1") (pintype "bidirectional"))
      (node (ref "IC15") (pin "24") (pinfunction "SWCLK_24") (pintype "bidirectional"))
    )
    (net (code "211") (name "SWDIO") (class "Default")
      (node (ref "GDGC") (pin "3") (pinfunction "P$3_3") (pintype "bidirectional"))
      (node (ref "IC15") (pin "25") (pinfunction "SWDIO_25") (pintype "bidirectional"))
    )
    (net (code "212") (name "TCT") (class "Default")
      (node (ref "C80") (pin "1") (pinfunction "1_1") (pintype "passive"))
      (node (ref "ETH1") (pin "2") (pinfunction "P4/TCT_2") (pintype "passive"))
      (node (ref "R146") (pin "1") (pinfunction "1_1") (pintype "passive"))
    )
    (net (code "213") (name "TD_N") (class "Default")
      (node (ref "ETH1") (pin "3") (pinfunction "TD-_3") (pintype "passive"))
      (node (ref "R134") (pin "2") (pinfunction "2_2") (pintype "passive"))
      (node (ref "R140") (pin "1") (pinfunction "1_1") (pintype "passive"))
    )
    (net (code "214") (name "TD_P") (class "Default")
      (node (ref "ETH1") (pin "1") (pinfunction "TD+_1") (pintype "passive"))
      (node (ref "R133") (pin "2") (pinfunction "2_2") (pintype "passive"))
      (node (ref "R139") (pin "1") (pinfunction "1_1") (pintype "passive"))
    )
    (net (code "215") (name "TX_CH1") (class "Default")
      (node (ref "IC6") (pin "6") (pinfunction "TX_6") (pintype "bidirectional"))
      (node (ref "R155") (pin "1") (pinfunction "1_1") (pintype "passive"))
    )
    (net (code "216") (name "TX_CH2") (class "Default")
      (node (ref "IC8") (pin "6") (pinfunction "TX_6") (pintype "bidirectional"))
      (node (ref "R154") (pin "1") (pinfunction "1_1") (pintype "passive"))
    )
    (net (code "217") (name "TX_CH3") (class "Default")
      (node (ref "IC10") (pin "6") (pinfunction "TX_6") (pintype "bidirectional"))
      (node (ref "R153") (pin "1") (pinfunction "1_1") (pintype "passive"))
    )
    (net (code "218") (name "TX_CH4") (class "Default")
      (node (ref "IC12") (pin "6") (pinfunction "TX_6") (pintype "bidirectional"))
      (node (ref "R59") (pin "1") (pinfunction "1_1") (pintype "passive"))
    )
    (net (code "219") (name "TX_CH5") (class "Default")
      (node (ref "IC7") (pin "6") (pinfunction "TX_6") (pintype "bidirectional"))
      (node (ref "R159") (pin "1") (pinfunction "1_1") (pintype "passive"))
    )
    (net (code "220") (name "TX_CH6") (class "Default")
      (node (ref "IC11") (pin "6") (pinfunction "TX_6") (pintype "bidirectional"))
      (node (ref "R158") (pin "1") (pinfunction "1_1") (pintype "passive"))
    )
    (net (code "221") (name "TX_CH7") (class "Default")
      (node (ref "IC14") (pin "6") (pinfunction "TX_6") (pintype "bidirectional"))
      (node (ref "R157") (pin "1") (pinfunction "1_1") (pintype "passive"))
    )
    (net (code "222") (name "TX_CH8") (class "Default")
      (node (ref "IC16") (pin "6") (pinfunction "TX_6") (pintype "bidirectional"))
      (node (ref "R156") (pin "1") (pinfunction "1_1") (pintype "passive"))
    )
    (net (code "223") (name "TX_MUX1") (class "Default")
      (node (ref "IC9") (pin "4") (pinfunction "D0_4") (pintype "bidirectional"))
      (node (ref "OPT1") (pin "10") (pinfunction "10_10") (pintype "passive"))
      (node (ref "R89") (pin "D1") (pinfunction "4_D1") (pintype "passive"))
    )
    (net (code "224") (name "TX_MUX2") (class "Default")
      (node (ref "IC9") (pin "3") (pinfunction "D1_3") (pintype "bidirectional"))
      (node (ref "OPT1") (pin "12") (pinfunction "12_12") (pintype "passive"))
      (node (ref "R89") (pin "C1") (pinfunction "3_C1") (pintype "passive"))
    )
    (net (code "225") (name "TX_MUX3") (class "Default")
      (node (ref "IC9") (pin "2") (pinfunction "D2_2") (pintype "bidirectional"))
      (node (ref "OPT1") (pin "14") (pinfunction "14_14") (pintype "passive"))
      (node (ref "R89") (pin "B1") (pinfunction "2_B1") (pintype "passive"))
    )
    (net (code "226") (name "TX_MUX4") (class "Default")
      (node (ref "IC9") (pin "1") (pinfunction "D3_1") (pintype "bidirectional"))
      (node (ref "OPT1") (pin "16") (pinfunction "16_16") (pintype "passive"))
      (node (ref "R89") (pin "A1") (pinfunction "1_A1") (pintype "passive"))
    )
    (net (code "227") (name "TX_MUX5") (class "Default")
      (node (ref "IC9") (pin "15") (pinfunction "D4_15") (pintype "bidirectional"))
      (node (ref "OPT2") (pin "16") (pinfunction "16_16") (pintype "passive"))
      (node (ref "R90") (pin "A1") (pinfunction "1_A1") (pintype "passive"))
    )
    (net (code "228") (name "TX_MUX6") (class "Default")
      (node (ref "IC9") (pin "14") (pinfunction "D5_14") (pintype "bidirectional"))
      (node (ref "OPT2") (pin "14") (pinfunction "14_14") (pintype "passive"))
      (node (ref "R90") (pin "B1") (pinfunction "2_B1") (pintype "passive"))
    )
    (net (code "229") (name "TX_MUX7") (class "Default")
      (node (ref "IC9") (pin "13") (pinfunction "D6_13") (pintype "bidirectional"))
      (node (ref "OPT2") (pin "12") (pinfunction "12_12") (pintype "passive"))
      (node (ref "R90") (pin "C1") (pinfunction "3_C1") (pintype "passive"))
    )
    (net (code "230") (name "TX_MUX8") (class "Default")
      (node (ref "IC9") (pin "12") (pinfunction "D7_12") (pintype "bidirectional"))
      (node (ref "OPT2") (pin "10") (pinfunction "10_10") (pintype "passive"))
      (node (ref "R90") (pin "D1") (pinfunction "4_D1") (pintype "passive"))
    )
    (net (code "231") (name "TX_OUT") (class "Default")
      (node (ref "IC9") (pin "5") (pinfunction "Y_5") (pintype "bidirectional"))
      (node (ref "R91") (pin "1") (pinfunction "1_1") (pintype "passive"))
    )
    (net (code "232") (name "TX_TD_N") (class "Default")
      (node (ref "IC20") (pin "1") (pinfunction "TXN_1") (pintype "output"))
      (node (ref "R134") (pin "1") (pinfunction "1_1") (pintype "passive"))
    )
    (net (code "233") (name "TX_TD_P") (class "Default")
      (node (ref "IC20") (pin "2") (pinfunction "TXP_2") (pintype "output"))
      (node (ref "R133") (pin "1") (pinfunction "1_1") (pintype "passive"))
    )
    (net (code "234") (name "UART0_RX") (class "Default")
      (node (ref "IC15") (pin "2") (pinfunction "GPIO0_2") (pintype "bidirectional"))
      (node (ref "R58") (pin "2") (pinfunction "2_2") (pintype "passive"))
      (node (ref "RGTG") (pin "1") (pinfunction "P$1_1") (pintype "bidirectional"))
      (node (ref "RX0") (pin "TP") (pinfunction "P$1_TP") (pintype "bidirectional"))
    )
    (net (code "235") (name "UART0_TX") (class "Default")
      (node (ref "IC15") (pin "3") (pinfunction "GPIO1_3") (pintype "bidirectional"))
      (node (ref "R57") (pin "2") (pinfunction "2_2") (pintype "passive"))
      (node (ref "RGTG") (pin "3") (pinfunction "P$3_3") (pintype "bidirectional"))
      (node (ref "RX1") (pin "TP") (pinfunction "P$1_TP") (pintype "bidirectional"))
    )
    (net (code "236") (name "USB2_DP_N") (class "Default")
      (node (ref "ESD1") (pin "3") (pinfunction "C2_3") (pintype "bidirectional"))
      (node (ref "R15") (pin "1") (pinfunction "1_1") (pintype "passive"))
      (node (ref "USB1") (pin "A7") (pinfunction "D-_A7") (pintype "bidirectional"))
      (node (ref "USB1") (pin "B7") (pinfunction "D-_B7") (pintype "bidirectional"))
    )
    (net (code "237") (name "USB2_DP_P") (class "Default")
      (node (ref "ESD1") (pin "2") (pinfunction "C1_2") (pintype "bidirectional"))
      (node (ref "R160") (pin "1") (pinfunction "1_1") (pintype "passive"))
      (node (ref "USB1") (pin "A6") (pinfunction "D+_A6") (pintype "bidirectional"))
      (node (ref "USB1") (pin "B6") (pinfunction "D+_B6") (pintype "bidirectional"))
    )
    (net (code "238") (name "USB_BOOT") (class "Default")
      (node (ref "BOOT") (pin "1") (pinfunction "P$1_1") (pintype "bidirectional"))
      (node (ref "R112") (pin "1") (pinfunction "1_1") (pintype "passive"))
    )
    (net (code "239") (name "VBUS") (class "Default")
      (node (ref "C65") (pin "1") (pinfunction "1_1") (pintype "passive"))
      (node (ref "C66") (pin "1") (pinfunction "1_1") (pintype "passive"))
      (node (ref "C97") (pin "1") (pinfunction "1_1") (pintype "passive"))
      (node (ref "C98") (pin "1") (pinfunction "1_1") (pintype "passive"))
      (node (ref "D15") (pin "C") (pinfunction "C_C") (pintype "passive"))
      (node (ref "ESD1") (pin "4") (pinfunction "C3_4") (pintype "bidirectional"))
      (node (ref "IC21") (pin "1") (pinfunction "VIN_1") (pintype "bidirectional"))
      (node (ref "IC21") (pin "3") (pinfunction "EN_3") (pintype "bidirectional"))
      (node (ref "R121") (pin "1") (pinfunction "1_1") (pintype "passive"))
      (node (ref "R126") (pin "1") (pinfunction "1_1") (pintype "passive"))
      (node (ref "USB1") (pin "VBUS1") (pinfunction "VBUS_VBUS1") (pintype "power_in"))
      (node (ref "USB1") (pin "VBUS2") (pinfunction "VBUS_VBUS2") (pintype "power_in"))
      (node (ref "VBUS") (pin "TP") (pinfunction "P$1_TP") (pintype "bidirectional"))
    )
    (net (code "240") (name "VNI1") (class "Default")
      (node (ref "C21") (pin "2") (pinfunction "2_2") (pintype "passive"))
      (node (ref "IC13") (pin "1") (pinfunction "VCC_1") (pintype "output"))
      (node (ref "VNI1") (pin "TP") (pinfunction "P$1_TP") (pintype "bidirectional"))
    )
    (net (code "241") (name "VNI2") (class "Default")
      (node (ref "C46") (pin "2") (pinfunction "2_2") (pintype "passive"))
      (node (ref "IC5") (pin "1") (pinfunction "VCC_1") (pintype "output"))
      (node (ref "VNI2") (pin "TP") (pinfunction "P$1_TP") (pintype "bidirectional"))
    )
    (net (code "242") (name "W5500_MISO") (class "Default")
      (node (ref "IC15") (pin "27") (pinfunction "GPIO16_27") (pintype "bidirectional"))
      (node (ref "IC20") (pin "34") (pinfunction "MISO_34") (pintype "output"))
      (node (ref "MISO1") (pin "TP") (pinfunction "P$1_TP") (pintype "bidirectional"))
    )
    (net (code "243") (name "W5500_MOSI") (class "Default")
      (node (ref "IC15") (pin "30") (pinfunction "GPIO19_30") (pintype "bidirectional"))
      (node (ref "IC20") (pin "35") (pinfunction "MOSI_35") (pintype "input"))
      (node (ref "MOSI1") (pin "TP") (pinfunction "P$1_TP") (pintype "bidirectional"))
    )
    (net (code "244") (name "W5500_SCK") (class "Default")
      (node (ref "IC15") (pin "29") (pinfunction "GPIO18_29") (pintype "bidirectional"))
      (node (ref "IC20") (pin "33") (pinfunction "SCLK_33") (pintype "input"))
      (node (ref "SCLK1") (pin "TP") (pinfunction "P$1_TP") (pintype "bidirectional"))
    )
    (net (code "245") (name "unconnected-(IC4-INTA-Pad16)") (class "Default")
      (node (ref "IC4") (pin "16") (pinfunction "INTA_16") (pintype "bidirectional"))
    )
    (net (code "246") (name "unconnected-(IC4-INTB-Pad15)") (class "Default")
      (node (ref "IC4") (pin "15") (pinfunction "INTB_15") (pintype "bidirectional"))
    )
    (net (code "247") (name "unconnected-(IC4-IO2.4-Pad1)") (class "Default")
      (node (ref "IC4") (pin "1") (pinfunction "IO2.4_1") (pintype "bidirectional"))
    )
    (net (code "248") (name "unconnected-(IC4-IO2.5-Pad2)") (class "Default")
      (node (ref "IC4") (pin "2") (pinfunction "IO2.5_2") (pintype "bidirectional"))
    )
    (net (code "249") (name "unconnected-(IC4-IO2.6-Pad3)") (class "Default")
      (node (ref "IC4") (pin "3") (pinfunction "IO2.6_3") (pintype "bidirectional"))
    )
    (net (code "250") (name "unconnected-(IC4-IO2.7-Pad4)") (class "Default")
      (node (ref "IC4") (pin "4") (pinfunction "IO2.7_4") (pintype "bidirectional"))
    )
    (net (code "251") (name "unconnected-(IC6-PF-Pad7)") (class "Default")
      (node (ref "IC6") (pin "7") (pinfunction "PF_7") (pintype "bidirectional"))
    )
    (net (code "252") (name "unconnected-(IC6-RX-Pad8)") (class "Default")
      (node (ref "IC6") (pin "8") (pinfunction "RX_8") (pintype "bidirectional"))
    )
    (net (code "253") (name "unconnected-(IC7-PF-Pad7)") (class "Default")
      (node (ref "IC7") (pin "7") (pinfunction "PF_7") (pintype "bidirectional"))
    )
    (net (code "254") (name "unconnected-(IC7-RX-Pad8)") (class "Default")
      (node (ref "IC7") (pin "8") (pinfunction "RX_8") (pintype "bidirectional"))
    )
    (net (code "255") (name "unconnected-(IC8-PF-Pad7)") (class "Default")
      (node (ref "IC8") (pin "7") (pinfunction "PF_7") (pintype "bidirectional"))
    )
    (net (code "256") (name "unconnected-(IC8-RX-Pad8)") (class "Default")
      (node (ref "IC8") (pin "8") (pinfunction "RX_8") (pintype "bidirectional"))
    )
    (net (code "257") (name "unconnected-(IC10-PF-Pad7)") (class "Default")
      (node (ref "IC10") (pin "7") (pinfunction "PF_7") (pintype "bidirectional"))
    )
    (net (code "258") (name "unconnected-(IC10-RX-Pad8)") (class "Default")
      (node (ref "IC10") (pin "8") (pinfunction "RX_8") (pintype "bidirectional"))
    )
    (net (code "259") (name "unconnected-(IC11-PF-Pad7)") (class "Default")
      (node (ref "IC11") (pin "7") (pinfunction "PF_7") (pintype "bidirectional"))
    )
    (net (code "260") (name "unconnected-(IC11-RX-Pad8)") (class "Default")
      (node (ref "IC11") (pin "8") (pinfunction "RX_8") (pintype "bidirectional"))
    )
    (net (code "261") (name "unconnected-(IC12-PF-Pad7)") (class "Default")
      (node (ref "IC12") (pin "7") (pinfunction "PF_7") (pintype "bidirectional"))
    )
    (net (code "262") (name "unconnected-(IC12-RX-Pad8)") (class "Default")
      (node (ref "IC12") (pin "8") (pinfunction "RX_8") (pintype "bidirectional"))
    )
    (net (code "263") (name "unconnected-(IC14-PF-Pad7)") (class "Default")
      (node (ref "IC14") (pin "7") (pinfunction "PF_7") (pintype "bidirectional"))
    )
    (net (code "264") (name "unconnected-(IC14-RX-Pad8)") (class "Default")
      (node (ref "IC14") (pin "8") (pinfunction "RX_8") (pintype "bidirectional"))
    )
    (net (code "265") (name "unconnected-(IC16-PF-Pad7)") (class "Default")
      (node (ref "IC16") (pin "7") (pinfunction "PF_7") (pintype "bidirectional"))
    )
    (net (code "266") (name "unconnected-(IC16-RX-Pad8)") (class "Default")
      (node (ref "IC16") (pin "8") (pinfunction "RX_8") (pintype "bidirectional"))
    )
    (net (code "267") (name "unconnected-(IC20-DNC-Pad7)") (class "Default")
      (node (ref "IC20") (pin "7") (pinfunction "DNC_7") (pintype "bidirectional"))
    )
    (net (code "268") (name "unconnected-(IC20-DUPLED-Pad26)") (class "Default")
      (node (ref "IC20") (pin "26") (pinfunction "DUPLED_26") (pintype "output"))
    )
    (net (code "269") (name "unconnected-(IC20-RSVD1-Pad23)") (class "Default")
      (node (ref "IC20") (pin "23") (pinfunction "RSVD1_23") (pintype "input"))
    )
    (net (code "270") (name "unconnected-(IC20-RSVD2-Pad38)") (class "Default")
      (node (ref "IC20") (pin "38") (pinfunction "RSVD2_38") (pintype "input"))
    )
    (net (code "271") (name "unconnected-(IC20-RSVD3-Pad39)") (class "Default")
      (node (ref "IC20") (pin "39") (pinfunction "RSVD3_39") (pintype "input"))
    )
    (net (code "272") (name "unconnected-(IC20-RSVD4-Pad40)") (class "Default")
      (node (ref "IC20") (pin "40") (pinfunction "RSVD4_40") (pintype "input"))
    )
    (net (code "273") (name "unconnected-(IC20-RSVD5-Pad41)") (class "Default")
      (node (ref "IC20") (pin "41") (pinfunction "RSVD5_41") (pintype "input"))
    )
    (net (code "274") (name "unconnected-(IC20-RSVD6-Pad42)") (class "Default")
      (node (ref "IC20") (pin "42") (pinfunction "RSVD6_42") (pintype "input"))
    )
    (net (code "275") (name "unconnected-(IC20-SPDLED-Pad24)") (class "Default")
      (node (ref "IC20") (pin "24") (pinfunction "SPDLED_24") (pintype "output"))
    )
    (net (code "276") (name "unconnected-(IC20-VBG-Pad18)") (class "Default")
      (node (ref "IC20") (pin "18") (pinfunction "VBG_18") (pintype "output"))
    )
    (net (code "277") (name "unconnected-(IC21-NC-Pad4)") (class "Default")
      (node (ref "IC21") (pin "4") (pinfunction "NC_4") (pintype "bidirectional"))
    )
    (net (code "278") (name "unconnected-(R149-5-PadD2)") (class "Default")
      (node (ref "R149") (pin "D2") (pinfunction "5_D2") (pintype "passive"))
    )
    (net (code "279") (name "unconnected-(USB1-SBU1-PadA8)") (class "Default")
      (node (ref "USB1") (pin "A8") (pinfunction "SBU1_A8") (pintype "bidirectional"))
    )
    (net (code "280") (name "unconnected-(USB1-SBU2-PadB8)") (class "Default")
      (node (ref "USB1") (pin "B8") (pinfunction "SBU2_B8") (pintype "bidirectional"))
    )
    (net (code "281") (name "~{ACT}") (class "Default")
      (node (ref "IC20") (pin "27") (pinfunction "ACTLED_27") (pintype "output"))
      (node (ref "R142") (pin "1") (pinfunction "1_1") (pintype "passive"))
    )
    (net (code "282") (name "~{LINK}") (class "Default")
      (node (ref "IC20") (pin "25") (pinfunction "LINKLED_25") (pintype "output"))
      (node (ref "R141") (pin "1") (pinfunction "1_1") (pintype "passive"))
    )
    (net (code "283") (name "~{QSPI_SS}") (class "Default")
      (node (ref "IC15") (pin "56") (pinfunction "QSPI_SS_N_56") (pintype "bidirectional"))
      (node (ref "IC18") (pin "1") (pinfunction "~{CS}_1") (pintype "bidirectional"))
      (node (ref "R111") (pin "1") (pinfunction "1_1") (pintype "passive"))
      (node (ref "R112") (pin "2") (pinfunction "2_2") (pintype "passive"))
    )
    (net (code "284") (name "~{TX_OUT}") (class "Default")
      (node (ref "IC22") (pin "3") (pinfunction "+IN_3") (pintype "input"))
      (node (ref "IC9") (pin "6") (pinfunction "~{Y}_6") (pintype "bidirectional"))
      (node (ref "R92") (pin "1") (pinfunction "1_1") (pintype "passive"))
    )
    (net (code "285") (name "~{W5500_CS}") (class "Default")
      (node (ref "CS1") (pin "TP") (pinfunction "P$1_TP") (pintype "bidirectional"))
      (node (ref "IC15") (pin "28") (pinfunction "GPIO17_28") (pintype "bidirectional"))
      (node (ref "IC20") (pin "32") (pinfunction "~{SCSN}_32") (pintype "input"))
    )
    (net (code "286") (name "~{W5500_INT}") (class "Default")
      (node (ref "IC15") (pin "32") (pinfunction "GPIO21_32") (pintype "bidirectional"))
      (node (ref "IC20") (pin "36") (pinfunction "~{INTN}_36") (pintype "input"))
    )
    (net (code "287") (name "~{W5500_RST}") (class "Default")
      (node (ref "IC15") (pin "31") (pinfunction "GPIO20_31") (pintype "bidirectional"))
      (node (ref "IC20") (pin "37") (pinfunction "~{RSTN}_37") (pintype "input"))
      (node (ref "R145") (pin "1") (pinfunction "1_1") (pintype "passive"))
    )
  )
)
